# Motherboard_V1_1.net
KiCad netlist of a schematic drawn in EAGLE
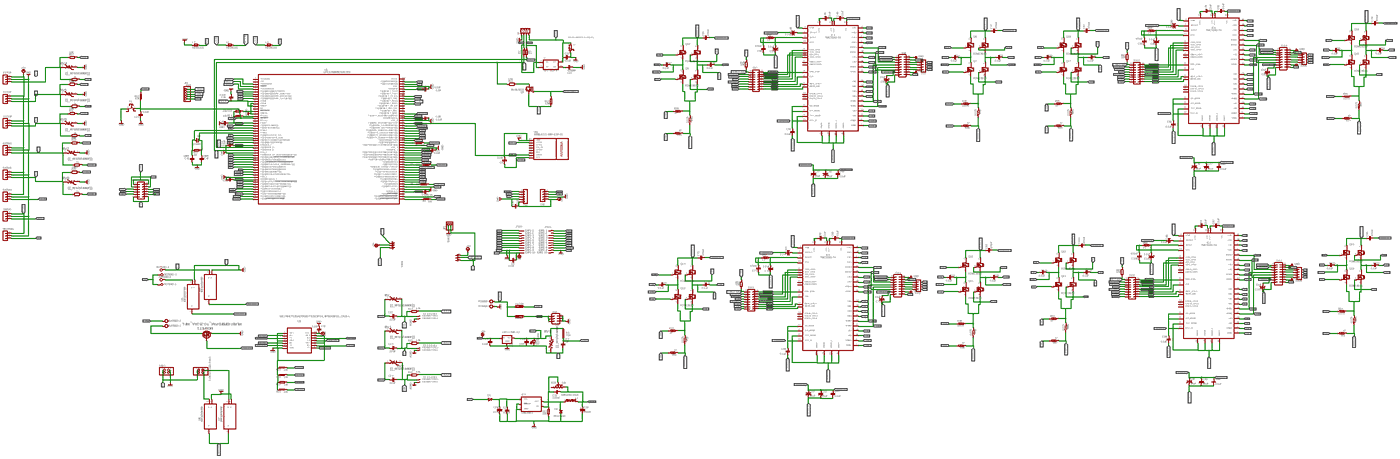
[diagram p0: schematic, sheet 1, overview]
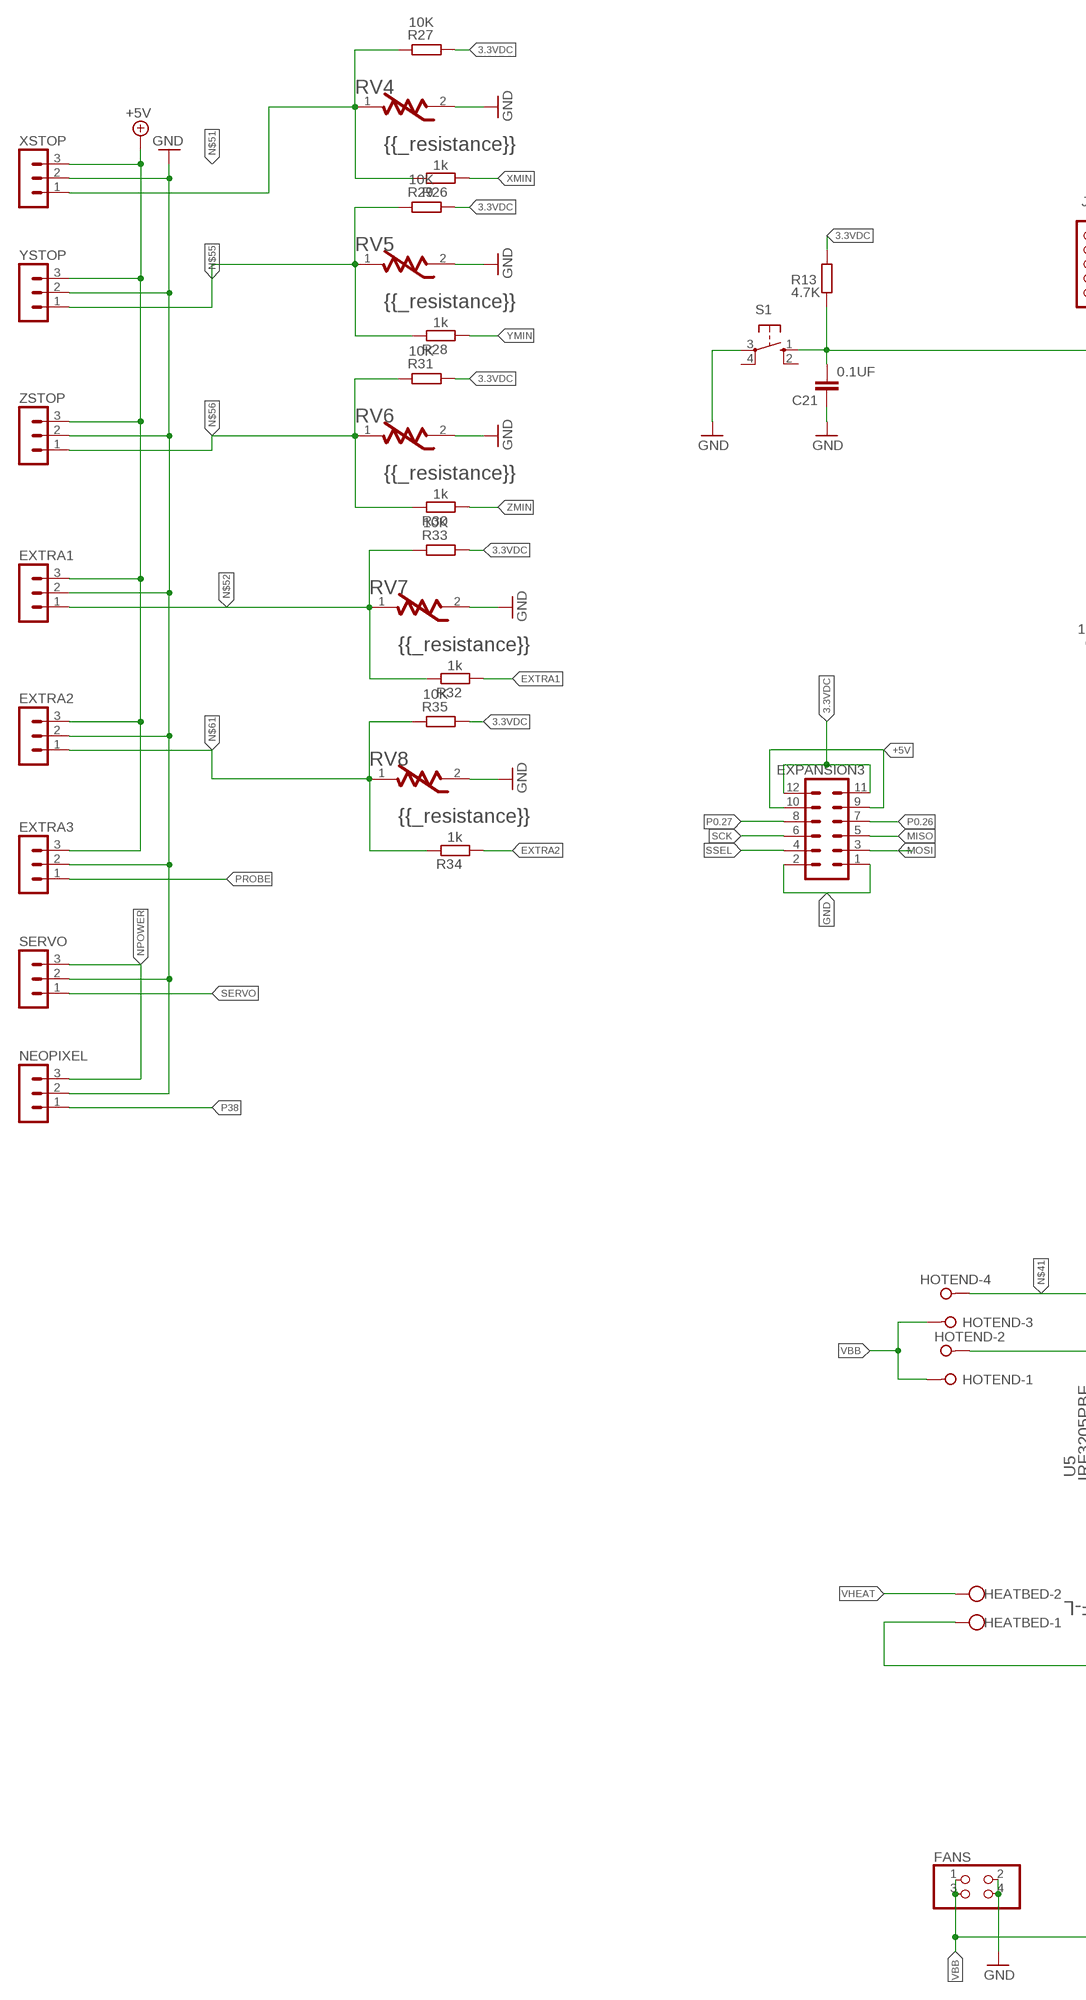
[diagram p1: schematic, sheet 1, part 1 of 4]
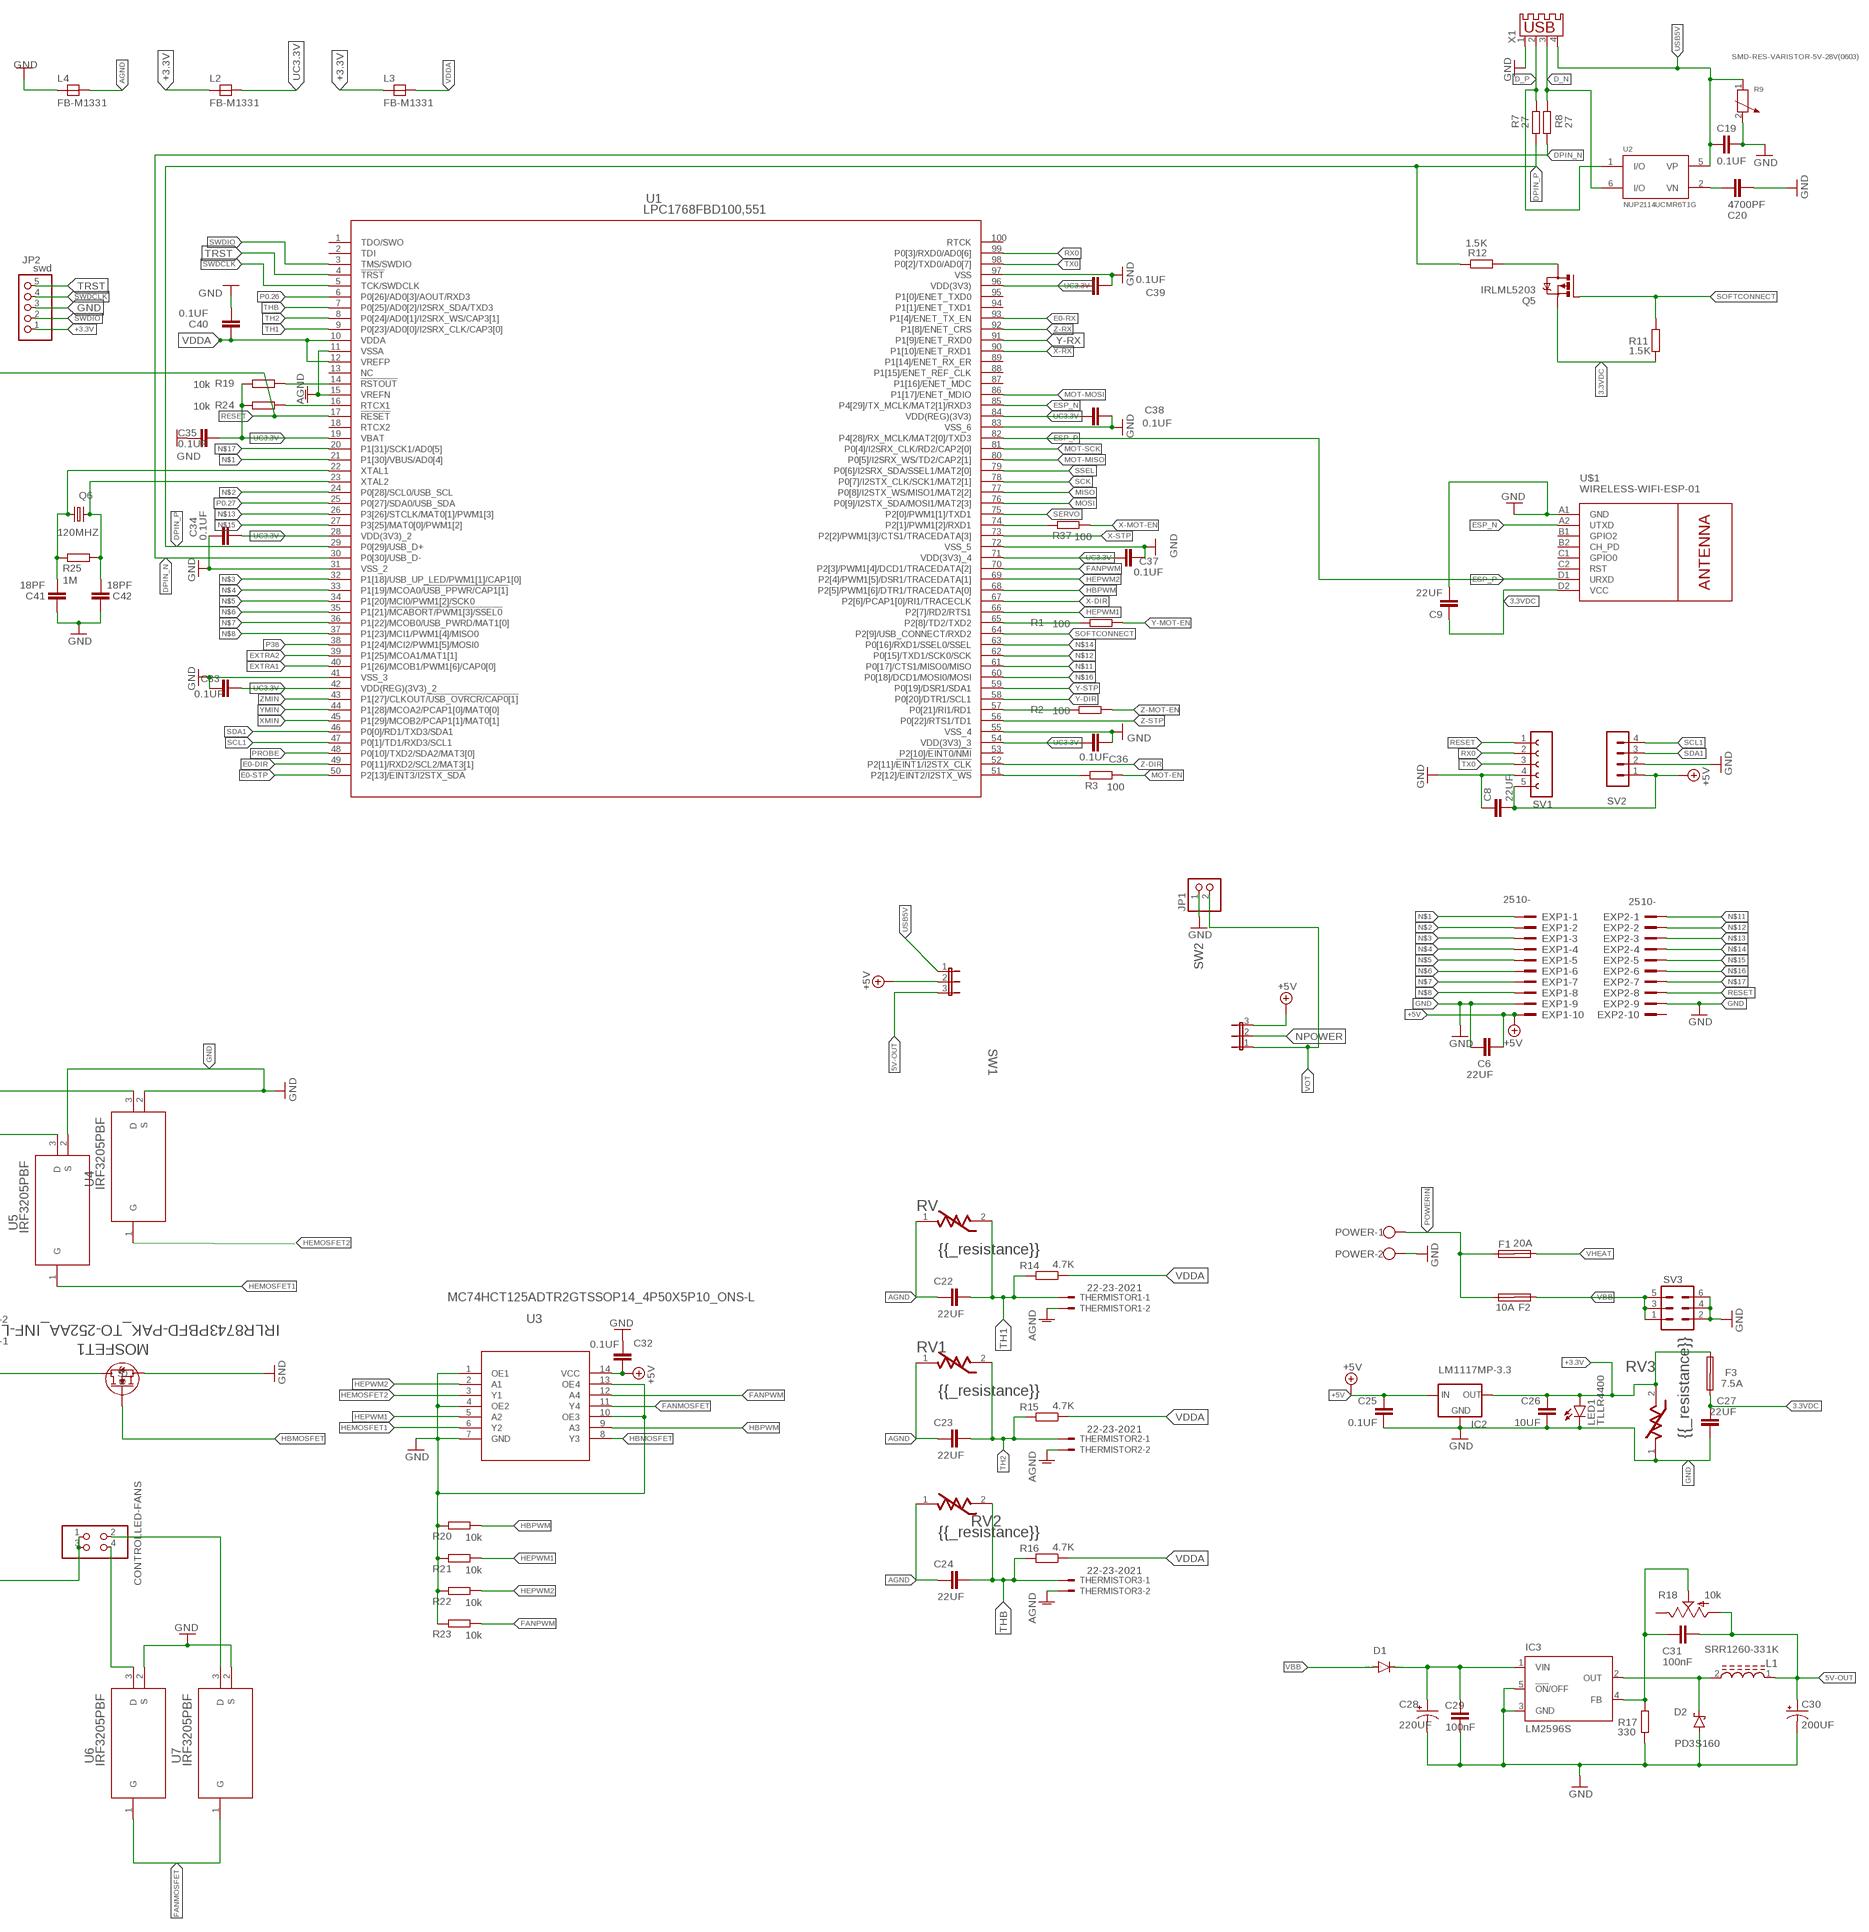
[diagram p2: schematic, sheet 1, part 2 of 4]
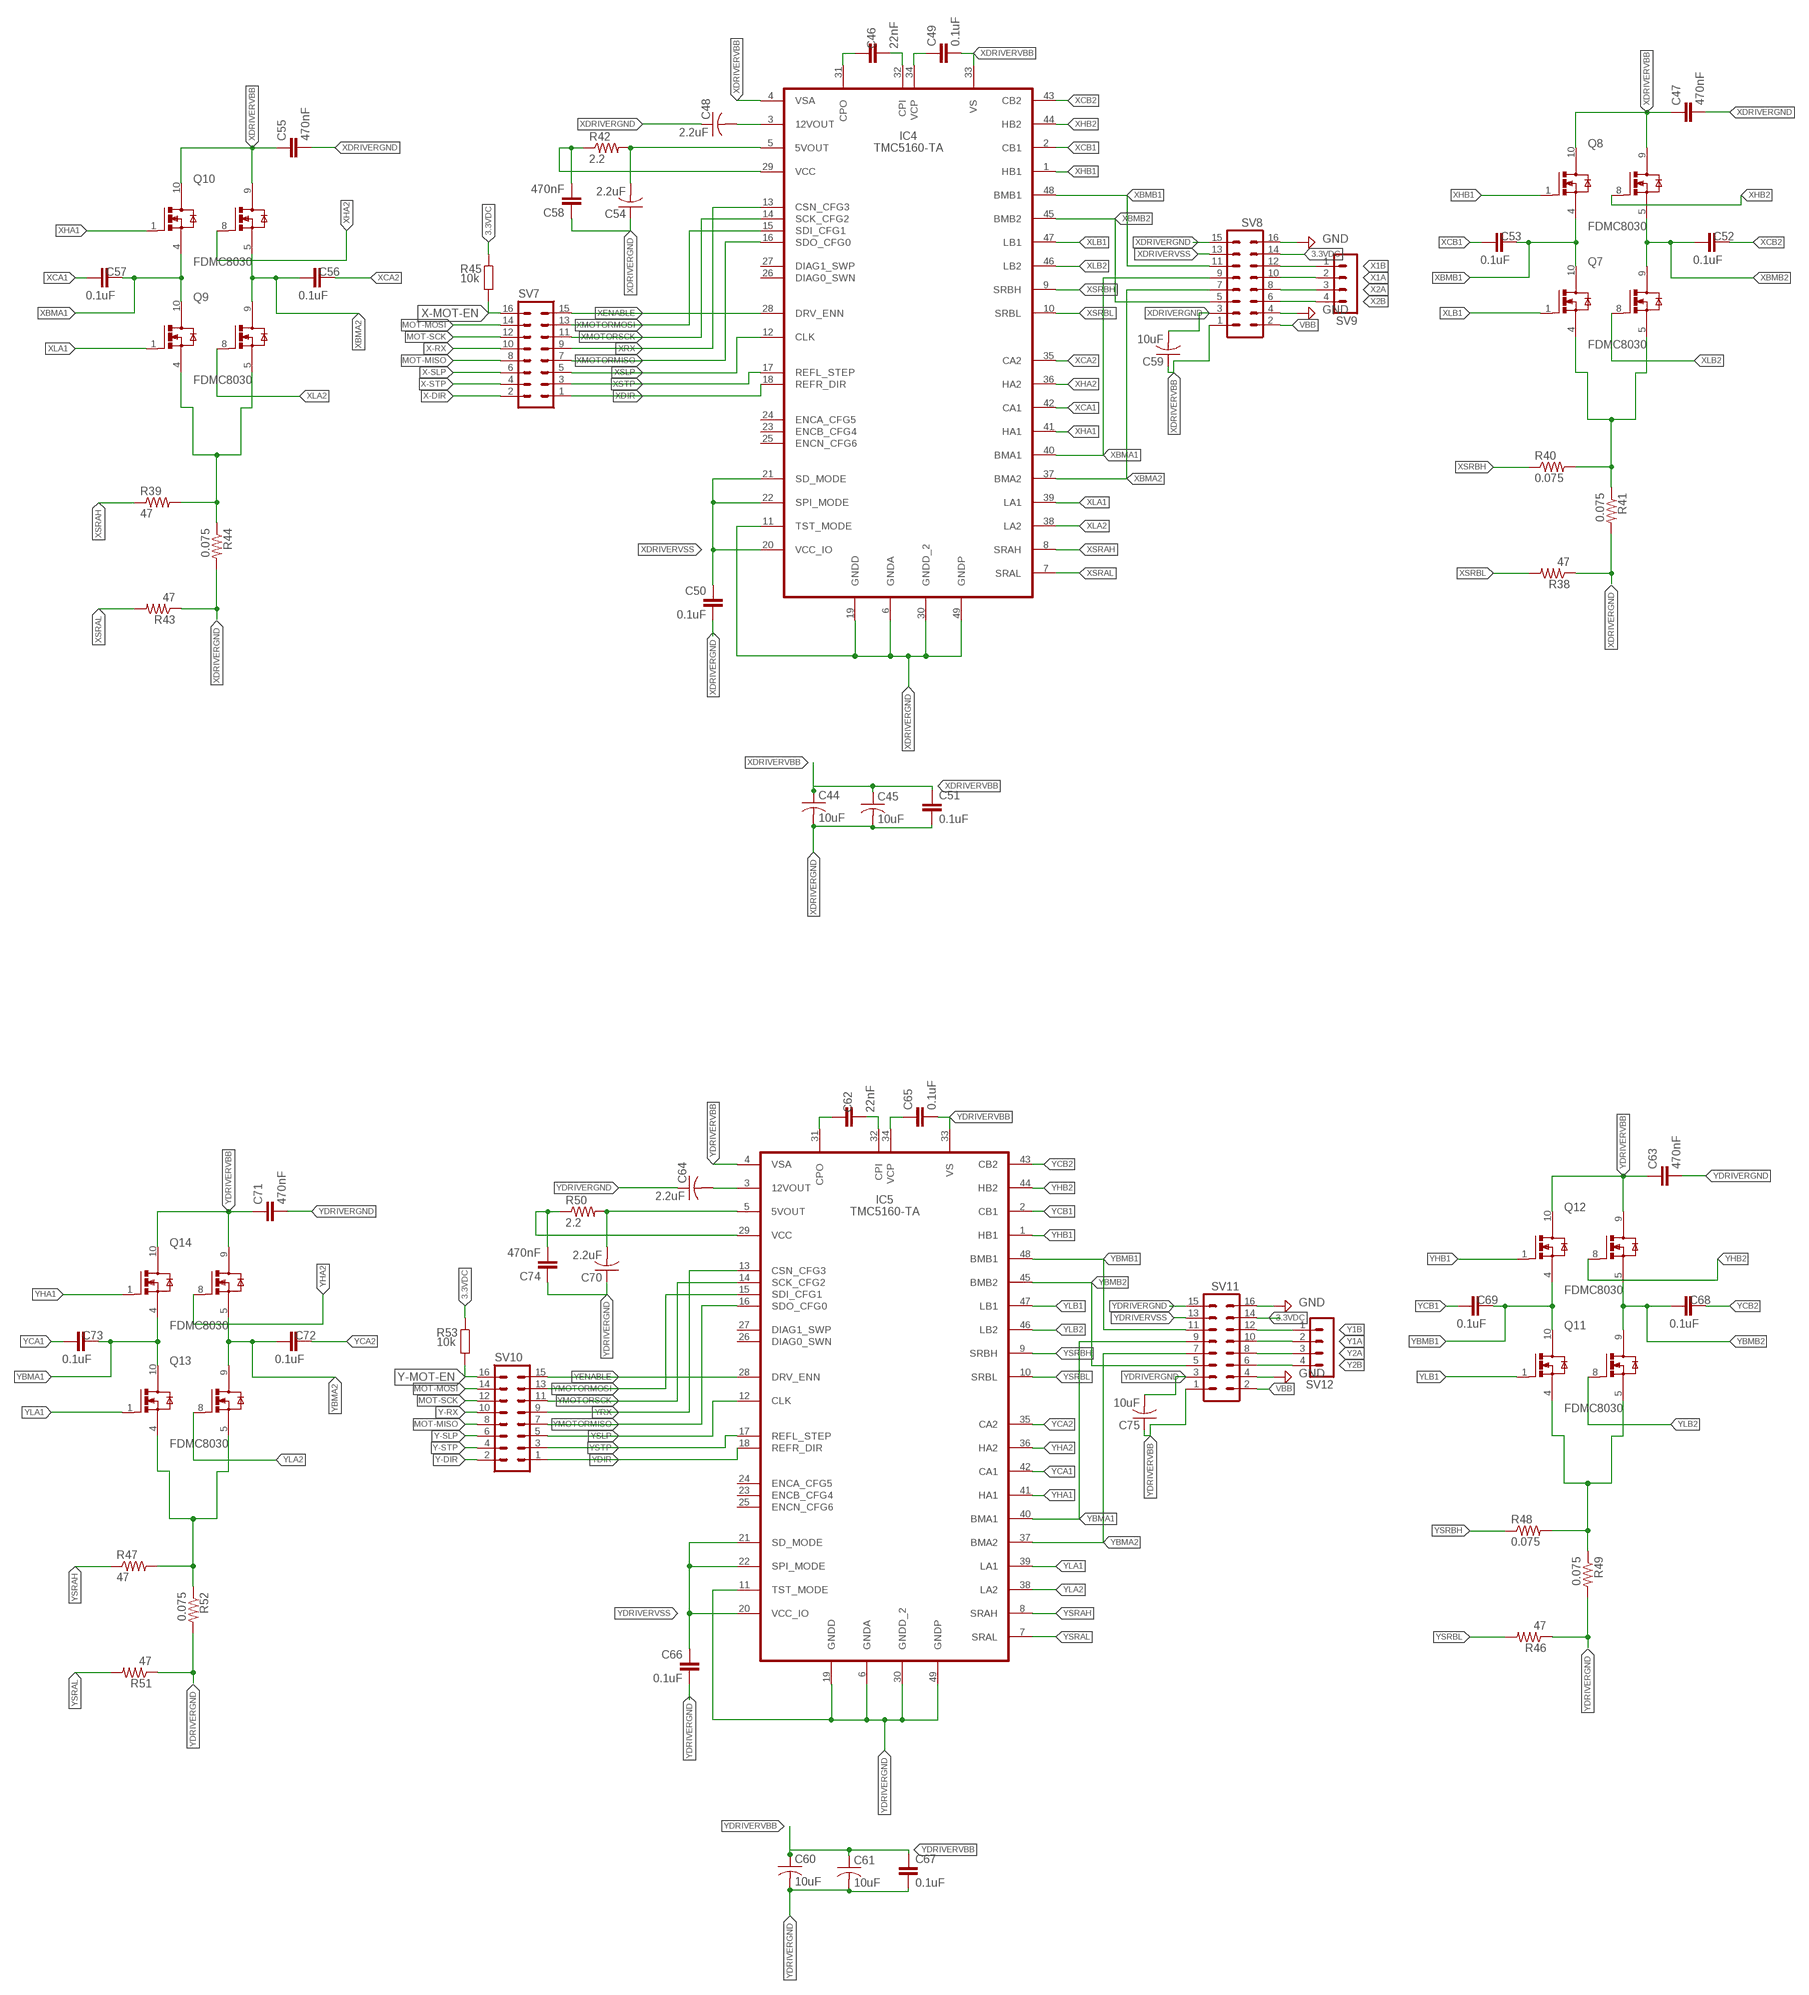
[diagram p3: schematic, sheet 1, part 3 of 4]
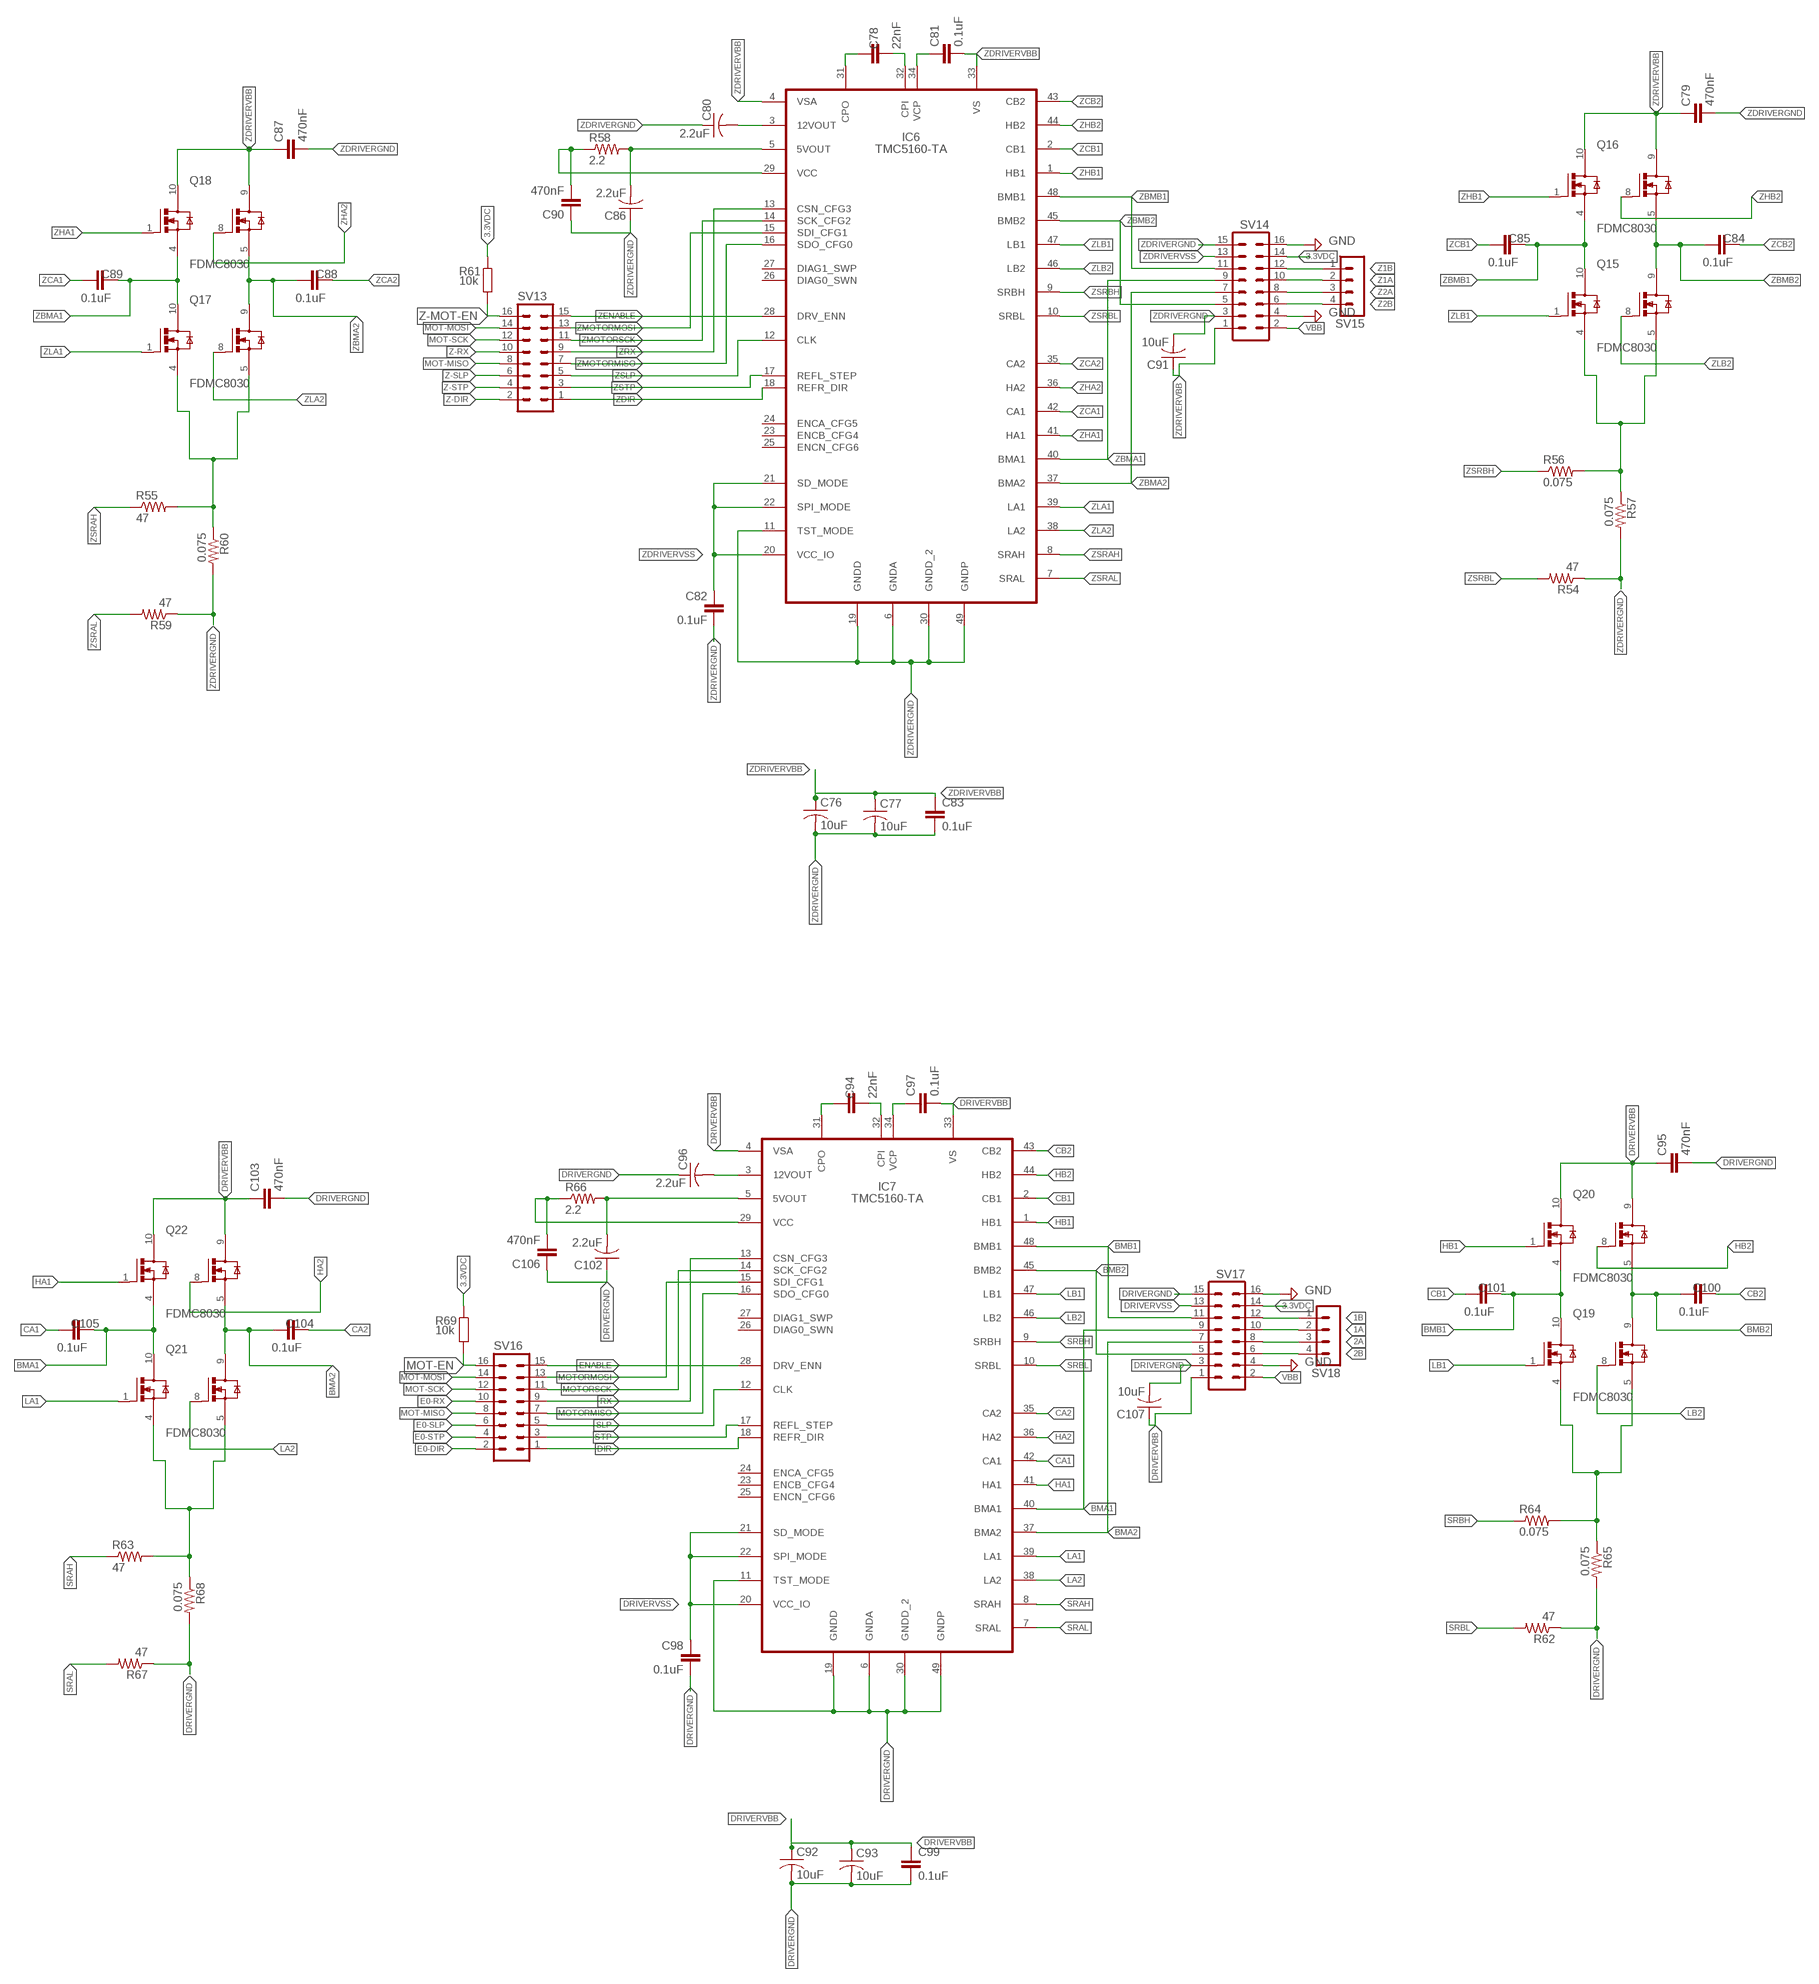
[diagram p4: schematic, sheet 1, part 4 of 4]

(export (version "E")
  (design (tool "Eeschema 10.0.6"))
  (components
    (comp (ref "C6")
      (value "22UF")
      (footprint "eagle-import:C0805")
      (libsource (lib "eagle-import") (part "C-EUC0805"))
    )
    (comp (ref "C8")
      (value "22UF")
      (footprint "eagle-import:C0805")
      (libsource (lib "eagle-import") (part "C-EUC0805"))
    )
    (comp (ref "C9")
      (value "22UF")
      (footprint "eagle-import:C0805")
      (libsource (lib "eagle-import") (part "C-EUC0805"))
    )
    (comp (ref "C19")
      (value "0.1UF")
      (footprint "eagle-import:C0805")
      (libsource (lib "eagle-import") (part "C-EUC0805"))
    )
    (comp (ref "C20")
      (value "4700PF")
      (footprint "eagle-import:C0805")
      (libsource (lib "eagle-import") (part "C-EUC0805"))
    )
    (comp (ref "C21")
      (value "0.1UF")
      (footprint "eagle-import:C0805")
      (libsource (lib "eagle-import") (part "C-EUC0805"))
    )
    (comp (ref "C22")
      (value "22UF")
      (footprint "eagle-import:C0805")
      (libsource (lib "eagle-import") (part "C-EUC0805"))
    )
    (comp (ref "C23")
      (value "22UF")
      (footprint "eagle-import:C0805")
      (libsource (lib "eagle-import") (part "C-EUC0805"))
    )
    (comp (ref "C24")
      (value "22UF")
      (footprint "eagle-import:C0805")
      (libsource (lib "eagle-import") (part "C-EUC0805"))
    )
    (comp (ref "C25")
      (value "0.1UF")
      (footprint "eagle-import:C0805")
      (libsource (lib "eagle-import") (part "C-EUC0805"))
    )
    (comp (ref "C26")
      (value "10UF")
      (footprint "eagle-import:C0805")
      (libsource (lib "eagle-import") (part "C-EUC0805"))
    )
    (comp (ref "C27")
      (value "22UF")
      (footprint "eagle-import:C0805")
      (libsource (lib "eagle-import") (part "C-EUC0805"))
    )
    (comp (ref "C28")
      (value "220UF")
      (footprint "eagle-import:E5-10,5")
      (libsource (lib "eagle-import") (part "CPOL-USE5-10.5"))
    )
    (comp (ref "C29")
      (value "100nF")
      (footprint "eagle-import:C0805")
      (libsource (lib "eagle-import") (part "C-EUC0805"))
    )
    (comp (ref "C30")
      (value "200UF")
      (footprint "eagle-import:E5-10,5")
      (libsource (lib "eagle-import") (part "CPOL-USE5-10.5"))
    )
    (comp (ref "C31")
      (value "100nF")
      (footprint "eagle-import:C0805")
      (libsource (lib "eagle-import") (part "C-EUC0805"))
    )
    (comp (ref "C32")
      (value "0.1UF")
      (footprint "eagle-import:C0805")
      (libsource (lib "eagle-import") (part "C-EUC0805"))
    )
    (comp (ref "C33")
      (value "0.1UF")
      (footprint "eagle-import:C0805")
      (libsource (lib "eagle-import") (part "C-EUC0805"))
    )
    (comp (ref "C34")
      (value "0.1UF")
      (footprint "eagle-import:C0805")
      (libsource (lib "eagle-import") (part "C-EUC0805"))
    )
    (comp (ref "C35")
      (value "0.1UF")
      (footprint "eagle-import:C0805")
      (libsource (lib "eagle-import") (part "C-EUC0805"))
    )
    (comp (ref "C36")
      (value "0.1UF")
      (footprint "eagle-import:C0805")
      (libsource (lib "eagle-import") (part "C-EUC0805"))
    )
    (comp (ref "C37")
      (value "0.1UF")
      (footprint "eagle-import:C0805")
      (libsource (lib "eagle-import") (part "C-EUC0805"))
    )
    (comp (ref "C38")
      (value "0.1UF")
      (footprint "eagle-import:C0805")
      (libsource (lib "eagle-import") (part "C-EUC0805"))
    )
    (comp (ref "C39")
      (value "0.1UF")
      (footprint "eagle-import:C0805")
      (libsource (lib "eagle-import") (part "C-EUC0805"))
    )
    (comp (ref "C40")
      (value "0.1UF")
      (footprint "eagle-import:C0805")
      (libsource (lib "eagle-import") (part "C-EUC0805"))
    )
    (comp (ref "C41")
      (value "18PF")
      (footprint "eagle-import:C0805")
      (libsource (lib "eagle-import") (part "C-EUC0805"))
    )
    (comp (ref "C42")
      (value "18PF")
      (footprint "eagle-import:C0805")
      (libsource (lib "eagle-import") (part "C-EUC0805"))
    )
    (comp (ref "C44")
      (value "10uF")
      (footprint "eagle-import:C0805")
      (libsource (lib "eagle-import") (part "C-USC0805"))
    )
    (comp (ref "C45")
      (value "10uF")
      (footprint "eagle-import:C0805")
      (libsource (lib "eagle-import") (part "C-USC0805"))
    )
    (comp (ref "C46")
      (value "22nF")
      (footprint "eagle-import:0603")
      (libsource (lib "eagle-import") (part "22NF/22,000PF-0603-50V-10%"))
    )
    (comp (ref "C47")
      (value "470nF")
      (footprint "eagle-import:0402")
      (libsource (lib "eagle-import") (part "470NF-0402-16V-10%"))
    )
    (comp (ref "C48")
      (value "2.2uF")
      (footprint "eagle-import:C0402")
      (libsource (lib "eagle-import") (part "C-USC0402"))
    )
    (comp (ref "C49")
      (value "0.1uF")
      (footprint "eagle-import:0402")
      (libsource (lib "eagle-import") (part "0.1UF-0402-16V-10%"))
    )
    (comp (ref "C50")
      (value "0.1uF")
      (footprint "eagle-import:0402")
      (libsource (lib "eagle-import") (part "0.1UF-0402-16V-10%"))
    )
    (comp (ref "C51")
      (value "0.1uF")
      (footprint "eagle-import:0402")
      (libsource (lib "eagle-import") (part "0.1UF-0402-16V-10%"))
    )
    (comp (ref "C52")
      (value "0.1uF")
      (footprint "eagle-import:0402")
      (libsource (lib "eagle-import") (part "0.1UF-0402-16V-10%"))
    )
    (comp (ref "C53")
      (value "0.1uF")
      (footprint "eagle-import:0402")
      (libsource (lib "eagle-import") (part "0.1UF-0402-16V-10%"))
    )
    (comp (ref "C54")
      (value "2.2uF")
      (footprint "eagle-import:C0402")
      (libsource (lib "eagle-import") (part "C-USC0402"))
    )
    (comp (ref "C55")
      (value "470nF")
      (footprint "eagle-import:0402")
      (libsource (lib "eagle-import") (part "470NF-0402-16V-10%"))
    )
    (comp (ref "C56")
      (value "0.1uF")
      (footprint "eagle-import:0402")
      (libsource (lib "eagle-import") (part "0.1UF-0402-16V-10%"))
    )
    (comp (ref "C57")
      (value "0.1uF")
      (footprint "eagle-import:0402")
      (libsource (lib "eagle-import") (part "0.1UF-0402-16V-10%"))
    )
    (comp (ref "C58")
      (value "470nF")
      (footprint "eagle-import:0402")
      (libsource (lib "eagle-import") (part "470NF-0402-16V-10%"))
    )
    (comp (ref "C59")
      (value "10uF")
      (footprint "eagle-import:C0805")
      (libsource (lib "eagle-import") (part "C-USC0805"))
    )
    (comp (ref "C60")
      (value "10uF")
      (footprint "eagle-import:C0805")
      (libsource (lib "eagle-import") (part "C-USC0805"))
    )
    (comp (ref "C61")
      (value "10uF")
      (footprint "eagle-import:C0805")
      (libsource (lib "eagle-import") (part "C-USC0805"))
    )
    (comp (ref "C62")
      (value "22nF")
      (footprint "eagle-import:0603")
      (libsource (lib "eagle-import") (part "22NF/22,000PF-0603-50V-10%"))
    )
    (comp (ref "C63")
      (value "470nF")
      (footprint "eagle-import:0402")
      (libsource (lib "eagle-import") (part "470NF-0402-16V-10%"))
    )
    (comp (ref "C64")
      (value "2.2uF")
      (footprint "eagle-import:C0402")
      (libsource (lib "eagle-import") (part "C-USC0402"))
    )
    (comp (ref "C65")
      (value "0.1uF")
      (footprint "eagle-import:0402")
      (libsource (lib "eagle-import") (part "0.1UF-0402-16V-10%"))
    )
    (comp (ref "C66")
      (value "0.1uF")
      (footprint "eagle-import:0402")
      (libsource (lib "eagle-import") (part "0.1UF-0402-16V-10%"))
    )
    (comp (ref "C67")
      (value "0.1uF")
      (footprint "eagle-import:0402")
      (libsource (lib "eagle-import") (part "0.1UF-0402-16V-10%"))
    )
    (comp (ref "C68")
      (value "0.1uF")
      (footprint "eagle-import:0402")
      (libsource (lib "eagle-import") (part "0.1UF-0402-16V-10%"))
    )
    (comp (ref "C69")
      (value "0.1uF")
      (footprint "eagle-import:0402")
      (libsource (lib "eagle-import") (part "0.1UF-0402-16V-10%"))
    )
    (comp (ref "C70")
      (value "2.2uF")
      (footprint "eagle-import:C0402")
      (libsource (lib "eagle-import") (part "C-USC0402"))
    )
    (comp (ref "C71")
      (value "470nF")
      (footprint "eagle-import:0402")
      (libsource (lib "eagle-import") (part "470NF-0402-16V-10%"))
    )
    (comp (ref "C72")
      (value "0.1uF")
      (footprint "eagle-import:0402")
      (libsource (lib "eagle-import") (part "0.1UF-0402-16V-10%"))
    )
    (comp (ref "C73")
      (value "0.1uF")
      (footprint "eagle-import:0402")
      (libsource (lib "eagle-import") (part "0.1UF-0402-16V-10%"))
    )
    (comp (ref "C74")
      (value "470nF")
      (footprint "eagle-import:0402")
      (libsource (lib "eagle-import") (part "470NF-0402-16V-10%"))
    )
    (comp (ref "C75")
      (value "10uF")
      (footprint "eagle-import:C0805")
      (libsource (lib "eagle-import") (part "C-USC0805"))
    )
    (comp (ref "C76")
      (value "10uF")
      (footprint "eagle-import:C0805")
      (libsource (lib "eagle-import") (part "C-USC0805"))
    )
    (comp (ref "C77")
      (value "10uF")
      (footprint "eagle-import:C0805")
      (libsource (lib "eagle-import") (part "C-USC0805"))
    )
    (comp (ref "C78")
      (value "22nF")
      (footprint "eagle-import:0603")
      (libsource (lib "eagle-import") (part "22NF/22,000PF-0603-50V-10%"))
    )
    (comp (ref "C79")
      (value "470nF")
      (footprint "eagle-import:0402")
      (libsource (lib "eagle-import") (part "470NF-0402-16V-10%"))
    )
    (comp (ref "C80")
      (value "2.2uF")
      (footprint "eagle-import:C0402")
      (libsource (lib "eagle-import") (part "C-USC0402"))
    )
    (comp (ref "C81")
      (value "0.1uF")
      (footprint "eagle-import:0402")
      (libsource (lib "eagle-import") (part "0.1UF-0402-16V-10%"))
    )
    (comp (ref "C82")
      (value "0.1uF")
      (footprint "eagle-import:0402")
      (libsource (lib "eagle-import") (part "0.1UF-0402-16V-10%"))
    )
    (comp (ref "C83")
      (value "0.1uF")
      (footprint "eagle-import:0402")
      (libsource (lib "eagle-import") (part "0.1UF-0402-16V-10%"))
    )
    (comp (ref "C84")
      (value "0.1uF")
      (footprint "eagle-import:0402")
      (libsource (lib "eagle-import") (part "0.1UF-0402-16V-10%"))
    )
    (comp (ref "C85")
      (value "0.1uF")
      (footprint "eagle-import:0402")
      (libsource (lib "eagle-import") (part "0.1UF-0402-16V-10%"))
    )
    (comp (ref "C86")
      (value "2.2uF")
      (footprint "eagle-import:C0402")
      (libsource (lib "eagle-import") (part "C-USC0402"))
    )
    (comp (ref "C87")
      (value "470nF")
      (footprint "eagle-import:0402")
      (libsource (lib "eagle-import") (part "470NF-0402-16V-10%"))
    )
    (comp (ref "C88")
      (value "0.1uF")
      (footprint "eagle-import:0402")
      (libsource (lib "eagle-import") (part "0.1UF-0402-16V-10%"))
    )
    (comp (ref "C89")
      (value "0.1uF")
      (footprint "eagle-import:0402")
      (libsource (lib "eagle-import") (part "0.1UF-0402-16V-10%"))
    )
    (comp (ref "C90")
      (value "470nF")
      (footprint "eagle-import:0402")
      (libsource (lib "eagle-import") (part "470NF-0402-16V-10%"))
    )
    (comp (ref "C91")
      (value "10uF")
      (footprint "eagle-import:C0805")
      (libsource (lib "eagle-import") (part "C-USC0805"))
    )
    (comp (ref "C92")
      (value "10uF")
      (footprint "eagle-import:C0805")
      (libsource (lib "eagle-import") (part "C-USC0805"))
    )
    (comp (ref "C93")
      (value "10uF")
      (footprint "eagle-import:C0805")
      (libsource (lib "eagle-import") (part "C-USC0805"))
    )
    (comp (ref "C94")
      (value "22nF")
      (footprint "eagle-import:0603")
      (libsource (lib "eagle-import") (part "22NF/22,000PF-0603-50V-10%"))
    )
    (comp (ref "C95")
      (value "470nF")
      (footprint "eagle-import:0402")
      (libsource (lib "eagle-import") (part "470NF-0402-16V-10%"))
    )
    (comp (ref "C96")
      (value "2.2uF")
      (footprint "eagle-import:C0402")
      (libsource (lib "eagle-import") (part "C-USC0402"))
    )
    (comp (ref "C97")
      (value "0.1uF")
      (footprint "eagle-import:0402")
      (libsource (lib "eagle-import") (part "0.1UF-0402-16V-10%"))
    )
    (comp (ref "C98")
      (value "0.1uF")
      (footprint "eagle-import:0402")
      (libsource (lib "eagle-import") (part "0.1UF-0402-16V-10%"))
    )
    (comp (ref "C99")
      (value "0.1uF")
      (footprint "eagle-import:0402")
      (libsource (lib "eagle-import") (part "0.1UF-0402-16V-10%"))
    )
    (comp (ref "C100")
      (value "0.1uF")
      (footprint "eagle-import:0402")
      (libsource (lib "eagle-import") (part "0.1UF-0402-16V-10%"))
    )
    (comp (ref "C101")
      (value "0.1uF")
      (footprint "eagle-import:0402")
      (libsource (lib "eagle-import") (part "0.1UF-0402-16V-10%"))
    )
    (comp (ref "C102")
      (value "2.2uF")
      (footprint "eagle-import:C0402")
      (libsource (lib "eagle-import") (part "C-USC0402"))
    )
    (comp (ref "C103")
      (value "470nF")
      (footprint "eagle-import:0402")
      (libsource (lib "eagle-import") (part "470NF-0402-16V-10%"))
    )
    (comp (ref "C104")
      (value "0.1uF")
      (footprint "eagle-import:0402")
      (libsource (lib "eagle-import") (part "0.1UF-0402-16V-10%"))
    )
    (comp (ref "C105")
      (value "0.1uF")
      (footprint "eagle-import:0402")
      (libsource (lib "eagle-import") (part "0.1UF-0402-16V-10%"))
    )
    (comp (ref "C106")
      (value "470nF")
      (footprint "eagle-import:0402")
      (libsource (lib "eagle-import") (part "470NF-0402-16V-10%"))
    )
    (comp (ref "C107")
      (value "10uF")
      (footprint "eagle-import:C0805")
      (libsource (lib "eagle-import") (part "C-USC0805"))
    )
    (comp (ref "CONTROLLED-FANS")
      (value "PINHD-2X2")
      (footprint "eagle-import:2X02")
      (libsource (lib "eagle-import") (part "PINHD-2X2"))
    )
    (comp (ref "D1")
      (value "DIODE-DO214AA")
      (footprint "eagle-import:DO214AA")
      (libsource (lib "eagle-import") (part "DIODE-DO214AA"))
    )
    (comp (ref "D2")
      (value "PD3S160")
      (footprint "eagle-import:POWERDI323")
      (libsource (lib "eagle-import") (part "PD3S160"))
    )
    (comp (ref "EXP1")
      (value "2510-")
      (footprint "eagle-import:PAK100_2500-10")
      (fields (field (name "MF") "3M") (field (name "MPN") "2510-6002UB"))
      (libsource (lib "eagle-import") (part "2510-"))
    )
    (comp (ref "EXP2")
      (value "2510-")
      (footprint "eagle-import:PAK100_2500-10")
      (fields (field (name "MF") "3M") (field (name "MPN") "2510-6002UB"))
      (libsource (lib "eagle-import") (part "2510-"))
    )
    (comp (ref "EXPANSION3")
      (value "MA06-2")
      (footprint "eagle-import:MA06-2")
      (libsource (lib "eagle-import") (part "MA06-2"))
    )
    (comp (ref "EXTRA1")
      (value "MA03-1")
      (footprint "eagle-import:MA03-1")
      (libsource (lib "eagle-import") (part "MA03-1"))
    )
    (comp (ref "EXTRA2")
      (value "MA03-1")
      (footprint "eagle-import:MA03-1")
      (libsource (lib "eagle-import") (part "MA03-1"))
    )
    (comp (ref "EXTRA3")
      (value "MA03-1")
      (footprint "eagle-import:MA03-1")
      (libsource (lib "eagle-import") (part "MA03-1"))
    )
    (comp (ref "F1")
      (value "20A")
      (footprint "eagle-import:SHK20Q")
      (libsource (lib "eagle-import") (part "SHK20Q"))
    )
    (comp (ref "F2")
      (value "10A")
      (footprint "eagle-import:SHK20Q")
      (libsource (lib "eagle-import") (part "SHK20Q"))
    )
    (comp (ref "F3")
      (value "7.5A")
      (footprint "eagle-import:SHK20Q")
      (libsource (lib "eagle-import") (part "SHK20Q"))
    )
    (comp (ref "FANS")
      (value "PINHD-2X2")
      (footprint "eagle-import:2X02")
      (libsource (lib "eagle-import") (part "PINHD-2X2"))
    )
    (comp (ref "HEATBED")
      (value "W237-102")
      (footprint "eagle-import:W237-102")
      (fields (field (name "MPN") "237-102"))
      (libsource (lib "eagle-import") (part "W237-102"))
    )
    (comp (ref "HOTEND")
      (value "W237-04P")
      (footprint "eagle-import:W237-4P")
      (libsource (lib "eagle-import") (part "W237-04P"))
    )
    (comp (ref "IC2")
      (value "LM1117MP-3.3")
      (footprint "eagle-import:SOT223")
      (fields (field (name "MF") "Texas Instruments"))
      (libsource (lib "eagle-import") (part "LM1117?-MP3.3"))
    )
    (comp (ref "IC3")
      (value "LM2596S")
      (footprint "eagle-import:TO263-5")
      (fields (field (name "MF") "NATIONAL SEMICONDUCTOR") (field (name "MPN") "LM2596S-ADJ/NOPB"))
      (libsource (lib "eagle-import") (part "LM2596S"))
    )
    (comp (ref "IC4")
      (value "TMC5160-TA")
      (footprint "eagle-import:TQFP48-EP")
      (fields (field (name "MF") "Trinamic Motion"))
      (libsource (lib "eagle-import") (part "TMC5160-TA"))
    )
    (comp (ref "IC5")
      (value "TMC5160-TA")
      (footprint "eagle-import:TQFP48-EP")
      (fields (field (name "MF") "Trinamic Motion"))
      (libsource (lib "eagle-import") (part "TMC5160-TA"))
    )
    (comp (ref "IC6")
      (value "TMC5160-TA")
      (footprint "eagle-import:TQFP48-EP")
      (fields (field (name "MF") "Trinamic Motion"))
      (libsource (lib "eagle-import") (part "TMC5160-TA"))
    )
    (comp (ref "IC7")
      (value "TMC5160-TA")
      (footprint "eagle-import:TQFP48-EP")
      (fields (field (name "MF") "Trinamic Motion"))
      (libsource (lib "eagle-import") (part "TMC5160-TA"))
    )
    (comp (ref "JP1")
      (value "PINHD-1X2")
      (footprint "eagle-import:1X02")
      (libsource (lib "eagle-import") (part "PINHD-1X2"))
    )
    (comp (ref "JP2")
      (value "swd")
      (footprint "eagle-import:1X05")
      (libsource (lib "eagle-import") (part "PINHD-1X5"))
    )
    (comp (ref "L1")
      (value "SRR1260-331K")
      (footprint "eagle-import:INDP125125X600N")
      (fields (field (name "MF") "Bourns"))
      (libsource (lib "eagle-import") (part "SRR1260-331K"))
    )
    (comp (ref "L2")
      (value "FB-M1331")
      (footprint "eagle-import:M1331")
      (libsource (lib "eagle-import") (part "FB-M1331"))
    )
    (comp (ref "L3")
      (value "FB-M1331")
      (footprint "eagle-import:M1331")
      (libsource (lib "eagle-import") (part "FB-M1331"))
    )
    (comp (ref "L4")
      (value "FB-M1331")
      (footprint "eagle-import:M1331")
      (libsource (lib "eagle-import") (part "FB-M1331"))
    )
    (comp (ref "LED1")
      (value "TLLR4400")
      (footprint "eagle-import:LED3MM")
      (fields (field (name "MF") "VISHAY SEMICONDUCTOR"))
      (libsource (lib "eagle-import") (part "TLLR4400"))
    )
    (comp (ref "MOSFET1")
      (value "IRLR8743PBFD-PAK_TO-252AA_INF-L")
      (footprint "eagle-import:D-PAK_TO-252AA_INF-L")
      (fields
        (field (name "MANUFACTURER_PART_NUMBER") "IRLR8743PBF")
        (field (name "COPYRIGHT") "Copyright (C) 2018 Accelerated Designs. All rights reserved")
      )
      (libsource (lib "eagle-import") (part "IRLR8743PBFD-PAK_TO-252AA_INF-L"))
    )
    (comp (ref "NEOPIXEL")
      (value "MA03-1")
      (footprint "eagle-import:MA03-1")
      (libsource (lib "eagle-import") (part "MA03-1"))
    )
    (comp (ref "POWER")
      (value "W237-102")
      (footprint "eagle-import:W237-102")
      (fields (field (name "MPN") "237-102"))
      (libsource (lib "eagle-import") (part "W237-102"))
    )
    (comp (ref "Q5")
      (value "IRLML5203")
      (footprint "eagle-import:MICRO3")
      (libsource (lib "eagle-import") (part "IRLML5203"))
    )
    (comp (ref "Q6")
      (value "120MHZ")
      (footprint "eagle-import:HC49_S")
      (libsource (lib "eagle-import") (part "CRYSTALHC49S"))
    )
    (comp (ref "Q7")
      (value "FDMC8030")
      (footprint "eagle-import:TRANS_FDMC8030")
      (fields (field (name "MF") "ON Semiconductor"))
      (libsource (lib "eagle-import") (part "FDMC8030"))
    )
    (comp (ref "Q8")
      (value "FDMC8030")
      (footprint "eagle-import:TRANS_FDMC8030")
      (fields (field (name "MF") "ON Semiconductor"))
      (libsource (lib "eagle-import") (part "FDMC8030"))
    )
    (comp (ref "Q9")
      (value "FDMC8030")
      (footprint "eagle-import:TRANS_FDMC8030")
      (fields (field (name "MF") "ON Semiconductor"))
      (libsource (lib "eagle-import") (part "FDMC8030"))
    )
    (comp (ref "Q10")
      (value "FDMC8030")
      (footprint "eagle-import:TRANS_FDMC8030")
      (fields (field (name "MF") "ON Semiconductor"))
      (libsource (lib "eagle-import") (part "FDMC8030"))
    )
    (comp (ref "Q11")
      (value "FDMC8030")
      (footprint "eagle-import:TRANS_FDMC8030")
      (fields (field (name "MF") "ON Semiconductor"))
      (libsource (lib "eagle-import") (part "FDMC8030"))
    )
    (comp (ref "Q12")
      (value "FDMC8030")
      (footprint "eagle-import:TRANS_FDMC8030")
      (fields (field (name "MF") "ON Semiconductor"))
      (libsource (lib "eagle-import") (part "FDMC8030"))
    )
    (comp (ref "Q13")
      (value "FDMC8030")
      (footprint "eagle-import:TRANS_FDMC8030")
      (fields (field (name "MF") "ON Semiconductor"))
      (libsource (lib "eagle-import") (part "FDMC8030"))
    )
    (comp (ref "Q14")
      (value "FDMC8030")
      (footprint "eagle-import:TRANS_FDMC8030")
      (fields (field (name "MF") "ON Semiconductor"))
      (libsource (lib "eagle-import") (part "FDMC8030"))
    )
    (comp (ref "Q15")
      (value "FDMC8030")
      (footprint "eagle-import:TRANS_FDMC8030")
      (fields (field (name "MF") "ON Semiconductor"))
      (libsource (lib "eagle-import") (part "FDMC8030"))
    )
    (comp (ref "Q16")
      (value "FDMC8030")
      (footprint "eagle-import:TRANS_FDMC8030")
      (fields (field (name "MF") "ON Semiconductor"))
      (libsource (lib "eagle-import") (part "FDMC8030"))
    )
    (comp (ref "Q17")
      (value "FDMC8030")
      (footprint "eagle-import:TRANS_FDMC8030")
      (fields (field (name "MF") "ON Semiconductor"))
      (libsource (lib "eagle-import") (part "FDMC8030"))
    )
    (comp (ref "Q18")
      (value "FDMC8030")
      (footprint "eagle-import:TRANS_FDMC8030")
      (fields (field (name "MF") "ON Semiconductor"))
      (libsource (lib "eagle-import") (part "FDMC8030"))
    )
    (comp (ref "Q19")
      (value "FDMC8030")
      (footprint "eagle-import:TRANS_FDMC8030")
      (fields (field (name "MF") "ON Semiconductor"))
      (libsource (lib "eagle-import") (part "FDMC8030"))
    )
    (comp (ref "Q20")
      (value "FDMC8030")
      (footprint "eagle-import:TRANS_FDMC8030")
      (fields (field (name "MF") "ON Semiconductor"))
      (libsource (lib "eagle-import") (part "FDMC8030"))
    )
    (comp (ref "Q21")
      (value "FDMC8030")
      (footprint "eagle-import:TRANS_FDMC8030")
      (fields (field (name "MF") "ON Semiconductor"))
      (libsource (lib "eagle-import") (part "FDMC8030"))
    )
    (comp (ref "Q22")
      (value "FDMC8030")
      (footprint "eagle-import:TRANS_FDMC8030")
      (fields (field (name "MF") "ON Semiconductor"))
      (libsource (lib "eagle-import") (part "FDMC8030"))
    )
    (comp (ref "R1")
      (value "100")
      (footprint "eagle-import:R0805")
      (libsource (lib "eagle-import") (part "R-EU_R0805"))
    )
    (comp (ref "R2")
      (value "100")
      (footprint "eagle-import:R0805")
      (libsource (lib "eagle-import") (part "R-EU_R0805"))
    )
    (comp (ref "R3")
      (value "100")
      (footprint "eagle-import:R0805")
      (libsource (lib "eagle-import") (part "R-EU_R0805"))
    )
    (comp (ref "R7")
      (value "27")
      (footprint "eagle-import:R0805")
      (libsource (lib "eagle-import") (part "R-EU_R0805"))
    )
    (comp (ref "R8")
      (value "27")
      (footprint "eagle-import:R0805")
      (libsource (lib "eagle-import") (part "R-EU_R0805"))
    )
    (comp (ref "R9")
      (value "SMD-RES-VARISTOR-5V-28V(0603)")
      (footprint "eagle-import:R0603")
      (fields
        (field (name "DIGI-KEY_PART_NUMBER") "CG0603MLC-05ECT-ND")
        (field (name "MF") "Bourns")
        (field (name "MP") "CG0603MLC-05E")
      )
      (libsource (lib "eagle-import") (part "SMD-RES-VARISTOR-5V-28V(0603)"))
    )
    (comp (ref "R11")
      (value "1.5K")
      (footprint "eagle-import:R0805")
      (libsource (lib "eagle-import") (part "R-EU_R0805"))
    )
    (comp (ref "R12")
      (value "1.5K")
      (footprint "eagle-import:R0805")
      (libsource (lib "eagle-import") (part "R-EU_R0805"))
    )
    (comp (ref "R13")
      (value "4.7K")
      (footprint "eagle-import:R0805")
      (libsource (lib "eagle-import") (part "R-EU_R0805"))
    )
    (comp (ref "R14")
      (value "4.7K")
      (footprint "eagle-import:R0805")
      (libsource (lib "eagle-import") (part "R-EU_R0805"))
    )
    (comp (ref "R15")
      (value "4.7K")
      (footprint "eagle-import:R0805")
      (libsource (lib "eagle-import") (part "R-EU_R0805"))
    )
    (comp (ref "R16")
      (value "4.7K")
      (footprint "eagle-import:R0805")
      (libsource (lib "eagle-import") (part "R-EU_R0805"))
    )
    (comp (ref "R17")
      (value "330")
      (footprint "eagle-import:R0805")
      (libsource (lib "eagle-import") (part "R-EU_R0805"))
    )
    (comp (ref "R18")
      (value "10k")
      (footprint "eagle-import:B64Y")
      (libsource (lib "eagle-import") (part "TRIM_US-B64Y"))
    )
    (comp (ref "R19")
      (value "10k")
      (footprint "eagle-import:R0805")
      (libsource (lib "eagle-import") (part "R-EU_R0805"))
    )
    (comp (ref "R20")
      (value "10k")
      (footprint "eagle-import:R0805")
      (libsource (lib "eagle-import") (part "R-EU_R0805"))
    )
    (comp (ref "R21")
      (value "10k")
      (footprint "eagle-import:R0805")
      (libsource (lib "eagle-import") (part "R-EU_R0805"))
    )
    (comp (ref "R22")
      (value "10k")
      (footprint "eagle-import:R0805")
      (libsource (lib "eagle-import") (part "R-EU_R0805"))
    )
    (comp (ref "R23")
      (value "10k")
      (footprint "eagle-import:R0805")
      (libsource (lib "eagle-import") (part "R-EU_R0805"))
    )
    (comp (ref "R24")
      (value "10k")
      (footprint "eagle-import:R0805")
      (libsource (lib "eagle-import") (part "R-EU_R0805"))
    )
    (comp (ref "R25")
      (value "1M")
      (footprint "eagle-import:R0805")
      (libsource (lib "eagle-import") (part "R-EU_R0805"))
    )
    (comp (ref "R26")
      (value "1k")
      (footprint "eagle-import:R0805")
      (libsource (lib "eagle-import") (part "R-EU_R0805"))
    )
    (comp (ref "R27")
      (value "10K")
      (footprint "eagle-import:R0805")
      (libsource (lib "eagle-import") (part "R-EU_R0805"))
    )
    (comp (ref "R28")
      (value "1k")
      (footprint "eagle-import:R0805")
      (libsource (lib "eagle-import") (part "R-EU_R0805"))
    )
    (comp (ref "R29")
      (value "10K")
      (footprint "eagle-import:R0805")
      (libsource (lib "eagle-import") (part "R-EU_R0805"))
    )
    (comp (ref "R30")
      (value "1k")
      (footprint "eagle-import:R0805")
      (libsource (lib "eagle-import") (part "R-EU_R0805"))
    )
    (comp (ref "R31")
      (value "10K")
      (footprint "eagle-import:R0805")
      (libsource (lib "eagle-import") (part "R-EU_R0805"))
    )
    (comp (ref "R32")
      (value "1k")
      (footprint "eagle-import:R0805")
      (libsource (lib "eagle-import") (part "R-EU_R0805"))
    )
    (comp (ref "R33")
      (value "10K")
      (footprint "eagle-import:R0805")
      (libsource (lib "eagle-import") (part "R-EU_R0805"))
    )
    (comp (ref "R34")
      (value "1k")
      (footprint "eagle-import:R0805")
      (libsource (lib "eagle-import") (part "R-EU_R0805"))
    )
    (comp (ref "R35")
      (value "10K")
      (footprint "eagle-import:R0805")
      (libsource (lib "eagle-import") (part "R-EU_R0805"))
    )
    (comp (ref "R37")
      (value "100")
      (footprint "eagle-import:R0805")
      (libsource (lib "eagle-import") (part "R-EU_R0805"))
    )
    (comp (ref "R38")
      (value "47")
      (footprint "eagle-import:R0402")
      (libsource (lib "eagle-import") (part "R-US_R0402"))
    )
    (comp (ref "R39")
      (value "47")
      (footprint "eagle-import:R0402")
      (libsource (lib "eagle-import") (part "R-US_R0402"))
    )
    (comp (ref "R40")
      (value "0.075")
      (footprint "eagle-import:R1206")
      (libsource (lib "eagle-import") (part "R-US_R1206"))
    )
    (comp (ref "R41")
      (value "0.075")
      (footprint "eagle-import:R1206")
      (libsource (lib "eagle-import") (part "R-US_R1206"))
    )
    (comp (ref "R42")
      (value "2.2")
      (footprint "eagle-import:R0402")
      (libsource (lib "eagle-import") (part "R-US_R0402"))
    )
    (comp (ref "R43")
      (value "47")
      (footprint "eagle-import:R0402")
      (libsource (lib "eagle-import") (part "R-US_R0402"))
    )
    (comp (ref "R44")
      (value "0.075")
      (footprint "eagle-import:R1206")
      (libsource (lib "eagle-import") (part "R-US_R1206"))
    )
    (comp (ref "R45")
      (value "10k")
      (footprint "eagle-import:R0805")
      (libsource (lib "eagle-import") (part "R-EU_R0805"))
    )
    (comp (ref "R46")
      (value "47")
      (footprint "eagle-import:R0402")
      (libsource (lib "eagle-import") (part "R-US_R0402"))
    )
    (comp (ref "R47")
      (value "47")
      (footprint "eagle-import:R0402")
      (libsource (lib "eagle-import") (part "R-US_R0402"))
    )
    (comp (ref "R48")
      (value "0.075")
      (footprint "eagle-import:R1206")
      (libsource (lib "eagle-import") (part "R-US_R1206"))
    )
    (comp (ref "R49")
      (value "0.075")
      (footprint "eagle-import:R1206")
      (libsource (lib "eagle-import") (part "R-US_R1206"))
    )
    (comp (ref "R50")
      (value "2.2")
      (footprint "eagle-import:R0402")
      (libsource (lib "eagle-import") (part "R-US_R0402"))
    )
    (comp (ref "R51")
      (value "47")
      (footprint "eagle-import:R0402")
      (libsource (lib "eagle-import") (part "R-US_R0402"))
    )
    (comp (ref "R52")
      (value "0.075")
      (footprint "eagle-import:R1206")
      (libsource (lib "eagle-import") (part "R-US_R1206"))
    )
    (comp (ref "R53")
      (value "10k")
      (footprint "eagle-import:R0805")
      (libsource (lib "eagle-import") (part "R-EU_R0805"))
    )
    (comp (ref "R54")
      (value "47")
      (footprint "eagle-import:R0402")
      (libsource (lib "eagle-import") (part "R-US_R0402"))
    )
    (comp (ref "R55")
      (value "47")
      (footprint "eagle-import:R0402")
      (libsource (lib "eagle-import") (part "R-US_R0402"))
    )
    (comp (ref "R56")
      (value "0.075")
      (footprint "eagle-import:R1206")
      (libsource (lib "eagle-import") (part "R-US_R1206"))
    )
    (comp (ref "R57")
      (value "0.075")
      (footprint "eagle-import:R1206")
      (libsource (lib "eagle-import") (part "R-US_R1206"))
    )
    (comp (ref "R58")
      (value "2.2")
      (footprint "eagle-import:R0402")
      (libsource (lib "eagle-import") (part "R-US_R0402"))
    )
    (comp (ref "R59")
      (value "47")
      (footprint "eagle-import:R0402")
      (libsource (lib "eagle-import") (part "R-US_R0402"))
    )
    (comp (ref "R60")
      (value "0.075")
      (footprint "eagle-import:R1206")
      (libsource (lib "eagle-import") (part "R-US_R1206"))
    )
    (comp (ref "R61")
      (value "10k")
      (footprint "eagle-import:R0805")
      (libsource (lib "eagle-import") (part "R-EU_R0805"))
    )
    (comp (ref "R62")
      (value "47")
      (footprint "eagle-import:R0402")
      (libsource (lib "eagle-import") (part "R-US_R0402"))
    )
    (comp (ref "R63")
      (value "47")
      (footprint "eagle-import:R0402")
      (libsource (lib "eagle-import") (part "R-US_R0402"))
    )
    (comp (ref "R64")
      (value "0.075")
      (footprint "eagle-import:R1206")
      (libsource (lib "eagle-import") (part "R-US_R1206"))
    )
    (comp (ref "R65")
      (value "0.075")
      (footprint "eagle-import:R1206")
      (libsource (lib "eagle-import") (part "R-US_R1206"))
    )
    (comp (ref "R66")
      (value "2.2")
      (footprint "eagle-import:R0402")
      (libsource (lib "eagle-import") (part "R-US_R0402"))
    )
    (comp (ref "R67")
      (value "47")
      (footprint "eagle-import:R0402")
      (libsource (lib "eagle-import") (part "R-US_R0402"))
    )
    (comp (ref "R68")
      (value "0.075")
      (footprint "eagle-import:R1206")
      (libsource (lib "eagle-import") (part "R-US_R1206"))
    )
    (comp (ref "R69")
      (value "10k")
      (footprint "eagle-import:R0805")
      (libsource (lib "eagle-import") (part "R-EU_R0805"))
    )
    (comp (ref "RV")
      (value "BOURNS_INC._CG0603MLC-3.3LEBOURNS_INC._CG0603MLC-3.3LE_0_1")
      (footprint "eagle-import:BOURNS_INC._CG0603MLC-3.3LE_1")
      (fields
        (field (name "DIGIKEY_PART_NUMBER") "CG0603MLC-3.3LECT-ND")
        (field (name "MF") "Bourns Inc.")
        (field (name "MOUSER_PART_NUMBER") "652-CG0603MLC-3.3LE")
      )
      (libsource (lib "eagle-import") (part "BOURNS_INC._CG0603MLC-3.3LEBOURNS_INC._CG0603MLC-3.3LE_0_1"))
    )
    (comp (ref "RV1")
      (value "BOURNS_INC._CG0603MLC-3.3LEBOURNS_INC._CG0603MLC-3.3LE_0_1")
      (footprint "eagle-import:BOURNS_INC._CG0603MLC-3.3LE_1")
      (fields
        (field (name "DIGIKEY_PART_NUMBER") "CG0603MLC-3.3LECT-ND")
        (field (name "MF") "Bourns Inc.")
        (field (name "MOUSER_PART_NUMBER") "652-CG0603MLC-3.3LE")
      )
      (libsource (lib "eagle-import") (part "BOURNS_INC._CG0603MLC-3.3LEBOURNS_INC._CG0603MLC-3.3LE_0_1"))
    )
    (comp (ref "RV2")
      (value "BOURNS_INC._CG0603MLC-3.3LEBOURNS_INC._CG0603MLC-3.3LE_0_1")
      (footprint "eagle-import:BOURNS_INC._CG0603MLC-3.3LE_1")
      (fields
        (field (name "DIGIKEY_PART_NUMBER") "CG0603MLC-3.3LECT-ND")
        (field (name "MF") "Bourns Inc.")
        (field (name "MOUSER_PART_NUMBER") "652-CG0603MLC-3.3LE")
      )
      (libsource (lib "eagle-import") (part "BOURNS_INC._CG0603MLC-3.3LEBOURNS_INC._CG0603MLC-3.3LE_0_1"))
    )
    (comp (ref "RV3")
      (value "BOURNS_INC._CG0603MLC-3.3LEBOURNS_INC._CG0603MLC-3.3LE_0_1")
      (footprint "eagle-import:BOURNS_INC._CG0603MLC-3.3LE_1")
      (fields
        (field (name "DIGIKEY_PART_NUMBER") "CG0603MLC-3.3LECT-ND")
        (field (name "MF") "Bourns Inc.")
        (field (name "MOUSER_PART_NUMBER") "652-CG0603MLC-3.3LE")
      )
      (libsource (lib "eagle-import") (part "BOURNS_INC._CG0603MLC-3.3LEBOURNS_INC._CG0603MLC-3.3LE_0_1"))
    )
    (comp (ref "RV4")
      (value "BOURNS_INC._CG0603MLC-3.3LEBOURNS_INC._CG0603MLC-3.3LE_0_1")
      (footprint "eagle-import:BOURNS_INC._CG0603MLC-3.3LE_1")
      (fields
        (field (name "DIGIKEY_PART_NUMBER") "CG0603MLC-3.3LECT-ND")
        (field (name "MF") "Bourns Inc.")
        (field (name "MOUSER_PART_NUMBER") "652-CG0603MLC-3.3LE")
      )
      (libsource (lib "eagle-import") (part "BOURNS_INC._CG0603MLC-3.3LEBOURNS_INC._CG0603MLC-3.3LE_0_1"))
    )
    (comp (ref "RV5")
      (value "BOURNS_INC._CG0603MLC-3.3LEBOURNS_INC._CG0603MLC-3.3LE_0_1")
      (footprint "eagle-import:BOURNS_INC._CG0603MLC-3.3LE_1")
      (fields
        (field (name "DIGIKEY_PART_NUMBER") "CG0603MLC-3.3LECT-ND")
        (field (name "MF") "Bourns Inc.")
        (field (name "MOUSER_PART_NUMBER") "652-CG0603MLC-3.3LE")
      )
      (libsource (lib "eagle-import") (part "BOURNS_INC._CG0603MLC-3.3LEBOURNS_INC._CG0603MLC-3.3LE_0_1"))
    )
    (comp (ref "RV6")
      (value "BOURNS_INC._CG0603MLC-3.3LEBOURNS_INC._CG0603MLC-3.3LE_0_1")
      (footprint "eagle-import:BOURNS_INC._CG0603MLC-3.3LE_1")
      (fields
        (field (name "DIGIKEY_PART_NUMBER") "CG0603MLC-3.3LECT-ND")
        (field (name "MF") "Bourns Inc.")
        (field (name "MOUSER_PART_NUMBER") "652-CG0603MLC-3.3LE")
      )
      (libsource (lib "eagle-import") (part "BOURNS_INC._CG0603MLC-3.3LEBOURNS_INC._CG0603MLC-3.3LE_0_1"))
    )
    (comp (ref "RV7")
      (value "BOURNS_INC._CG0603MLC-3.3LEBOURNS_INC._CG0603MLC-3.3LE_0_1")
      (footprint "eagle-import:BOURNS_INC._CG0603MLC-3.3LE_1")
      (fields
        (field (name "DIGIKEY_PART_NUMBER") "CG0603MLC-3.3LECT-ND")
        (field (name "MF") "Bourns Inc.")
        (field (name "MOUSER_PART_NUMBER") "652-CG0603MLC-3.3LE")
      )
      (libsource (lib "eagle-import") (part "BOURNS_INC._CG0603MLC-3.3LEBOURNS_INC._CG0603MLC-3.3LE_0_1"))
    )
    (comp (ref "RV8")
      (value "BOURNS_INC._CG0603MLC-3.3LEBOURNS_INC._CG0603MLC-3.3LE_0_1")
      (footprint "eagle-import:BOURNS_INC._CG0603MLC-3.3LE_1")
      (fields
        (field (name "DIGIKEY_PART_NUMBER") "CG0603MLC-3.3LECT-ND")
        (field (name "MF") "Bourns Inc.")
        (field (name "MOUSER_PART_NUMBER") "652-CG0603MLC-3.3LE")
      )
      (libsource (lib "eagle-import") (part "BOURNS_INC._CG0603MLC-3.3LEBOURNS_INC._CG0603MLC-3.3LE_0_1"))
    )
    (comp (ref "S1")
      (value "10-XX")
      (footprint "eagle-import:B3F-10XX")
      (fields (field (name "MPN") "B3F-1000"))
      (libsource (lib "eagle-import") (part "10-XX"))
    )
    (comp (ref "SERVO")
      (value "MA03-1")
      (footprint "eagle-import:MA03-1")
      (libsource (lib "eagle-import") (part "MA03-1"))
    )
    (comp (ref "SV1")
      (value "FE05-1")
      (footprint "eagle-import:FE05-1")
      (libsource (lib "eagle-import") (part "FE05-1"))
    )
    (comp (ref "SV2")
      (value "MA04-1")
      (footprint "eagle-import:MA04-1")
      (libsource (lib "eagle-import") (part "MA04-1"))
    )
    (comp (ref "SV3")
      (value "MA03-2")
      (footprint "eagle-import:MA03-2")
      (libsource (lib "eagle-import") (part "MA03-2"))
    )
    (comp (ref "SV7")
      (value "MA08-2")
      (footprint "eagle-import:MA08-2")
      (libsource (lib "eagle-import") (part "MA08-2"))
    )
    (comp (ref "SV8")
      (value "MA08-2")
      (footprint "eagle-import:MA08-2")
      (libsource (lib "eagle-import") (part "MA08-2"))
    )
    (comp (ref "SV9")
      (value "MA04-1")
      (footprint "eagle-import:MA04-1")
      (libsource (lib "eagle-import") (part "MA04-1"))
    )
    (comp (ref "SV10")
      (value "MA08-2")
      (footprint "eagle-import:MA08-2")
      (libsource (lib "eagle-import") (part "MA08-2"))
    )
    (comp (ref "SV11")
      (value "MA08-2")
      (footprint "eagle-import:MA08-2")
      (libsource (lib "eagle-import") (part "MA08-2"))
    )
    (comp (ref "SV12")
      (value "MA04-1")
      (footprint "eagle-import:MA04-1")
      (libsource (lib "eagle-import") (part "MA04-1"))
    )
    (comp (ref "SV13")
      (value "MA08-2")
      (footprint "eagle-import:MA08-2")
      (libsource (lib "eagle-import") (part "MA08-2"))
    )
    (comp (ref "SV14")
      (value "MA08-2")
      (footprint "eagle-import:MA08-2")
      (libsource (lib "eagle-import") (part "MA08-2"))
    )
    (comp (ref "SV15")
      (value "MA04-1")
      (footprint "eagle-import:MA04-1")
      (libsource (lib "eagle-import") (part "MA04-1"))
    )
    (comp (ref "SV16")
      (value "MA08-2")
      (footprint "eagle-import:MA08-2")
      (libsource (lib "eagle-import") (part "MA08-2"))
    )
    (comp (ref "SV17")
      (value "MA08-2")
      (footprint "eagle-import:MA08-2")
      (libsource (lib "eagle-import") (part "MA08-2"))
    )
    (comp (ref "SV18")
      (value "MA04-1")
      (footprint "eagle-import:MA04-1")
      (libsource (lib "eagle-import") (part "MA04-1"))
    )
    (comp (ref "SW1")
      (value "JP2E")
      (footprint "eagle-import:JP2")
      (libsource (lib "eagle-import") (part "JP2E"))
    )
    (comp (ref "SW2")
      (value "JP2E")
      (footprint "eagle-import:JP2")
      (libsource (lib "eagle-import") (part "JP2E"))
    )
    (comp (ref "THERMISTOR1")
      (value "22-23-2021")
      (footprint "eagle-import:22-23-2021")
      (fields (field (name "MF") "MOLEX"))
      (libsource (lib "eagle-import") (part "22-23-2021"))
    )
    (comp (ref "THERMISTOR2")
      (value "22-23-2021")
      (footprint "eagle-import:22-23-2021")
      (fields (field (name "MF") "MOLEX"))
      (libsource (lib "eagle-import") (part "22-23-2021"))
    )
    (comp (ref "THERMISTOR3")
      (value "22-23-2021")
      (footprint "eagle-import:22-23-2021")
      (fields (field (name "MF") "MOLEX"))
      (libsource (lib "eagle-import") (part "22-23-2021"))
    )
    (comp (ref "U$1")
      (value "WIRELESS-WIFI-ESP-01")
      (footprint "eagle-import:WIRELESS-WIFI-ESP-01")
      (libsource (lib "eagle-import") (part "WIRELESS-WIFI-ESP-01"))
    )
    (comp (ref "U1")
      (value "LPC1768FBD100,551")
      (footprint "eagle-import:LQFP100_14X14_NXP")
      (fields (field (name "COPYRIGHT") "Copyright (C) 2016 Accelerated Designs. All rights reserved"))
      (libsource (lib "eagle-import") (part "LPC1768FBD100,551"))
    )
    (comp (ref "U2")
      (value "NUP2114UCMR6T1G")
      (footprint "eagle-import:SOP95P275X110-6N")
      (fields
        (field (name "DIGI-KEY_PART_NUMBER") "NUP2114UCMR6T1GOSCT-ND")
        (field (name "MF") "ON Semiconductor")
      )
      (libsource (lib "eagle-import") (part "NUP2114UCMR6T1G"))
    )
    (comp (ref "U3")
      (value "MC74HCT125ADTR2GTSSOP14_4P50X5P10_ONS-L")
      (footprint "eagle-import:TSSOP14_4P50X5P10_ONS-L")
      (fields
        (field (name "MANUFACTURER_PART_NUMBER") "MC74HCT125ADTR2G")
        (field (name "COPYRIGHT") "Copyright (C) 2016 Accelerated Designs. All rights reserved")
      )
      (libsource (lib "eagle-import") (part "MC74HCT125ADTR2GTSSOP14_4P50X5P10_ONS-L"))
    )
    (comp (ref "U4")
      (value "IRF3205PBF")
      (footprint "eagle-import:PG-TO220-3_INF")
      (fields (field (name "COPYRIGHT") "Copyright (C) 2018 Accelerated Designs. All rights reserved"))
      (libsource (lib "eagle-import") (part "IRF3205PBF"))
    )
    (comp (ref "U5")
      (value "IRF3205PBF")
      (footprint "eagle-import:PG-TO220-3_INF")
      (fields (field (name "COPYRIGHT") "Copyright (C) 2018 Accelerated Designs. All rights reserved"))
      (libsource (lib "eagle-import") (part "IRF3205PBF"))
    )
    (comp (ref "U6")
      (value "IRF3205PBF")
      (footprint "eagle-import:PG-TO220-3_INF")
      (fields (field (name "COPYRIGHT") "Copyright (C) 2018 Accelerated Designs. All rights reserved"))
      (libsource (lib "eagle-import") (part "IRF3205PBF"))
    )
    (comp (ref "U7")
      (value "IRF3205PBF")
      (footprint "eagle-import:PG-TO220-3_INF")
      (fields (field (name "COPYRIGHT") "Copyright (C) 2018 Accelerated Designs. All rights reserved"))
      (libsource (lib "eagle-import") (part "IRF3205PBF"))
    )
    (comp (ref "X1")
      (value "USB-A003")
      (footprint "eagle-import:USB-A003")
      (libsource (lib "eagle-import") (part "USB-A003"))
    )
    (comp (ref "XSTOP")
      (value "MA03-1")
      (footprint "eagle-import:MA03-1")
      (libsource (lib "eagle-import") (part "MA03-1"))
    )
    (comp (ref "YSTOP")
      (value "MA03-1")
      (footprint "eagle-import:MA03-1")
      (libsource (lib "eagle-import") (part "MA03-1"))
    )
    (comp (ref "ZSTOP")
      (value "MA03-1")
      (footprint "eagle-import:MA03-1")
      (libsource (lib "eagle-import") (part "MA03-1"))
    )
  )
  (nets
    (net (code "1") (name "+3.3V") (class "Default")
      (node (ref "C26") (pin "1") (pinfunction "1_1") (pintype "passive"))
      (node (ref "F3") (pin "2A") (pinfunction "2A_2A") (pintype "passive"))
      (node (ref "IC2") (pin "2") (pinfunction "OUT_2") (pintype "passive"))
      (node (ref "IC2") (pin "4") (pinfunction "OUT_4") (pintype "passive"))
      (node (ref "JP2") (pin "1") (pinfunction "1_1") (pintype "passive"))
      (node (ref "L2") (pin "1") (pinfunction "1_1") (pintype "passive"))
      (node (ref "L3") (pin "1") (pinfunction "1_1") (pintype "passive"))
      (node (ref "LED1") (pin "A") (pinfunction "A_A") (pintype "passive"))
      (node (ref "RV3") (pin "2") (pinfunction "2_2") (pintype "passive"))
    )
    (net (code "2") (name "+5V") (class "Default")
      (node (ref "C25") (pin "1") (pinfunction "1_1") (pintype "passive"))
      (node (ref "C32") (pin "2") (pinfunction "2_2") (pintype "passive"))
      (node (ref "C6") (pin "1") (pinfunction "1_1") (pintype "passive"))
      (node (ref "C8") (pin "2") (pinfunction "2_2") (pintype "passive"))
      (node (ref "EXP1") (pin "10") (pinfunction "KL_10") (pintype "passive"))
      (node (ref "EXPANSION3") (pin "10") (pinfunction "10_10") (pintype "passive"))
      (node (ref "EXPANSION3") (pin "9") (pinfunction "9_9") (pintype "passive"))
      (node (ref "EXTRA1") (pin "3") (pinfunction "3_3") (pintype "passive"))
      (node (ref "EXTRA2") (pin "3") (pinfunction "3_3") (pintype "passive"))
      (node (ref "EXTRA3") (pin "3") (pinfunction "3_3") (pintype "passive"))
      (node (ref "IC2") (pin "3") (pinfunction "IN_3") (pintype "input"))
      (node (ref "SV1") (pin "5") (pinfunction "5_5") (pintype "passive"))
      (node (ref "SV2") (pin "1") (pinfunction "1_1") (pintype "passive"))
      (node (ref "SW1") (pin "2") (pinfunction "2_2") (pintype "passive"))
      (node (ref "SW2") (pin "3") (pinfunction "3_3") (pintype "passive"))
      (node (ref "U3") (pin "14") (pinfunction "VCC_14") (pintype "power_in"))
      (node (ref "XSTOP") (pin "3") (pinfunction "3_3") (pintype "passive"))
      (node (ref "YSTOP") (pin "3") (pinfunction "3_3") (pintype "passive"))
      (node (ref "ZSTOP") (pin "3") (pinfunction "3_3") (pintype "passive"))
    )
    (net (code "3") (name "1A") (class "Default")
      (node (ref "SV17") (pin "10") (pinfunction "10_10") (pintype "passive"))
      (node (ref "SV18") (pin "2") (pinfunction "2_2") (pintype "passive"))
    )
    (net (code "4") (name "1B") (class "Default")
      (node (ref "SV17") (pin "12") (pinfunction "12_12") (pintype "passive"))
      (node (ref "SV18") (pin "1") (pinfunction "1_1") (pintype "passive"))
    )
    (net (code "5") (name "2A") (class "Default")
      (node (ref "SV17") (pin "8") (pinfunction "8_8") (pintype "passive"))
      (node (ref "SV18") (pin "3") (pinfunction "3_3") (pintype "passive"))
    )
    (net (code "6") (name "2B") (class "Default")
      (node (ref "SV17") (pin "6") (pinfunction "6_6") (pintype "passive"))
      (node (ref "SV18") (pin "4") (pinfunction "4_4") (pintype "passive"))
    )
    (net (code "7") (name "3.3VDC") (class "Default")
      (node (ref "C27") (pin "1") (pinfunction "1_1") (pintype "passive"))
      (node (ref "C9") (pin "1") (pinfunction "1_1") (pintype "passive"))
      (node (ref "EXPANSION3") (pin "11") (pinfunction "11_11") (pintype "passive"))
      (node (ref "EXPANSION3") (pin "12") (pinfunction "12_12") (pintype "passive"))
      (node (ref "F3") (pin "1A") (pinfunction "1A_1A") (pintype "passive"))
      (node (ref "Q5") (pin "2") (pinfunction "S_2") (pintype "passive"))
      (node (ref "R11") (pin "2") (pinfunction "2_2") (pintype "passive"))
      (node (ref "R13") (pin "1") (pinfunction "1_1") (pintype "passive"))
      (node (ref "R27") (pin "2") (pinfunction "2_2") (pintype "passive"))
      (node (ref "R29") (pin "2") (pinfunction "2_2") (pintype "passive"))
      (node (ref "R31") (pin "2") (pinfunction "2_2") (pintype "passive"))
      (node (ref "R33") (pin "2") (pinfunction "2_2") (pintype "passive"))
      (node (ref "R35") (pin "2") (pinfunction "2_2") (pintype "passive"))
      (node (ref "R45") (pin "1") (pinfunction "1_1") (pintype "passive"))
      (node (ref "R53") (pin "1") (pinfunction "1_1") (pintype "passive"))
      (node (ref "R61") (pin "1") (pinfunction "1_1") (pintype "passive"))
      (node (ref "R69") (pin "1") (pinfunction "1_1") (pintype "passive"))
      (node (ref "SV11") (pin "14") (pinfunction "14_14") (pintype "passive"))
      (node (ref "SV14") (pin "14") (pinfunction "14_14") (pintype "passive"))
      (node (ref "SV17") (pin "14") (pinfunction "14_14") (pintype "passive"))
      (node (ref "SV8") (pin "14") (pinfunction "14_14") (pintype "passive"))
      (node (ref "U$1") (pin "D2") (pinfunction "VCC_D2") (pintype "power_in"))
    )
    (net (code "8") (name "5V-OUT") (class "Default")
      (node (ref "C30") (pin "+") (pinfunction "+_+") (pintype "passive"))
      (node (ref "C31") (pin "2") (pinfunction "2_2") (pintype "passive"))
      (node (ref "L1") (pin "1") (pinfunction "1_1") (pintype "passive"))
      (node (ref "R18") (pin "A") (pinfunction "A_A") (pintype "passive"))
      (node (ref "SW1") (pin "3") (pinfunction "3_3") (pintype "passive"))
    )
    (net (code "9") (name "AGND") (class "Default")
      (node (ref "C22") (pin "1") (pinfunction "1_1") (pintype "passive"))
      (node (ref "C23") (pin "1") (pinfunction "1_1") (pintype "passive"))
      (node (ref "C24") (pin "1") (pinfunction "1_1") (pintype "passive"))
      (node (ref "L4") (pin "2") (pinfunction "2_2") (pintype "passive"))
      (node (ref "RV") (pin "1") (pinfunction "1_1") (pintype "passive"))
      (node (ref "RV1") (pin "1") (pinfunction "1_1") (pintype "passive"))
      (node (ref "RV2") (pin "1") (pinfunction "1_1") (pintype "passive"))
      (node (ref "THERMISTOR1") (pin "2") (pinfunction "S_2") (pintype "passive"))
      (node (ref "THERMISTOR2") (pin "2") (pinfunction "S_2") (pintype "passive"))
      (node (ref "THERMISTOR3") (pin "2") (pinfunction "S_2") (pintype "passive"))
      (node (ref "U1") (pin "11") (pinfunction "VSSA_11") (pintype "power_in"))
      (node (ref "U1") (pin "15") (pinfunction "VREFN_15") (pintype "input"))
    )
    (net (code "10") (name "BMA1") (class "Default")
      (node (ref "C105") (pin "2") (pinfunction "2_2") (pintype "passive"))
      (node (ref "IC7") (pin "40") (pinfunction "BMA1_40") (pintype "input"))
      (node (ref "Q21") (pin "10") (pinfunction "D1_10") (pintype "passive"))
      (node (ref "Q22") (pin "4") (pinfunction "S1_4") (pintype "passive"))
      (node (ref "SV17") (pin "9") (pinfunction "9_9") (pintype "passive"))
    )
    (net (code "11") (name "BMA2") (class "Default")
      (node (ref "C104") (pin "1") (pinfunction "1_1") (pintype "passive"))
      (node (ref "IC7") (pin "37") (pinfunction "BMA2_37") (pintype "input"))
      (node (ref "Q21") (pin "9") (pinfunction "D2_9") (pintype "passive"))
      (node (ref "Q22") (pin "5") (pinfunction "S2_5") (pintype "passive"))
      (node (ref "SV17") (pin "7") (pinfunction "7_7") (pintype "passive"))
    )
    (net (code "12") (name "BMB1") (class "Default")
      (node (ref "C101") (pin "2") (pinfunction "2_2") (pintype "passive"))
      (node (ref "IC7") (pin "48") (pinfunction "BMB1_48") (pintype "input"))
      (node (ref "Q19") (pin "10") (pinfunction "D1_10") (pintype "passive"))
      (node (ref "Q20") (pin "4") (pinfunction "S1_4") (pintype "passive"))
      (node (ref "SV17") (pin "11") (pinfunction "11_11") (pintype "passive"))
    )
    (net (code "13") (name "BMB2") (class "Default")
      (node (ref "C100") (pin "1") (pinfunction "1_1") (pintype "passive"))
      (node (ref "IC7") (pin "45") (pinfunction "BMB2_45") (pintype "input"))
      (node (ref "Q19") (pin "9") (pinfunction "D2_9") (pintype "passive"))
      (node (ref "Q20") (pin "5") (pinfunction "S2_5") (pintype "passive"))
      (node (ref "SV17") (pin "5") (pinfunction "5_5") (pintype "passive"))
    )
    (net (code "14") (name "CA1") (class "Default")
      (node (ref "C105") (pin "1") (pinfunction "1_1") (pintype "passive"))
      (node (ref "IC7") (pin "42") (pinfunction "CA1_42") (pintype "input"))
    )
    (net (code "15") (name "CA2") (class "Default")
      (node (ref "C104") (pin "2") (pinfunction "2_2") (pintype "passive"))
      (node (ref "IC7") (pin "35") (pinfunction "CA2_35") (pintype "input"))
    )
    (net (code "16") (name "CB1") (class "Default")
      (node (ref "C101") (pin "1") (pinfunction "1_1") (pintype "passive"))
      (node (ref "IC7") (pin "2") (pinfunction "CB1_2") (pintype "input"))
    )
    (net (code "17") (name "CB2") (class "Default")
      (node (ref "C100") (pin "2") (pinfunction "2_2") (pintype "passive"))
      (node (ref "IC7") (pin "43") (pinfunction "CB2_43") (pintype "input"))
    )
    (net (code "18") (name "DIR") (class "Default")
      (node (ref "IC7") (pin "18") (pinfunction "REFR_DIR_18") (pintype "input"))
      (node (ref "SV16") (pin "1") (pinfunction "1_1") (pintype "passive"))
    )
    (net (code "19") (name "DPIN_N") (class "Default")
      (node (ref "R8") (pin "1") (pinfunction "1_1") (pintype "passive"))
      (node (ref "U1") (pin "30") (pinfunction "P0[30]/USB_D-_30") (pintype "bidirectional"))
    )
    (net (code "20") (name "DPIN_P") (class "Default")
      (node (ref "R12") (pin "1") (pinfunction "1_1") (pintype "passive"))
      (node (ref "R7") (pin "1") (pinfunction "1_1") (pintype "passive"))
      (node (ref "U1") (pin "29") (pinfunction "P0[29]/USB_D+_29") (pintype "bidirectional"))
    )
    (net (code "21") (name "DRIVERGND") (class "Default")
      (node (ref "C102") (pin "1") (pinfunction "1_1") (pintype "passive"))
      (node (ref "C103") (pin "2") (pinfunction "2_2") (pintype "passive"))
      (node (ref "C106") (pin "1") (pinfunction "1_1") (pintype "passive"))
      (node (ref "C107") (pin "2") (pinfunction "2_2") (pintype "passive"))
      (node (ref "C92") (pin "2") (pinfunction "2_2") (pintype "passive"))
      (node (ref "C93") (pin "2") (pinfunction "2_2") (pintype "passive"))
      (node (ref "C95") (pin "2") (pinfunction "2_2") (pintype "passive"))
      (node (ref "C96") (pin "1") (pinfunction "1_1") (pintype "passive"))
      (node (ref "C98") (pin "2") (pinfunction "2_2") (pintype "passive"))
      (node (ref "C99") (pin "2") (pinfunction "2_2") (pintype "passive"))
      (node (ref "IC7") (pin "11") (pinfunction "TST_MODE_11") (pintype "input"))
      (node (ref "IC7") (pin "19") (pinfunction "GNDD_19") (pintype "power_in"))
      (node (ref "IC7") (pin "30") (pinfunction "GNDD_2_30") (pintype "power_in"))
      (node (ref "IC7") (pin "49") (pinfunction "GNDP_49") (pintype "power_in"))
      (node (ref "IC7") (pin "6") (pinfunction "GNDA_6") (pintype "power_in"))
      (node (ref "R62") (pin "1") (pinfunction "1_1") (pintype "passive"))
      (node (ref "R65") (pin "2") (pinfunction "2_2") (pintype "passive"))
      (node (ref "R67") (pin "1") (pinfunction "1_1") (pintype "passive"))
      (node (ref "R68") (pin "2") (pinfunction "2_2") (pintype "passive"))
      (node (ref "SV17") (pin "15") (pinfunction "15_15") (pintype "passive"))
      (node (ref "SV17") (pin "3") (pinfunction "3_3") (pintype "passive"))
    )
    (net (code "22") (name "DRIVERVBB") (class "Default")
      (node (ref "C103") (pin "1") (pinfunction "1_1") (pintype "passive"))
      (node (ref "C107") (pin "1") (pinfunction "1_1") (pintype "passive"))
      (node (ref "C92") (pin "1") (pinfunction "1_1") (pintype "passive"))
      (node (ref "C93") (pin "1") (pinfunction "1_1") (pintype "passive"))
      (node (ref "C95") (pin "1") (pinfunction "1_1") (pintype "passive"))
      (node (ref "C97") (pin "2") (pinfunction "2_2") (pintype "passive"))
      (node (ref "C99") (pin "1") (pinfunction "1_1") (pintype "passive"))
      (node (ref "IC7") (pin "33") (pinfunction "VS_33") (pintype "power_in"))
      (node (ref "IC7") (pin "4") (pinfunction "VSA_4") (pintype "power_in"))
      (node (ref "Q20") (pin "10") (pinfunction "D1_10") (pintype "passive"))
      (node (ref "Q20") (pin "9") (pinfunction "D2_9") (pintype "passive"))
      (node (ref "Q22") (pin "10") (pinfunction "D1_10") (pintype "passive"))
      (node (ref "Q22") (pin "9") (pinfunction "D2_9") (pintype "passive"))
      (node (ref "SV17") (pin "1") (pinfunction "1_1") (pintype "passive"))
    )
    (net (code "23") (name "DRIVERVSS") (class "Default")
      (node (ref "C98") (pin "1") (pinfunction "1_1") (pintype "passive"))
      (node (ref "IC7") (pin "20") (pinfunction "VCC_IO_20") (pintype "power_in"))
      (node (ref "IC7") (pin "21") (pinfunction "SD_MODE_21") (pintype "input"))
      (node (ref "IC7") (pin "22") (pinfunction "SPI_MODE_22") (pintype "input"))
      (node (ref "SV17") (pin "13") (pinfunction "13_13") (pintype "passive"))
    )
    (net (code "24") (name "D_N") (class "Default")
      (node (ref "R8") (pin "2") (pinfunction "2_2") (pintype "passive"))
      (node (ref "U2") (pin "6") (pinfunction "I/O_6") (pintype "bidirectional"))
      (node (ref "X1") (pin "3") (pinfunction "3_3") (pintype "passive"))
    )
    (net (code "25") (name "D_P") (class "Default")
      (node (ref "R7") (pin "2") (pinfunction "2_2") (pintype "passive"))
      (node (ref "U2") (pin "1") (pinfunction "I/O_1") (pintype "bidirectional"))
      (node (ref "X1") (pin "2") (pinfunction "2_2") (pintype "passive"))
    )
    (net (code "26") (name "E0-DIR") (class "Default")
      (node (ref "SV16") (pin "2") (pinfunction "2_2") (pintype "passive"))
      (node (ref "U1") (pin "49") (pinfunction "P0[11]/RXD2/SCL2/MAT3[1]_49") (pintype "bidirectional"))
    )
    (net (code "27") (name "E0-RX") (class "Default")
      (node (ref "SV16") (pin "10") (pinfunction "10_10") (pintype "passive"))
      (node (ref "U1") (pin "93") (pinfunction "P1[4]/ENET_TX_EN_93") (pintype "bidirectional"))
    )
    (net (code "28") (name "E0-SLP") (class "Default")
      (node (ref "SV16") (pin "6") (pinfunction "6_6") (pintype "passive"))
    )
    (net (code "29") (name "E0-STP") (class "Default")
      (node (ref "SV16") (pin "4") (pinfunction "4_4") (pintype "passive"))
      (node (ref "U1") (pin "50") (pinfunction "P2[13]/~{EINT3/I2STX_SDA}_50") (pintype "bidirectional"))
    )
    (net (code "30") (name "ENABLE") (class "Default")
      (node (ref "IC7") (pin "28") (pinfunction "DRV_ENN_28") (pintype "input"))
      (node (ref "SV16") (pin "15") (pinfunction "15_15") (pintype "passive"))
    )
    (net (code "31") (name "ESP_N") (class "Default")
      (node (ref "U$1") (pin "A2") (pinfunction "UTXD_A2") (pintype "bidirectional"))
      (node (ref "U1") (pin "85") (pinfunction "P4[29]/TX_MCLK/MAT2[1]/RXD3_85") (pintype "bidirectional"))
    )
    (net (code "32") (name "ESP_P") (class "Default")
      (node (ref "U$1") (pin "D1") (pinfunction "URXD_D1") (pintype "bidirectional"))
      (node (ref "U1") (pin "82") (pinfunction "P4[28]/RX_MCLK/MAT2[0]/TXD3_82") (pintype "bidirectional"))
    )
    (net (code "33") (name "EXTRA1") (class "Default")
      (node (ref "R32") (pin "2") (pinfunction "2_2") (pintype "passive"))
      (node (ref "U1") (pin "40") (pinfunction "P1[26]/MCOB1/PWM1[6]/CAP0[0]_40") (pintype "bidirectional"))
    )
    (net (code "34") (name "EXTRA2") (class "Default")
      (node (ref "R34") (pin "2") (pinfunction "2_2") (pintype "passive"))
      (node (ref "U1") (pin "39") (pinfunction "P1[25]/MCOA1/MAT1[1]_39") (pintype "bidirectional"))
    )
    (net (code "35") (name "FANMOSFET") (class "Default")
      (node (ref "U3") (pin "11") (pinfunction "Y4_11") (pintype "output"))
      (node (ref "U6") (pin "1") (pinfunction "G_1") (pintype "passive"))
      (node (ref "U7") (pin "1") (pinfunction "G_1") (pintype "passive"))
    )
    (net (code "36") (name "FANPWM") (class "Default")
      (node (ref "R23") (pin "1") (pinfunction "1_1") (pintype "passive"))
      (node (ref "U1") (pin "70") (pinfunction "P2[3]/PWM1[4]/DCD1/TRACEDATA[2]_70") (pintype "bidirectional"))
      (node (ref "U3") (pin "12") (pinfunction "A4_12") (pintype "input"))
    )
    (net (code "37") (name "GND") (class "Default")
      (node (ref "C19") (pin "1") (pinfunction "1_1") (pintype "passive"))
      (node (ref "C20") (pin "1") (pinfunction "1_1") (pintype "passive"))
      (node (ref "C21") (pin "2") (pinfunction "2_2") (pintype "passive"))
      (node (ref "C25") (pin "2") (pinfunction "2_2") (pintype "passive"))
      (node (ref "C26") (pin "2") (pinfunction "2_2") (pintype "passive"))
      (node (ref "C27") (pin "2") (pinfunction "2_2") (pintype "passive"))
      (node (ref "C28") (pin "-") (pinfunction "-_-") (pintype "passive"))
      (node (ref "C29") (pin "2") (pinfunction "2_2") (pintype "passive"))
      (node (ref "C30") (pin "-") (pinfunction "-_-") (pintype "passive"))
      (node (ref "C32") (pin "1") (pinfunction "1_1") (pintype "passive"))
      (node (ref "C33") (pin "1") (pinfunction "1_1") (pintype "passive"))
      (node (ref "C34") (pin "1") (pinfunction "1_1") (pintype "passive"))
      (node (ref "C35") (pin "1") (pinfunction "1_1") (pintype "passive"))
      (node (ref "C36") (pin "1") (pinfunction "1_1") (pintype "passive"))
      (node (ref "C37") (pin "1") (pinfunction "1_1") (pintype "passive"))
      (node (ref "C38") (pin "1") (pinfunction "1_1") (pintype "passive"))
      (node (ref "C39") (pin "1") (pinfunction "1_1") (pintype "passive"))
      (node (ref "C40") (pin "2") (pinfunction "2_2") (pintype "passive"))
      (node (ref "C41") (pin "1") (pinfunction "1_1") (pintype "passive"))
      (node (ref "C42") (pin "1") (pinfunction "1_1") (pintype "passive"))
      (node (ref "C6") (pin "2") (pinfunction "2_2") (pintype "passive"))
      (node (ref "C8") (pin "1") (pinfunction "1_1") (pintype "passive"))
      (node (ref "C9") (pin "2") (pinfunction "2_2") (pintype "passive"))
      (node (ref "D2") (pin "A") (pinfunction "A_A") (pintype "passive"))
      (node (ref "EXP1") (pin "9") (pinfunction "KL_9") (pintype "passive"))
      (node (ref "EXP2") (pin "9") (pinfunction "KL_9") (pintype "passive"))
      (node (ref "EXPANSION3") (pin "1") (pinfunction "1_1") (pintype "passive"))
      (node (ref "EXPANSION3") (pin "2") (pinfunction "2_2") (pintype "passive"))
      (node (ref "EXTRA1") (pin "2") (pinfunction "2_2") (pintype "passive"))
      (node (ref "EXTRA2") (pin "2") (pinfunction "2_2") (pintype "passive"))
      (node (ref "EXTRA3") (pin "2") (pinfunction "2_2") (pintype "passive"))
      (node (ref "FANS") (pin "2") (pinfunction "2_2") (pintype "passive"))
      (node (ref "FANS") (pin "4") (pinfunction "4_4") (pintype "passive"))
      (node (ref "IC2") (pin "1") (pinfunction "GND_1") (pintype "input"))
      (node (ref "IC3") (pin "3") (pinfunction "GND_3") (pintype "power_in"))
      (node (ref "IC3") (pin "5") (pinfunction "~{ON}/OFF_5") (pintype "input"))
      (node (ref "JP1") (pin "1") (pinfunction "1_1") (pintype "passive"))
      (node (ref "JP2") (pin "3") (pinfunction "3_3") (pintype "passive"))
      (node (ref "L4") (pin "1") (pinfunction "1_1") (pintype "passive"))
      (node (ref "LED1") (pin "K") (pinfunction "C_K") (pintype "passive"))
      (node (ref "MOSFET1") (pin "3") (pinfunction "S_3") (pintype "passive"))
      (node (ref "NEOPIXEL") (pin "2") (pinfunction "2_2") (pintype "passive"))
      (node (ref "POWER") (pin "2") (pinfunction "KL_2") (pintype "passive"))
      (node (ref "R17") (pin "2") (pinfunction "2_2") (pintype "passive"))
      (node (ref "R20") (pin "2") (pinfunction "2_2") (pintype "passive"))
      (node (ref "R21") (pin "2") (pinfunction "2_2") (pintype "passive"))
      (node (ref "R22") (pin "2") (pinfunction "2_2") (pintype "passive"))
      (node (ref "R23") (pin "2") (pinfunction "2_2") (pintype "passive"))
      (node (ref "R9") (pin "2") (pinfunction "2_2") (pintype "passive"))
      (node (ref "RV3") (pin "1") (pinfunction "1_1") (pintype "passive"))
      (node (ref "RV4") (pin "2") (pinfunction "2_2") (pintype "passive"))
      (node (ref "RV5") (pin "2") (pinfunction "2_2") (pintype "passive"))
      (node (ref "RV6") (pin "2") (pinfunction "2_2") (pintype "passive"))
      (node (ref "RV7") (pin "2") (pinfunction "2_2") (pintype "passive"))
      (node (ref "RV8") (pin "2") (pinfunction "2_2") (pintype "passive"))
      (node (ref "S1") (pin "3") (pinfunction "P_3") (pintype "passive"))
      (node (ref "SERVO") (pin "2") (pinfunction "2_2") (pintype "passive"))
      (node (ref "SV1") (pin "4") (pinfunction "4_4") (pintype "passive"))
      (node (ref "SV11") (pin "16") (pinfunction "16_16") (pintype "passive"))
      (node (ref "SV11") (pin "4") (pinfunction "4_4") (pintype "passive"))
      (node (ref "SV14") (pin "16") (pinfunction "16_16") (pintype "passive"))
      (node (ref "SV14") (pin "4") (pinfunction "4_4") (pintype "passive"))
      (node (ref "SV17") (pin "16") (pinfunction "16_16") (pintype "passive"))
      (node (ref "SV17") (pin "4") (pinfunction "4_4") (pintype "passive"))
      (node (ref "SV2") (pin "2") (pinfunction "2_2") (pintype "passive"))
      (node (ref "SV3") (pin "2") (pinfunction "2_2") (pintype "passive"))
      (node (ref "SV3") (pin "4") (pinfunction "4_4") (pintype "passive"))
      (node (ref "SV3") (pin "6") (pinfunction "6_6") (pintype "passive"))
      (node (ref "SV8") (pin "16") (pinfunction "16_16") (pintype "passive"))
      (node (ref "SV8") (pin "4") (pinfunction "4_4") (pintype "passive"))
      (node (ref "U$1") (pin "A1") (pinfunction "GND_A1") (pintype "power_in"))
      (node (ref "U1") (pin "31") (pinfunction "VSS_2_31") (pintype "power_in"))
      (node (ref "U1") (pin "41") (pinfunction "VSS_3_41") (pintype "power_in"))
      (node (ref "U1") (pin "55") (pinfunction "VSS_4_55") (pintype "power_in"))
      (node (ref "U1") (pin "72") (pinfunction "VSS_5_72") (pintype "power_in"))
      (node (ref "U1") (pin "83") (pinfunction "VSS_6_83") (pintype "power_in"))
      (node (ref "U1") (pin "97") (pinfunction "VSS_97") (pintype "power_in"))
      (node (ref "U3") (pin "1") (pinfunction "OE1_1") (pintype "input"))
      (node (ref "U3") (pin "10") (pinfunction "OE3_10") (pintype "input"))
      (node (ref "U3") (pin "13") (pinfunction "OE4_13") (pintype "input"))
      (node (ref "U3") (pin "4") (pinfunction "OE2_4") (pintype "input"))
      (node (ref "U3") (pin "7") (pinfunction "GND_7") (pintype "power_in"))
      (node (ref "U4") (pin "2") (pinfunction "S_2") (pintype "passive"))
      (node (ref "U5") (pin "2") (pinfunction "S_2") (pintype "passive"))
      (node (ref "U6") (pin "2") (pinfunction "S_2") (pintype "passive"))
      (node (ref "U7") (pin "2") (pinfunction "S_2") (pintype "passive"))
      (node (ref "X1") (pin "1") (pinfunction "1_1") (pintype "passive"))
      (node (ref "XSTOP") (pin "2") (pinfunction "2_2") (pintype "passive"))
      (node (ref "YSTOP") (pin "2") (pinfunction "2_2") (pintype "passive"))
      (node (ref "ZSTOP") (pin "2") (pinfunction "2_2") (pintype "passive"))
    )
    (net (code "38") (name "HA1") (class "Default")
      (node (ref "IC7") (pin "41") (pinfunction "HA1_41") (pintype "output"))
      (node (ref "Q22") (pin "1") (pinfunction "G1_1") (pintype "passive"))
    )
    (net (code "39") (name "HA2") (class "Default")
      (node (ref "IC7") (pin "36") (pinfunction "HA2_36") (pintype "output"))
      (node (ref "Q22") (pin "8") (pinfunction "G2_8") (pintype "passive"))
    )
    (net (code "40") (name "HB1") (class "Default")
      (node (ref "IC7") (pin "1") (pinfunction "HB1_1") (pintype "output"))
      (node (ref "Q20") (pin "1") (pinfunction "G1_1") (pintype "passive"))
    )
    (net (code "41") (name "HB2") (class "Default")
      (node (ref "IC7") (pin "44") (pinfunction "HB2_44") (pintype "output"))
      (node (ref "Q20") (pin "8") (pinfunction "G2_8") (pintype "passive"))
    )
    (net (code "42") (name "HBMOSFET") (class "Default")
      (node (ref "MOSFET1") (pin "1") (pinfunction "G_1") (pintype "passive"))
      (node (ref "U3") (pin "8") (pinfunction "Y3_8") (pintype "output"))
    )
    (net (code "43") (name "HBPWM") (class "Default")
      (node (ref "R20") (pin "1") (pinfunction "1_1") (pintype "passive"))
      (node (ref "U1") (pin "68") (pinfunction "P2[5]/PWM1[6]/DTR1/TRACEDATA[0]_68") (pintype "bidirectional"))
      (node (ref "U3") (pin "9") (pinfunction "A3_9") (pintype "input"))
    )
    (net (code "44") (name "HEMOSFET1") (class "Default")
      (node (ref "U3") (pin "6") (pinfunction "Y2_6") (pintype "output"))
      (node (ref "U5") (pin "1") (pinfunction "G_1") (pintype "passive"))
    )
    (net (code "45") (name "HEMOSFET2") (class "Default")
      (node (ref "U3") (pin "3") (pinfunction "Y1_3") (pintype "output"))
      (node (ref "U4") (pin "1") (pinfunction "G_1") (pintype "passive"))
    )
    (net (code "46") (name "HEPWM1") (class "Default")
      (node (ref "R21") (pin "1") (pinfunction "1_1") (pintype "passive"))
      (node (ref "U1") (pin "66") (pinfunction "P2[7]/RD2/RTS1_66") (pintype "bidirectional"))
      (node (ref "U3") (pin "5") (pinfunction "A2_5") (pintype "input"))
    )
    (net (code "47") (name "HEPWM2") (class "Default")
      (node (ref "R22") (pin "1") (pinfunction "1_1") (pintype "passive"))
      (node (ref "U1") (pin "69") (pinfunction "P2[4]/PWM1[5]/DSR1/TRACEDATA[1]_69") (pintype "bidirectional"))
      (node (ref "U3") (pin "2") (pinfunction "A1_2") (pintype "input"))
    )
    (net (code "48") (name "LA1") (class "Default")
      (node (ref "IC7") (pin "39") (pinfunction "LA1_39") (pintype "output"))
      (node (ref "Q21") (pin "1") (pinfunction "G1_1") (pintype "passive"))
    )
    (net (code "49") (name "LA2") (class "Default")
      (node (ref "IC7") (pin "38") (pinfunction "LA2_38") (pintype "output"))
      (node (ref "Q21") (pin "8") (pinfunction "G2_8") (pintype "passive"))
    )
    (net (code "50") (name "LB1") (class "Default")
      (node (ref "IC7") (pin "47") (pinfunction "LB1_47") (pintype "output"))
      (node (ref "Q19") (pin "1") (pinfunction "G1_1") (pintype "passive"))
    )
    (net (code "51") (name "LB2") (class "Default")
      (node (ref "IC7") (pin "46") (pinfunction "LB2_46") (pintype "output"))
      (node (ref "Q19") (pin "8") (pinfunction "G2_8") (pintype "passive"))
    )
    (net (code "52") (name "MISO") (class "Default")
      (node (ref "EXPANSION3") (pin "5") (pinfunction "5_5") (pintype "passive"))
      (node (ref "U1") (pin "77") (pinfunction "P0[8]/I2STX_WS/MISO1/MAT2[2]_77") (pintype "bidirectional"))
    )
    (net (code "53") (name "MOSI") (class "Default")
      (node (ref "EXPANSION3") (pin "3") (pinfunction "3_3") (pintype "passive"))
      (node (ref "U1") (pin "76") (pinfunction "P0[9]/I2STX_SDA/MOSI1/MAT2[3]_76") (pintype "bidirectional"))
    )
    (net (code "54") (name "MOT-EN") (class "Default")
      (node (ref "R3") (pin "1") (pinfunction "1_1") (pintype "passive"))
      (node (ref "R69") (pin "2") (pinfunction "2_2") (pintype "passive"))
      (node (ref "SV16") (pin "16") (pinfunction "16_16") (pintype "passive"))
    )
    (net (code "55") (name "MOT-MISO") (class "Default")
      (node (ref "SV10") (pin "8") (pinfunction "8_8") (pintype "passive"))
      (node (ref "SV13") (pin "8") (pinfunction "8_8") (pintype "passive"))
      (node (ref "SV16") (pin "8") (pinfunction "8_8") (pintype "passive"))
      (node (ref "SV7") (pin "8") (pinfunction "8_8") (pintype "passive"))
      (node (ref "U1") (pin "80") (pinfunction "P0[5]/I2SRX_WS/TD2/CAP2[1]_80") (pintype "bidirectional"))
    )
    (net (code "56") (name "MOT-MOSI") (class "Default")
      (node (ref "SV10") (pin "14") (pinfunction "14_14") (pintype "passive"))
      (node (ref "SV13") (pin "14") (pinfunction "14_14") (pintype "passive"))
      (node (ref "SV16") (pin "14") (pinfunction "14_14") (pintype "passive"))
      (node (ref "SV7") (pin "14") (pinfunction "14_14") (pintype "passive"))
      (node (ref "U1") (pin "86") (pinfunction "P1[17]/ENET_MDIO_86") (pintype "bidirectional"))
    )
    (net (code "57") (name "MOT-SCK") (class "Default")
      (node (ref "SV10") (pin "12") (pinfunction "12_12") (pintype "passive"))
      (node (ref "SV13") (pin "12") (pinfunction "12_12") (pintype "passive"))
      (node (ref "SV16") (pin "12") (pinfunction "12_12") (pintype "passive"))
      (node (ref "SV7") (pin "12") (pinfunction "12_12") (pintype "passive"))
      (node (ref "U1") (pin "81") (pinfunction "P0[4]/I2SRX_CLK/RD2/CAP2[0]_81") (pintype "bidirectional"))
    )
    (net (code "58") (name "MOTORMISO") (class "Default")
      (node (ref "IC7") (pin "16") (pinfunction "SDO_CFG0_16") (pintype "output"))
      (node (ref "SV16") (pin "7") (pinfunction "7_7") (pintype "passive"))
    )
    (net (code "59") (name "MOTORMOSI") (class "Default")
      (node (ref "IC7") (pin "15") (pinfunction "SDI_CFG1_15") (pintype "input"))
      (node (ref "SV16") (pin "13") (pinfunction "13_13") (pintype "passive"))
    )
    (net (code "60") (name "MOTORSCK") (class "Default")
      (node (ref "IC7") (pin "14") (pinfunction "SCK_CFG2_14") (pintype "input"))
      (node (ref "SV16") (pin "11") (pinfunction "11_11") (pintype "passive"))
    )
    (net (code "61") (name "N$1") (class "Default")
      (node (ref "EXP1") (pin "1") (pinfunction "KL_1") (pintype "passive"))
      (node (ref "U1") (pin "21") (pinfunction "P1[30]/VBUS/AD0[4]_21") (pintype "bidirectional"))
    )
    (net (code "62") (name "N$2") (class "Default")
      (node (ref "EXP1") (pin "2") (pinfunction "KL_2") (pintype "passive"))
      (node (ref "U1") (pin "24") (pinfunction "P0[28]/SCL0/USB_SCL_24") (pintype "bidirectional"))
    )
    (net (code "63") (name "N$3") (class "Default")
      (node (ref "EXP1") (pin "3") (pinfunction "KL_3") (pintype "passive"))
      (node (ref "U1") (pin "32") (pinfunction "P1[18]/USB_UP_LED/PWM1[1]/CAP1[0]_32") (pintype "bidirectional"))
    )
    (net (code "64") (name "N$4") (class "Default")
      (node (ref "EXP1") (pin "4") (pinfunction "KL_4") (pintype "passive"))
      (node (ref "U1") (pin "33") (pinfunction "P1[19]/MCOA0/~{USB_PPWR/CAP1[1]}_33") (pintype "bidirectional"))
    )
    (net (code "65") (name "N$5") (class "Default")
      (node (ref "EXP1") (pin "5") (pinfunction "KL_5") (pintype "passive"))
      (node (ref "U1") (pin "34") (pinfunction "P1[20]/MCI0/PWM1[2]/SCK0_34") (pintype "bidirectional"))
    )
    (net (code "66") (name "N$6") (class "Default")
      (node (ref "EXP1") (pin "6") (pinfunction "KL_6") (pintype "passive"))
      (node (ref "U1") (pin "35") (pinfunction "P1[21]/~{MCABORT/PWM1[3]/SSEL0}_35") (pintype "bidirectional"))
    )
    (net (code "67") (name "N$7") (class "Default")
      (node (ref "EXP1") (pin "7") (pinfunction "KL_7") (pintype "passive"))
      (node (ref "U1") (pin "36") (pinfunction "P1[22]/MCOB0/USB_PWRD/MAT1[0]_36") (pintype "bidirectional"))
    )
    (net (code "68") (name "N$8") (class "Default")
      (node (ref "EXP1") (pin "8") (pinfunction "KL_8") (pintype "passive"))
      (node (ref "U1") (pin "37") (pinfunction "P1[23]/MCI1/PWM1[4]/MISO0_37") (pintype "bidirectional"))
    )
    (net (code "69") (name "N$11") (class "Default")
      (node (ref "EXP2") (pin "1") (pinfunction "KL_1") (pintype "passive"))
      (node (ref "U1") (pin "61") (pinfunction "P0[17]/CTS1/MISO0/MISO_61") (pintype "bidirectional"))
    )
    (net (code "70") (name "N$12") (class "Default")
      (node (ref "EXP2") (pin "2") (pinfunction "KL_2") (pintype "passive"))
      (node (ref "U1") (pin "62") (pinfunction "P0[15]/TXD1/SCK0/SCK_62") (pintype "bidirectional"))
    )
    (net (code "71") (name "N$13") (class "Default")
      (node (ref "EXP2") (pin "3") (pinfunction "KL_3") (pintype "passive"))
      (node (ref "U1") (pin "26") (pinfunction "P3[26]/STCLK/MAT0[1]/PWM1[3]_26") (pintype "bidirectional"))
    )
    (net (code "72") (name "N$14") (class "Default")
      (node (ref "EXP2") (pin "4") (pinfunction "KL_4") (pintype "passive"))
      (node (ref "U1") (pin "63") (pinfunction "P0[16]/RXD1/SSEL0/SSEL_63") (pintype "bidirectional"))
    )
    (net (code "73") (name "N$15") (class "Default")
      (node (ref "EXP2") (pin "5") (pinfunction "KL_5") (pintype "passive"))
      (node (ref "U1") (pin "27") (pinfunction "P3[25]/MAT0[0]/PWM1[2]_27") (pintype "bidirectional"))
    )
    (net (code "74") (name "N$16") (class "Default")
      (node (ref "EXP2") (pin "6") (pinfunction "KL_6") (pintype "passive"))
      (node (ref "U1") (pin "60") (pinfunction "P0[18]/DCD1/MOSI0/MOSI_60") (pintype "bidirectional"))
    )
    (net (code "75") (name "N$17") (class "Default")
      (node (ref "EXP2") (pin "7") (pinfunction "KL_7") (pintype "passive"))
      (node (ref "U1") (pin "20") (pinfunction "P1[31]/SCK1/AD0[5]_20") (pintype "bidirectional"))
    )
    (net (code "76") (name "N$41") (class "Default")
      (node (ref "HOTEND") (pin "4") (pinfunction "KL_4") (pintype "passive"))
      (node (ref "U4") (pin "3") (pinfunction "D_3") (pintype "passive"))
    )
    (net (code "77") (name "N$51") (class "Default")
      (node (ref "R26") (pin "1") (pinfunction "1_1") (pintype "passive"))
      (node (ref "R27") (pin "1") (pinfunction "1_1") (pintype "passive"))
      (node (ref "RV4") (pin "1") (pinfunction "1_1") (pintype "passive"))
      (node (ref "XSTOP") (pin "1") (pinfunction "1_1") (pintype "passive"))
    )
    (net (code "78") (name "N$52") (class "Default")
      (node (ref "EXTRA1") (pin "1") (pinfunction "1_1") (pintype "passive"))
      (node (ref "R32") (pin "1") (pinfunction "1_1") (pintype "passive"))
      (node (ref "R33") (pin "1") (pinfunction "1_1") (pintype "passive"))
      (node (ref "RV7") (pin "1") (pinfunction "1_1") (pintype "passive"))
    )
    (net (code "79") (name "N$55") (class "Default")
      (node (ref "R28") (pin "1") (pinfunction "1_1") (pintype "passive"))
      (node (ref "R29") (pin "1") (pinfunction "1_1") (pintype "passive"))
      (node (ref "RV5") (pin "1") (pinfunction "1_1") (pintype "passive"))
      (node (ref "YSTOP") (pin "1") (pinfunction "1_1") (pintype "passive"))
    )
    (net (code "80") (name "N$56") (class "Default")
      (node (ref "R30") (pin "1") (pinfunction "1_1") (pintype "passive"))
      (node (ref "R31") (pin "1") (pinfunction "1_1") (pintype "passive"))
      (node (ref "RV6") (pin "1") (pinfunction "1_1") (pintype "passive"))
      (node (ref "ZSTOP") (pin "1") (pinfunction "1_1") (pintype "passive"))
    )
    (net (code "81") (name "N$61") (class "Default")
      (node (ref "EXTRA2") (pin "1") (pinfunction "1_1") (pintype "passive"))
      (node (ref "R34") (pin "1") (pinfunction "1_1") (pintype "passive"))
      (node (ref "R35") (pin "1") (pinfunction "1_1") (pintype "passive"))
      (node (ref "RV8") (pin "1") (pinfunction "1_1") (pintype "passive"))
    )
    (net (code "82") (name "NPOWER") (class "Default")
      (node (ref "NEOPIXEL") (pin "3") (pinfunction "3_3") (pintype "passive"))
      (node (ref "SERVO") (pin "3") (pinfunction "3_3") (pintype "passive"))
      (node (ref "SW2") (pin "2") (pinfunction "2_2") (pintype "passive"))
    )
    (net (code "83") (name "Net-(HEATBEDA-KL)") (class "Default")
      (node (ref "HEATBED") (pin "1") (pinfunction "KL_1") (pintype "passive"))
      (node (ref "MOSFET1") (pin "2") (pinfunction "D_2") (pintype "passive"))
    )
    (net (code "84") (name "Net-(HOTENDB-KL)") (class "Default")
      (node (ref "HOTEND") (pin "2") (pinfunction "KL_2") (pintype "passive"))
      (node (ref "U5") (pin "3") (pinfunction "D_3") (pintype "passive"))
    )
    (net (code "85") (name "Net-(IC3-FB)") (class "Default")
      (node (ref "C31") (pin "1") (pinfunction "1_1") (pintype "passive"))
      (node (ref "IC3") (pin "4") (pinfunction "FB_4") (pintype "input"))
      (node (ref "R17") (pin "1") (pinfunction "1_1") (pintype "passive"))
      (node (ref "R18") (pin "S") (pinfunction "S_S") (pintype "passive"))
    )
    (net (code "86") (name "Net-(IC3-OUT)") (class "Default")
      (node (ref "D2") (pin "C") (pinfunction "C_C") (pintype "passive"))
      (node (ref "IC3") (pin "2") (pinfunction "OUT_2") (pintype "output"))
      (node (ref "L1") (pin "2") (pinfunction "2_2") (pintype "passive"))
    )
    (net (code "87") (name "Net-(IC3-VIN)") (class "Default")
      (node (ref "C28") (pin "+") (pinfunction "+_+") (pintype "passive"))
      (node (ref "C29") (pin "1") (pinfunction "1_1") (pintype "passive"))
      (node (ref "D1") (pin "C") (pinfunction "C_C") (pintype "passive"))
      (node (ref "IC3") (pin "1") (pinfunction "VIN_1") (pintype "input"))
    )
    (net (code "88") (name "Net-(IC4-5VOUT)") (class "Default")
      (node (ref "C54") (pin "2") (pinfunction "2_2") (pintype "passive"))
      (node (ref "IC4") (pin "5") (pinfunction "5VOUT_5") (pintype "bidirectional"))
      (node (ref "R42") (pin "2") (pinfunction "2_2") (pintype "passive"))
    )
    (net (code "89") (name "Net-(IC4-12VOUT)") (class "Default")
      (node (ref "C48") (pin "2") (pinfunction "2_2") (pintype "passive"))
      (node (ref "IC4") (pin "3") (pinfunction "12VOUT_3") (pintype "bidirectional"))
    )
    (net (code "90") (name "Net-(IC4-CPI)") (class "Default")
      (node (ref "C46") (pin "2") (pinfunction "2_2") (pintype "passive"))
      (node (ref "IC4") (pin "32") (pinfunction "CPI_32") (pintype "input"))
    )
    (net (code "91") (name "Net-(IC4-CPO)") (class "Default")
      (node (ref "C46") (pin "1") (pinfunction "1_1") (pintype "passive"))
      (node (ref "IC4") (pin "31") (pinfunction "CPO_31") (pintype "input"))
    )
    (net (code "92") (name "Net-(IC4-VCC)") (class "Default")
      (node (ref "C58") (pin "2") (pinfunction "2_2") (pintype "passive"))
      (node (ref "IC4") (pin "29") (pinfunction "VCC_29") (pintype "power_in"))
      (node (ref "R42") (pin "1") (pinfunction "1_1") (pintype "passive"))
    )
    (net (code "93") (name "Net-(IC4-VCP)") (class "Default")
      (node (ref "C49") (pin "1") (pinfunction "1_1") (pintype "passive"))
      (node (ref "IC4") (pin "34") (pinfunction "VCP_34") (pintype "input"))
    )
    (net (code "94") (name "Net-(IC5-5VOUT)") (class "Default")
      (node (ref "C70") (pin "2") (pinfunction "2_2") (pintype "passive"))
      (node (ref "IC5") (pin "5") (pinfunction "5VOUT_5") (pintype "bidirectional"))
      (node (ref "R50") (pin "2") (pinfunction "2_2") (pintype "passive"))
    )
    (net (code "95") (name "Net-(IC5-12VOUT)") (class "Default")
      (node (ref "C64") (pin "2") (pinfunction "2_2") (pintype "passive"))
      (node (ref "IC5") (pin "3") (pinfunction "12VOUT_3") (pintype "bidirectional"))
    )
    (net (code "96") (name "Net-(IC5-CPI)") (class "Default")
      (node (ref "C62") (pin "2") (pinfunction "2_2") (pintype "passive"))
      (node (ref "IC5") (pin "32") (pinfunction "CPI_32") (pintype "input"))
    )
    (net (code "97") (name "Net-(IC5-CPO)") (class "Default")
      (node (ref "C62") (pin "1") (pinfunction "1_1") (pintype "passive"))
      (node (ref "IC5") (pin "31") (pinfunction "CPO_31") (pintype "input"))
    )
    (net (code "98") (name "Net-(IC5-VCC)") (class "Default")
      (node (ref "C74") (pin "2") (pinfunction "2_2") (pintype "passive"))
      (node (ref "IC5") (pin "29") (pinfunction "VCC_29") (pintype "power_in"))
      (node (ref "R50") (pin "1") (pinfunction "1_1") (pintype "passive"))
    )
    (net (code "99") (name "Net-(IC5-VCP)") (class "Default")
      (node (ref "C65") (pin "1") (pinfunction "1_1") (pintype "passive"))
      (node (ref "IC5") (pin "34") (pinfunction "VCP_34") (pintype "input"))
    )
    (net (code "100") (name "Net-(IC6-5VOUT)") (class "Default")
      (node (ref "C86") (pin "2") (pinfunction "2_2") (pintype "passive"))
      (node (ref "IC6") (pin "5") (pinfunction "5VOUT_5") (pintype "bidirectional"))
      (node (ref "R58") (pin "2") (pinfunction "2_2") (pintype "passive"))
    )
    (net (code "101") (name "Net-(IC6-12VOUT)") (class "Default")
      (node (ref "C80") (pin "2") (pinfunction "2_2") (pintype "passive"))
      (node (ref "IC6") (pin "3") (pinfunction "12VOUT_3") (pintype "bidirectional"))
    )
    (net (code "102") (name "Net-(IC6-CPI)") (class "Default")
      (node (ref "C78") (pin "2") (pinfunction "2_2") (pintype "passive"))
      (node (ref "IC6") (pin "32") (pinfunction "CPI_32") (pintype "input"))
    )
    (net (code "103") (name "Net-(IC6-CPO)") (class "Default")
      (node (ref "C78") (pin "1") (pinfunction "1_1") (pintype "passive"))
      (node (ref "IC6") (pin "31") (pinfunction "CPO_31") (pintype "input"))
    )
    (net (code "104") (name "Net-(IC6-VCC)") (class "Default")
      (node (ref "C90") (pin "2") (pinfunction "2_2") (pintype "passive"))
      (node (ref "IC6") (pin "29") (pinfunction "VCC_29") (pintype "power_in"))
      (node (ref "R58") (pin "1") (pinfunction "1_1") (pintype "passive"))
    )
    (net (code "105") (name "Net-(IC6-VCP)") (class "Default")
      (node (ref "C81") (pin "1") (pinfunction "1_1") (pintype "passive"))
      (node (ref "IC6") (pin "34") (pinfunction "VCP_34") (pintype "input"))
    )
    (net (code "106") (name "Net-(IC7-5VOUT)") (class "Default")
      (node (ref "C102") (pin "2") (pinfunction "2_2") (pintype "passive"))
      (node (ref "IC7") (pin "5") (pinfunction "5VOUT_5") (pintype "bidirectional"))
      (node (ref "R66") (pin "2") (pinfunction "2_2") (pintype "passive"))
    )
    (net (code "107") (name "Net-(IC7-12VOUT)") (class "Default")
      (node (ref "C96") (pin "2") (pinfunction "2_2") (pintype "passive"))
      (node (ref "IC7") (pin "3") (pinfunction "12VOUT_3") (pintype "bidirectional"))
    )
    (net (code "108") (name "Net-(IC7-CPI)") (class "Default")
      (node (ref "C94") (pin "2") (pinfunction "2_2") (pintype "passive"))
      (node (ref "IC7") (pin "32") (pinfunction "CPI_32") (pintype "input"))
    )
    (net (code "109") (name "Net-(IC7-CPO)") (class "Default")
      (node (ref "C94") (pin "1") (pinfunction "1_1") (pintype "passive"))
      (node (ref "IC7") (pin "31") (pinfunction "CPO_31") (pintype "input"))
    )
    (net (code "110") (name "Net-(IC7-VCC)") (class "Default")
      (node (ref "C106") (pin "2") (pinfunction "2_2") (pintype "passive"))
      (node (ref "IC7") (pin "29") (pinfunction "VCC_29") (pintype "power_in"))
      (node (ref "R66") (pin "1") (pinfunction "1_1") (pintype "passive"))
    )
    (net (code "111") (name "Net-(IC7-VCP)") (class "Default")
      (node (ref "C97") (pin "1") (pinfunction "1_1") (pintype "passive"))
      (node (ref "IC7") (pin "34") (pinfunction "VCP_34") (pintype "input"))
    )
    (net (code "112") (name "Net-(Q5-D)") (class "Default")
      (node (ref "Q5") (pin "3") (pinfunction "D_3") (pintype "passive"))
      (node (ref "R12") (pin "2") (pinfunction "2_2") (pintype "passive"))
    )
    (net (code "113") (name "Net-(Q7-S1)") (class "Default")
      (node (ref "Q7") (pin "4") (pinfunction "S1_4") (pintype "passive"))
      (node (ref "Q7") (pin "5") (pinfunction "S2_5") (pintype "passive"))
      (node (ref "R40") (pin "2") (pinfunction "2_2") (pintype "passive"))
      (node (ref "R41") (pin "1") (pinfunction "1_1") (pintype "passive"))
    )
    (net (code "114") (name "Net-(Q9-S1)") (class "Default")
      (node (ref "Q9") (pin "4") (pinfunction "S1_4") (pintype "passive"))
      (node (ref "Q9") (pin "5") (pinfunction "S2_5") (pintype "passive"))
      (node (ref "R39") (pin "2") (pinfunction "2_2") (pintype "passive"))
      (node (ref "R44") (pin "1") (pinfunction "1_1") (pintype "passive"))
    )
    (net (code "115") (name "Net-(Q11-S1)") (class "Default")
      (node (ref "Q11") (pin "4") (pinfunction "S1_4") (pintype "passive"))
      (node (ref "Q11") (pin "5") (pinfunction "S2_5") (pintype "passive"))
      (node (ref "R48") (pin "2") (pinfunction "2_2") (pintype "passive"))
      (node (ref "R49") (pin "1") (pinfunction "1_1") (pintype "passive"))
    )
    (net (code "116") (name "Net-(Q13-S1)") (class "Default")
      (node (ref "Q13") (pin "4") (pinfunction "S1_4") (pintype "passive"))
      (node (ref "Q13") (pin "5") (pinfunction "S2_5") (pintype "passive"))
      (node (ref "R47") (pin "2") (pinfunction "2_2") (pintype "passive"))
      (node (ref "R52") (pin "1") (pinfunction "1_1") (pintype "passive"))
    )
    (net (code "117") (name "Net-(Q15-S1)") (class "Default")
      (node (ref "Q15") (pin "4") (pinfunction "S1_4") (pintype "passive"))
      (node (ref "Q15") (pin "5") (pinfunction "S2_5") (pintype "passive"))
      (node (ref "R56") (pin "2") (pinfunction "2_2") (pintype "passive"))
      (node (ref "R57") (pin "1") (pinfunction "1_1") (pintype "passive"))
    )
    (net (code "118") (name "Net-(Q17-S1)") (class "Default")
      (node (ref "Q17") (pin "4") (pinfunction "S1_4") (pintype "passive"))
      (node (ref "Q17") (pin "5") (pinfunction "S2_5") (pintype "passive"))
      (node (ref "R55") (pin "2") (pinfunction "2_2") (pintype "passive"))
      (node (ref "R60") (pin "1") (pinfunction "1_1") (pintype "passive"))
    )
    (net (code "119") (name "Net-(Q19-S1)") (class "Default")
      (node (ref "Q19") (pin "4") (pinfunction "S1_4") (pintype "passive"))
      (node (ref "Q19") (pin "5") (pinfunction "S2_5") (pintype "passive"))
      (node (ref "R64") (pin "2") (pinfunction "2_2") (pintype "passive"))
      (node (ref "R65") (pin "1") (pinfunction "1_1") (pintype "passive"))
    )
    (net (code "120") (name "Net-(Q21-S1)") (class "Default")
      (node (ref "Q21") (pin "4") (pinfunction "S1_4") (pintype "passive"))
      (node (ref "Q21") (pin "5") (pinfunction "S2_5") (pintype "passive"))
      (node (ref "R63") (pin "2") (pinfunction "2_2") (pintype "passive"))
      (node (ref "R68") (pin "1") (pinfunction "1_1") (pintype "passive"))
    )
    (net (code "121") (name "Net-(U1-P0[21]{slash}RI1{slash}RD1)") (class "Default")
      (node (ref "R2") (pin "2") (pinfunction "2_2") (pintype "passive"))
      (node (ref "U1") (pin "57") (pinfunction "P0[21]/RI1/RD1_57") (pintype "bidirectional"))
    )
    (net (code "122") (name "Net-(U1-P2[1]{slash}PWM1[2]{slash}RXD1)") (class "Default")
      (node (ref "R37") (pin "2") (pinfunction "2_2") (pintype "passive"))
      (node (ref "U1") (pin "74") (pinfunction "P2[1]/PWM1[2]/RXD1_74") (pintype "bidirectional"))
    )
    (net (code "123") (name "Net-(U1-P2[8]{slash}TD2{slash}TXD2)") (class "Default")
      (node (ref "R1") (pin "2") (pinfunction "2_2") (pintype "passive"))
      (node (ref "U1") (pin "65") (pinfunction "P2[8]/TD2/TXD2_65") (pintype "bidirectional"))
    )
    (net (code "124") (name "Net-(U1-P2[12]{slash}~{EINT2{slash}I2STX_WS})") (class "Default")
      (node (ref "R3") (pin "2") (pinfunction "2_2") (pintype "passive"))
      (node (ref "U1") (pin "51") (pinfunction "P2[12]/~{EINT2/I2STX_WS}_51") (pintype "bidirectional"))
    )
    (net (code "125") (name "Net-(U1-RTCX1)") (class "Default")
      (node (ref "R24") (pin "1") (pinfunction "1_1") (pintype "passive"))
      (node (ref "U1") (pin "16") (pinfunction "RTCX1_16") (pintype "input"))
    )
    (net (code "126") (name "Net-(U1-XTAL1)") (class "Default")
      (node (ref "C41") (pin "2") (pinfunction "2_2") (pintype "passive"))
      (node (ref "Q6") (pin "1") (pinfunction "1_1") (pintype "passive"))
      (node (ref "R25") (pin "2") (pinfunction "2_2") (pintype "passive"))
      (node (ref "U1") (pin "22") (pinfunction "XTAL1_22") (pintype "input"))
    )
    (net (code "127") (name "Net-(U1-XTAL2)") (class "Default")
      (node (ref "C42") (pin "2") (pinfunction "2_2") (pintype "passive"))
      (node (ref "Q6") (pin "2") (pinfunction "2_2") (pintype "passive"))
      (node (ref "R25") (pin "1") (pinfunction "1_1") (pintype "passive"))
      (node (ref "U1") (pin "23") (pinfunction "XTAL2_23") (pintype "output"))
    )
    (net (code "128") (name "Net-(U1-~{RSTOUT})") (class "Default")
      (node (ref "R19") (pin "1") (pinfunction "1_1") (pintype "passive"))
      (node (ref "U1") (pin "14") (pinfunction "~{RSTOUT}_14") (pintype "output"))
    )
    (net (code "129") (name "Net-(U2-VN)") (class "Default")
      (node (ref "C20") (pin "2") (pinfunction "2_2") (pintype "passive"))
      (node (ref "U2") (pin "2") (pinfunction "VN_2") (pintype "power_in"))
    )
    (net (code "130") (name "Net-(U6-D)") (class "Default")
      (node (ref "CONTROLLED-FANS") (pin "4") (pinfunction "4_4") (pintype "passive"))
      (node (ref "U6") (pin "3") (pinfunction "D_3") (pintype "passive"))
    )
    (net (code "131") (name "Net-(U7-D)") (class "Default")
      (node (ref "CONTROLLED-FANS") (pin "2") (pinfunction "2_2") (pintype "passive"))
      (node (ref "U7") (pin "3") (pinfunction "D_3") (pintype "passive"))
    )
    (net (code "132") (name "P0.26") (class "Default")
      (node (ref "EXPANSION3") (pin "7") (pinfunction "7_7") (pintype "passive"))
      (node (ref "U1") (pin "6") (pinfunction "P0[26]/AD0[3]/AOUT/RXD3_6") (pintype "bidirectional"))
    )
    (net (code "133") (name "P0.27") (class "Default")
      (node (ref "EXPANSION3") (pin "8") (pinfunction "8_8") (pintype "passive"))
      (node (ref "U1") (pin "25") (pinfunction "P0[27]/SDA0/USB_SDA_25") (pintype "bidirectional"))
    )
    (net (code "134") (name "P38") (class "Default")
      (node (ref "NEOPIXEL") (pin "1") (pinfunction "1_1") (pintype "passive"))
      (node (ref "U1") (pin "38") (pinfunction "P1[24]/MCI2/PWM1[5]/MOSI0_38") (pintype "bidirectional"))
    )
    (net (code "135") (name "POWERIN") (class "Default")
      (node (ref "F1") (pin "1A") (pinfunction "1A_1A") (pintype "passive"))
      (node (ref "F2") (pin "2A") (pinfunction "2A_2A") (pintype "passive"))
      (node (ref "POWER") (pin "1") (pinfunction "KL_1") (pintype "passive"))
    )
    (net (code "136") (name "PROBE") (class "Default")
      (node (ref "EXTRA3") (pin "1") (pinfunction "1_1") (pintype "passive"))
      (node (ref "U1") (pin "48") (pinfunction "P0[10]/TXD2/SDA2/MAT3[0]_48") (pintype "bidirectional"))
    )
    (net (code "137") (name "RESET") (class "Default")
      (node (ref "C21") (pin "1") (pinfunction "1_1") (pintype "passive"))
      (node (ref "EXP2") (pin "8") (pinfunction "KL_8") (pintype "passive"))
      (node (ref "R13") (pin "2") (pinfunction "2_2") (pintype "passive"))
      (node (ref "S1") (pin "1") (pinfunction "S_1") (pintype "passive"))
      (node (ref "SV1") (pin "1") (pinfunction "1_1") (pintype "passive"))
      (node (ref "U1") (pin "17") (pinfunction "~{RESET}_17") (pintype "input"))
    )
    (net (code "138") (name "RX") (class "Default")
      (node (ref "IC7") (pin "13") (pinfunction "CSN_CFG3_13") (pintype "input"))
      (node (ref "SV16") (pin "9") (pinfunction "9_9") (pintype "passive"))
    )
    (net (code "139") (name "RX0") (class "Default")
      (node (ref "SV1") (pin "2") (pinfunction "2_2") (pintype "passive"))
      (node (ref "U1") (pin "99") (pinfunction "P0[3]/RXD0/AD0[6]_99") (pintype "bidirectional"))
    )
    (net (code "140") (name "SCK") (class "Default")
      (node (ref "EXPANSION3") (pin "6") (pinfunction "6_6") (pintype "passive"))
      (node (ref "U1") (pin "78") (pinfunction "P0[7]/I2STX_CLK/SCK1/MAT2[1]_78") (pintype "bidirectional"))
    )
    (net (code "141") (name "SCL1") (class "Default")
      (node (ref "SV2") (pin "4") (pinfunction "4_4") (pintype "passive"))
      (node (ref "U1") (pin "47") (pinfunction "P0[1]/TD1/RXD3/SCL1_47") (pintype "bidirectional"))
    )
    (net (code "142") (name "SDA1") (class "Default")
      (node (ref "SV2") (pin "3") (pinfunction "3_3") (pintype "passive"))
      (node (ref "U1") (pin "46") (pinfunction "P0[0]/RD1/TXD3/SDA1_46") (pintype "bidirectional"))
    )
    (net (code "143") (name "SERVO") (class "Default")
      (node (ref "SERVO") (pin "1") (pinfunction "1_1") (pintype "passive"))
      (node (ref "U1") (pin "75") (pinfunction "P2[0]/PWM1[1]/TXD1_75") (pintype "bidirectional"))
    )
    (net (code "144") (name "SLP") (class "Default")
      (node (ref "IC7") (pin "12") (pinfunction "CLK_12") (pintype "input"))
      (node (ref "SV16") (pin "5") (pinfunction "5_5") (pintype "passive"))
    )
    (net (code "145") (name "SOFTCONNECT") (class "Default")
      (node (ref "Q5") (pin "1") (pinfunction "G_1") (pintype "passive"))
      (node (ref "R11") (pin "1") (pinfunction "1_1") (pintype "passive"))
      (node (ref "U1") (pin "64") (pinfunction "P2[9]/USB_CONNECT/RXD2_64") (pintype "bidirectional"))
    )
    (net (code "146") (name "SRAH") (class "Default")
      (node (ref "IC7") (pin "8") (pinfunction "SRAH_8") (pintype "input"))
      (node (ref "R63") (pin "1") (pinfunction "1_1") (pintype "passive"))
    )
    (net (code "147") (name "SRAL") (class "Default")
      (node (ref "IC7") (pin "7") (pinfunction "SRAL_7") (pintype "input"))
      (node (ref "R67") (pin "2") (pinfunction "2_2") (pintype "passive"))
    )
    (net (code "148") (name "SRBH") (class "Default")
      (node (ref "IC7") (pin "9") (pinfunction "SRBH_9") (pintype "input"))
      (node (ref "R64") (pin "1") (pinfunction "1_1") (pintype "passive"))
    )
    (net (code "149") (name "SRBL") (class "Default")
      (node (ref "IC7") (pin "10") (pinfunction "SRBL_10") (pintype "input"))
      (node (ref "R62") (pin "2") (pinfunction "2_2") (pintype "passive"))
    )
    (net (code "150") (name "SSEL") (class "Default")
      (node (ref "EXPANSION3") (pin "4") (pinfunction "4_4") (pintype "passive"))
      (node (ref "U1") (pin "79") (pinfunction "P0[6]/I2SRX_SDA/SSEL1/MAT2[0]_79") (pintype "bidirectional"))
    )
    (net (code "151") (name "STP") (class "Default")
      (node (ref "IC7") (pin "17") (pinfunction "REFL_STEP_17") (pintype "input"))
      (node (ref "SV16") (pin "3") (pinfunction "3_3") (pintype "passive"))
    )
    (net (code "152") (name "SWDCLK") (class "Default")
      (node (ref "JP2") (pin "4") (pinfunction "4_4") (pintype "passive"))
      (node (ref "U1") (pin "5") (pinfunction "TCK/SWDCLK_5") (pintype "input"))
    )
    (net (code "153") (name "SWDIO") (class "Default")
      (node (ref "JP2") (pin "2") (pinfunction "2_2") (pintype "passive"))
      (node (ref "U1") (pin "3") (pinfunction "TMS/SWDIO_3") (pintype "bidirectional"))
    )
    (net (code "154") (name "TH1") (class "Default")
      (node (ref "C22") (pin "2") (pinfunction "2_2") (pintype "passive"))
      (node (ref "R14") (pin "2") (pinfunction "2_2") (pintype "passive"))
      (node (ref "RV") (pin "2") (pinfunction "2_2") (pintype "passive"))
      (node (ref "THERMISTOR1") (pin "1") (pinfunction "S_1") (pintype "passive"))
      (node (ref "U1") (pin "9") (pinfunction "P0[23]/AD0[0]/I2SRX_CLK/CAP3[0]_9") (pintype "bidirectional"))
    )
    (net (code "155") (name "TH2") (class "Default")
      (node (ref "C23") (pin "2") (pinfunction "2_2") (pintype "passive"))
      (node (ref "R15") (pin "2") (pinfunction "2_2") (pintype "passive"))
      (node (ref "RV1") (pin "2") (pinfunction "2_2") (pintype "passive"))
      (node (ref "THERMISTOR2") (pin "1") (pinfunction "S_1") (pintype "passive"))
      (node (ref "U1") (pin "8") (pinfunction "P0[24]/AD0[1]/I2SRX_WS/CAP3[1]_8") (pintype "bidirectional"))
    )
    (net (code "156") (name "THB") (class "Default")
      (node (ref "C24") (pin "2") (pinfunction "2_2") (pintype "passive"))
      (node (ref "R16") (pin "2") (pinfunction "2_2") (pintype "passive"))
      (node (ref "RV2") (pin "2") (pinfunction "2_2") (pintype "passive"))
      (node (ref "THERMISTOR3") (pin "1") (pinfunction "S_1") (pintype "passive"))
      (node (ref "U1") (pin "7") (pinfunction "P0[25]/AD0[2]/I2SRX_SDA/TXD3_7") (pintype "bidirectional"))
    )
    (net (code "157") (name "TRST") (class "Default")
      (node (ref "JP2") (pin "5") (pinfunction "5_5") (pintype "passive"))
      (node (ref "U1") (pin "4") (pinfunction "~{TRST}_4") (pintype "input"))
    )
    (net (code "158") (name "TX0") (class "Default")
      (node (ref "SV1") (pin "3") (pinfunction "3_3") (pintype "passive"))
      (node (ref "U1") (pin "98") (pinfunction "P0[2]/TXD0/AD0[7]_98") (pintype "bidirectional"))
    )
    (net (code "159") (name "UC3.3V") (class "Default")
      (node (ref "C33") (pin "2") (pinfunction "2_2") (pintype "passive"))
      (node (ref "C34") (pin "2") (pinfunction "2_2") (pintype "passive"))
      (node (ref "C35") (pin "2") (pinfunction "2_2") (pintype "passive"))
      (node (ref "C36") (pin "2") (pinfunction "2_2") (pintype "passive"))
      (node (ref "C37") (pin "2") (pinfunction "2_2") (pintype "passive"))
      (node (ref "C38") (pin "2") (pinfunction "2_2") (pintype "passive"))
      (node (ref "C39") (pin "2") (pinfunction "2_2") (pintype "passive"))
      (node (ref "L2") (pin "2") (pinfunction "2_2") (pintype "passive"))
      (node (ref "R19") (pin "2") (pinfunction "2_2") (pintype "passive"))
      (node (ref "R24") (pin "2") (pinfunction "2_2") (pintype "passive"))
      (node (ref "U1") (pin "19") (pinfunction "VBAT_19") (pintype "input"))
      (node (ref "U1") (pin "28") (pinfunction "VDD(3V3)_2_28") (pintype "power_in"))
      (node (ref "U1") (pin "42") (pinfunction "VDD(REG)(3V3)_2_42") (pintype "power_in"))
      (node (ref "U1") (pin "54") (pinfunction "VDD(3V3)_3_54") (pintype "power_in"))
      (node (ref "U1") (pin "71") (pinfunction "VDD(3V3)_4_71") (pintype "power_in"))
      (node (ref "U1") (pin "84") (pinfunction "VDD(REG)(3V3)_84") (pintype "power_in"))
      (node (ref "U1") (pin "96") (pinfunction "VDD(3V3)_96") (pintype "power_in"))
    )
    (net (code "160") (name "USB5V") (class "Default")
      (node (ref "C19") (pin "2") (pinfunction "2_2") (pintype "passive"))
      (node (ref "R9") (pin "1") (pinfunction "1_1") (pintype "passive"))
      (node (ref "SW1") (pin "1") (pinfunction "1_1") (pintype "passive"))
      (node (ref "U2") (pin "5") (pinfunction "VP_5") (pintype "power_in"))
      (node (ref "X1") (pin "4") (pinfunction "4_4") (pintype "passive"))
    )
    (net (code "161") (name "VBB") (class "Default")
      (node (ref "CONTROLLED-FANS") (pin "1") (pinfunction "1_1") (pintype "passive"))
      (node (ref "CONTROLLED-FANS") (pin "3") (pinfunction "3_3") (pintype "passive"))
      (node (ref "D1") (pin "A") (pinfunction "A_A") (pintype "passive"))
      (node (ref "F2") (pin "1A") (pinfunction "1A_1A") (pintype "passive"))
      (node (ref "FANS") (pin "1") (pinfunction "1_1") (pintype "passive"))
      (node (ref "FANS") (pin "3") (pinfunction "3_3") (pintype "passive"))
      (node (ref "HOTEND") (pin "1") (pinfunction "KL_1") (pintype "passive"))
      (node (ref "HOTEND") (pin "3") (pinfunction "KL_3") (pintype "passive"))
      (node (ref "SV11") (pin "2") (pinfunction "2_2") (pintype "passive"))
      (node (ref "SV14") (pin "2") (pinfunction "2_2") (pintype "passive"))
      (node (ref "SV17") (pin "2") (pinfunction "2_2") (pintype "passive"))
      (node (ref "SV3") (pin "1") (pinfunction "1_1") (pintype "passive"))
      (node (ref "SV3") (pin "3") (pinfunction "3_3") (pintype "passive"))
      (node (ref "SV3") (pin "5") (pinfunction "5_5") (pintype "passive"))
      (node (ref "SV8") (pin "2") (pinfunction "2_2") (pintype "passive"))
    )
    (net (code "162") (name "VDDA") (class "Default")
      (node (ref "C40") (pin "1") (pinfunction "1_1") (pintype "passive"))
      (node (ref "L3") (pin "2") (pinfunction "2_2") (pintype "passive"))
      (node (ref "R14") (pin "1") (pinfunction "1_1") (pintype "passive"))
      (node (ref "R15") (pin "1") (pinfunction "1_1") (pintype "passive"))
      (node (ref "R16") (pin "1") (pinfunction "1_1") (pintype "passive"))
      (node (ref "U1") (pin "10") (pinfunction "VDDA_10") (pintype "power_in"))
      (node (ref "U1") (pin "12") (pinfunction "VREFP_12") (pintype "power_in"))
    )
    (net (code "163") (name "VHEAT") (class "Default")
      (node (ref "F1") (pin "2A") (pinfunction "2A_2A") (pintype "passive"))
      (node (ref "HEATBED") (pin "2") (pinfunction "KL_2") (pintype "passive"))
    )
    (net (code "164") (name "VOT") (class "Default")
      (node (ref "JP1") (pin "2") (pinfunction "2_2") (pintype "passive"))
      (node (ref "SW2") (pin "1") (pinfunction "1_1") (pintype "passive"))
    )
    (net (code "165") (name "X-DIR") (class "Default")
      (node (ref "SV7") (pin "2") (pinfunction "2_2") (pintype "passive"))
      (node (ref "U1") (pin "67") (pinfunction "P2[6]/PCAP1[0]/RI1/TRACECLK_67") (pintype "bidirectional"))
    )
    (net (code "166") (name "X-MOT-EN") (class "Default")
      (node (ref "R37") (pin "1") (pinfunction "1_1") (pintype "passive"))
      (node (ref "R45") (pin "2") (pinfunction "2_2") (pintype "passive"))
      (node (ref "SV7") (pin "16") (pinfunction "16_16") (pintype "passive"))
    )
    (net (code "167") (name "X-RX") (class "Default")
      (node (ref "SV7") (pin "10") (pinfunction "10_10") (pintype "passive"))
      (node (ref "U1") (pin "90") (pinfunction "P1[10]/ENET_RXD1_90") (pintype "bidirectional"))
    )
    (net (code "168") (name "X-SLP") (class "Default")
      (node (ref "SV7") (pin "6") (pinfunction "6_6") (pintype "passive"))
    )
    (net (code "169") (name "X-STP") (class "Default")
      (node (ref "SV7") (pin "4") (pinfunction "4_4") (pintype "passive"))
      (node (ref "U1") (pin "73") (pinfunction "P2[2]/PWM1[3]/CTS1/TRACEDATA[3]_73") (pintype "bidirectional"))
    )
    (net (code "170") (name "X1A") (class "Default")
      (node (ref "SV8") (pin "10") (pinfunction "10_10") (pintype "passive"))
      (node (ref "SV9") (pin "2") (pinfunction "2_2") (pintype "passive"))
    )
    (net (code "171") (name "X1B") (class "Default")
      (node (ref "SV8") (pin "12") (pinfunction "12_12") (pintype "passive"))
      (node (ref "SV9") (pin "1") (pinfunction "1_1") (pintype "passive"))
    )
    (net (code "172") (name "X2A") (class "Default")
      (node (ref "SV8") (pin "8") (pinfunction "8_8") (pintype "passive"))
      (node (ref "SV9") (pin "3") (pinfunction "3_3") (pintype "passive"))
    )
    (net (code "173") (name "X2B") (class "Default")
      (node (ref "SV8") (pin "6") (pinfunction "6_6") (pintype "passive"))
      (node (ref "SV9") (pin "4") (pinfunction "4_4") (pintype "passive"))
    )
    (net (code "174") (name "XBMA1") (class "Default")
      (node (ref "C57") (pin "2") (pinfunction "2_2") (pintype "passive"))
      (node (ref "IC4") (pin "40") (pinfunction "BMA1_40") (pintype "input"))
      (node (ref "Q10") (pin "4") (pinfunction "S1_4") (pintype "passive"))
      (node (ref "Q9") (pin "10") (pinfunction "D1_10") (pintype "passive"))
      (node (ref "SV8") (pin "9") (pinfunction "9_9") (pintype "passive"))
    )
    (net (code "175") (name "XBMA2") (class "Default")
      (node (ref "C56") (pin "1") (pinfunction "1_1") (pintype "passive"))
      (node (ref "IC4") (pin "37") (pinfunction "BMA2_37") (pintype "input"))
      (node (ref "Q10") (pin "5") (pinfunction "S2_5") (pintype "passive"))
      (node (ref "Q9") (pin "9") (pinfunction "D2_9") (pintype "passive"))
      (node (ref "SV8") (pin "7") (pinfunction "7_7") (pintype "passive"))
    )
    (net (code "176") (name "XBMB1") (class "Default")
      (node (ref "C53") (pin "2") (pinfunction "2_2") (pintype "passive"))
      (node (ref "IC4") (pin "48") (pinfunction "BMB1_48") (pintype "input"))
      (node (ref "Q7") (pin "10") (pinfunction "D1_10") (pintype "passive"))
      (node (ref "Q8") (pin "4") (pinfunction "S1_4") (pintype "passive"))
      (node (ref "SV8") (pin "11") (pinfunction "11_11") (pintype "passive"))
    )
    (net (code "177") (name "XBMB2") (class "Default")
      (node (ref "C52") (pin "1") (pinfunction "1_1") (pintype "passive"))
      (node (ref "IC4") (pin "45") (pinfunction "BMB2_45") (pintype "input"))
      (node (ref "Q7") (pin "9") (pinfunction "D2_9") (pintype "passive"))
      (node (ref "Q8") (pin "5") (pinfunction "S2_5") (pintype "passive"))
      (node (ref "SV8") (pin "5") (pinfunction "5_5") (pintype "passive"))
    )
    (net (code "178") (name "XCA1") (class "Default")
      (node (ref "C57") (pin "1") (pinfunction "1_1") (pintype "passive"))
      (node (ref "IC4") (pin "42") (pinfunction "CA1_42") (pintype "input"))
    )
    (net (code "179") (name "XCA2") (class "Default")
      (node (ref "C56") (pin "2") (pinfunction "2_2") (pintype "passive"))
      (node (ref "IC4") (pin "35") (pinfunction "CA2_35") (pintype "input"))
    )
    (net (code "180") (name "XCB1") (class "Default")
      (node (ref "C53") (pin "1") (pinfunction "1_1") (pintype "passive"))
      (node (ref "IC4") (pin "2") (pinfunction "CB1_2") (pintype "input"))
    )
    (net (code "181") (name "XCB2") (class "Default")
      (node (ref "C52") (pin "2") (pinfunction "2_2") (pintype "passive"))
      (node (ref "IC4") (pin "43") (pinfunction "CB2_43") (pintype "input"))
    )
    (net (code "182") (name "XDIR") (class "Default")
      (node (ref "IC4") (pin "18") (pinfunction "REFR_DIR_18") (pintype "input"))
      (node (ref "SV7") (pin "1") (pinfunction "1_1") (pintype "passive"))
    )
    (net (code "183") (name "XDRIVERGND") (class "Default")
      (node (ref "C44") (pin "2") (pinfunction "2_2") (pintype "passive"))
      (node (ref "C45") (pin "2") (pinfunction "2_2") (pintype "passive"))
      (node (ref "C47") (pin "2") (pinfunction "2_2") (pintype "passive"))
      (node (ref "C48") (pin "1") (pinfunction "1_1") (pintype "passive"))
      (node (ref "C50") (pin "2") (pinfunction "2_2") (pintype "passive"))
      (node (ref "C51") (pin "2") (pinfunction "2_2") (pintype "passive"))
      (node (ref "C54") (pin "1") (pinfunction "1_1") (pintype "passive"))
      (node (ref "C55") (pin "2") (pinfunction "2_2") (pintype "passive"))
      (node (ref "C58") (pin "1") (pinfunction "1_1") (pintype "passive"))
      (node (ref "C59") (pin "2") (pinfunction "2_2") (pintype "passive"))
      (node (ref "IC4") (pin "11") (pinfunction "TST_MODE_11") (pintype "input"))
      (node (ref "IC4") (pin "19") (pinfunction "GNDD_19") (pintype "power_in"))
      (node (ref "IC4") (pin "30") (pinfunction "GNDD_2_30") (pintype "power_in"))
      (node (ref "IC4") (pin "49") (pinfunction "GNDP_49") (pintype "power_in"))
      (node (ref "IC4") (pin "6") (pinfunction "GNDA_6") (pintype "power_in"))
      (node (ref "R38") (pin "1") (pinfunction "1_1") (pintype "passive"))
      (node (ref "R41") (pin "2") (pinfunction "2_2") (pintype "passive"))
      (node (ref "R43") (pin "1") (pinfunction "1_1") (pintype "passive"))
      (node (ref "R44") (pin "2") (pinfunction "2_2") (pintype "passive"))
      (node (ref "SV8") (pin "15") (pinfunction "15_15") (pintype "passive"))
      (node (ref "SV8") (pin "3") (pinfunction "3_3") (pintype "passive"))
    )
    (net (code "184") (name "XDRIVERVBB") (class "Default")
      (node (ref "C44") (pin "1") (pinfunction "1_1") (pintype "passive"))
      (node (ref "C45") (pin "1") (pinfunction "1_1") (pintype "passive"))
      (node (ref "C47") (pin "1") (pinfunction "1_1") (pintype "passive"))
      (node (ref "C49") (pin "2") (pinfunction "2_2") (pintype "passive"))
      (node (ref "C51") (pin "1") (pinfunction "1_1") (pintype "passive"))
      (node (ref "C55") (pin "1") (pinfunction "1_1") (pintype "passive"))
      (node (ref "C59") (pin "1") (pinfunction "1_1") (pintype "passive"))
      (node (ref "IC4") (pin "33") (pinfunction "VS_33") (pintype "power_in"))
      (node (ref "IC4") (pin "4") (pinfunction "VSA_4") (pintype "power_in"))
      (node (ref "Q10") (pin "10") (pinfunction "D1_10") (pintype "passive"))
      (node (ref "Q10") (pin "9") (pinfunction "D2_9") (pintype "passive"))
      (node (ref "Q8") (pin "10") (pinfunction "D1_10") (pintype "passive"))
      (node (ref "Q8") (pin "9") (pinfunction "D2_9") (pintype "passive"))
      (node (ref "SV8") (pin "1") (pinfunction "1_1") (pintype "passive"))
    )
    (net (code "185") (name "XDRIVERVSS") (class "Default")
      (node (ref "C50") (pin "1") (pinfunction "1_1") (pintype "passive"))
      (node (ref "IC4") (pin "20") (pinfunction "VCC_IO_20") (pintype "power_in"))
      (node (ref "IC4") (pin "21") (pinfunction "SD_MODE_21") (pintype "input"))
      (node (ref "IC4") (pin "22") (pinfunction "SPI_MODE_22") (pintype "input"))
      (node (ref "SV8") (pin "13") (pinfunction "13_13") (pintype "passive"))
    )
    (net (code "186") (name "XENABLE") (class "Default")
      (node (ref "IC4") (pin "28") (pinfunction "DRV_ENN_28") (pintype "input"))
      (node (ref "SV7") (pin "15") (pinfunction "15_15") (pintype "passive"))
    )
    (net (code "187") (name "XHA1") (class "Default")
      (node (ref "IC4") (pin "41") (pinfunction "HA1_41") (pintype "output"))
      (node (ref "Q10") (pin "1") (pinfunction "G1_1") (pintype "passive"))
    )
    (net (code "188") (name "XHA2") (class "Default")
      (node (ref "IC4") (pin "36") (pinfunction "HA2_36") (pintype "output"))
      (node (ref "Q10") (pin "8") (pinfunction "G2_8") (pintype "passive"))
    )
    (net (code "189") (name "XHB1") (class "Default")
      (node (ref "IC4") (pin "1") (pinfunction "HB1_1") (pintype "output"))
      (node (ref "Q8") (pin "1") (pinfunction "G1_1") (pintype "passive"))
    )
    (net (code "190") (name "XHB2") (class "Default")
      (node (ref "IC4") (pin "44") (pinfunction "HB2_44") (pintype "output"))
      (node (ref "Q8") (pin "8") (pinfunction "G2_8") (pintype "passive"))
    )
    (net (code "191") (name "XLA1") (class "Default")
      (node (ref "IC4") (pin "39") (pinfunction "LA1_39") (pintype "output"))
      (node (ref "Q9") (pin "1") (pinfunction "G1_1") (pintype "passive"))
    )
    (net (code "192") (name "XLA2") (class "Default")
      (node (ref "IC4") (pin "38") (pinfunction "LA2_38") (pintype "output"))
      (node (ref "Q9") (pin "8") (pinfunction "G2_8") (pintype "passive"))
    )
    (net (code "193") (name "XLB1") (class "Default")
      (node (ref "IC4") (pin "47") (pinfunction "LB1_47") (pintype "output"))
      (node (ref "Q7") (pin "1") (pinfunction "G1_1") (pintype "passive"))
    )
    (net (code "194") (name "XLB2") (class "Default")
      (node (ref "IC4") (pin "46") (pinfunction "LB2_46") (pintype "output"))
      (node (ref "Q7") (pin "8") (pinfunction "G2_8") (pintype "passive"))
    )
    (net (code "195") (name "XMIN") (class "Default")
      (node (ref "R26") (pin "2") (pinfunction "2_2") (pintype "passive"))
      (node (ref "U1") (pin "45") (pinfunction "P1[29]/MCOB2/PCAP1[1]/MAT0[1]_45") (pintype "bidirectional"))
    )
    (net (code "196") (name "XMOTORMISO") (class "Default")
      (node (ref "IC4") (pin "16") (pinfunction "SDO_CFG0_16") (pintype "output"))
      (node (ref "SV7") (pin "7") (pinfunction "7_7") (pintype "passive"))
    )
    (net (code "197") (name "XMOTORMOSI") (class "Default")
      (node (ref "IC4") (pin "15") (pinfunction "SDI_CFG1_15") (pintype "input"))
      (node (ref "SV7") (pin "13") (pinfunction "13_13") (pintype "passive"))
    )
    (net (code "198") (name "XMOTORSCK") (class "Default")
      (node (ref "IC4") (pin "14") (pinfunction "SCK_CFG2_14") (pintype "input"))
      (node (ref "SV7") (pin "11") (pinfunction "11_11") (pintype "passive"))
    )
    (net (code "199") (name "XRX") (class "Default")
      (node (ref "IC4") (pin "13") (pinfunction "CSN_CFG3_13") (pintype "input"))
      (node (ref "SV7") (pin "9") (pinfunction "9_9") (pintype "passive"))
    )
    (net (code "200") (name "XSLP") (class "Default")
      (node (ref "IC4") (pin "12") (pinfunction "CLK_12") (pintype "input"))
      (node (ref "SV7") (pin "5") (pinfunction "5_5") (pintype "passive"))
    )
    (net (code "201") (name "XSRAH") (class "Default")
      (node (ref "IC4") (pin "8") (pinfunction "SRAH_8") (pintype "input"))
      (node (ref "R39") (pin "1") (pinfunction "1_1") (pintype "passive"))
    )
    (net (code "202") (name "XSRAL") (class "Default")
      (node (ref "IC4") (pin "7") (pinfunction "SRAL_7") (pintype "input"))
      (node (ref "R43") (pin "2") (pinfunction "2_2") (pintype "passive"))
    )
    (net (code "203") (name "XSRBH") (class "Default")
      (node (ref "IC4") (pin "9") (pinfunction "SRBH_9") (pintype "input"))
      (node (ref "R40") (pin "1") (pinfunction "1_1") (pintype "passive"))
    )
    (net (code "204") (name "XSRBL") (class "Default")
      (node (ref "IC4") (pin "10") (pinfunction "SRBL_10") (pintype "input"))
      (node (ref "R38") (pin "2") (pinfunction "2_2") (pintype "passive"))
    )
    (net (code "205") (name "XSTP") (class "Default")
      (node (ref "IC4") (pin "17") (pinfunction "REFL_STEP_17") (pintype "input"))
      (node (ref "SV7") (pin "3") (pinfunction "3_3") (pintype "passive"))
    )
    (net (code "206") (name "Y-DIR") (class "Default")
      (node (ref "SV10") (pin "2") (pinfunction "2_2") (pintype "passive"))
      (node (ref "U1") (pin "58") (pinfunction "P0[20]/DTR1/SCL1_58") (pintype "bidirectional"))
    )
    (net (code "207") (name "Y-MOT-EN") (class "Default")
      (node (ref "R1") (pin "1") (pinfunction "1_1") (pintype "passive"))
      (node (ref "R53") (pin "2") (pinfunction "2_2") (pintype "passive"))
      (node (ref "SV10") (pin "16") (pinfunction "16_16") (pintype "passive"))
    )
    (net (code "208") (name "Y-RX") (class "Default")
      (node (ref "SV10") (pin "10") (pinfunction "10_10") (pintype "passive"))
      (node (ref "U1") (pin "91") (pinfunction "P1[9]/ENET_RXD0_91") (pintype "bidirectional"))
    )
    (net (code "209") (name "Y-SLP") (class "Default")
      (node (ref "SV10") (pin "6") (pinfunction "6_6") (pintype "passive"))
    )
    (net (code "210") (name "Y-STP") (class "Default")
      (node (ref "SV10") (pin "4") (pinfunction "4_4") (pintype "passive"))
      (node (ref "U1") (pin "59") (pinfunction "P0[19]/DSR1/SDA1_59") (pintype "bidirectional"))
    )
    (net (code "211") (name "Y1A") (class "Default")
      (node (ref "SV11") (pin "10") (pinfunction "10_10") (pintype "passive"))
      (node (ref "SV12") (pin "2") (pinfunction "2_2") (pintype "passive"))
    )
    (net (code "212") (name "Y1B") (class "Default")
      (node (ref "SV11") (pin "12") (pinfunction "12_12") (pintype "passive"))
      (node (ref "SV12") (pin "1") (pinfunction "1_1") (pintype "passive"))
    )
    (net (code "213") (name "Y2A") (class "Default")
      (node (ref "SV11") (pin "8") (pinfunction "8_8") (pintype "passive"))
      (node (ref "SV12") (pin "3") (pinfunction "3_3") (pintype "passive"))
    )
    (net (code "214") (name "Y2B") (class "Default")
      (node (ref "SV11") (pin "6") (pinfunction "6_6") (pintype "passive"))
      (node (ref "SV12") (pin "4") (pinfunction "4_4") (pintype "passive"))
    )
    (net (code "215") (name "YBMA1") (class "Default")
      (node (ref "C73") (pin "2") (pinfunction "2_2") (pintype "passive"))
      (node (ref "IC5") (pin "40") (pinfunction "BMA1_40") (pintype "input"))
      (node (ref "Q13") (pin "10") (pinfunction "D1_10") (pintype "passive"))
      (node (ref "Q14") (pin "4") (pinfunction "S1_4") (pintype "passive"))
      (node (ref "SV11") (pin "9") (pinfunction "9_9") (pintype "passive"))
    )
    (net (code "216") (name "YBMA2") (class "Default")
      (node (ref "C72") (pin "1") (pinfunction "1_1") (pintype "passive"))
      (node (ref "IC5") (pin "37") (pinfunction "BMA2_37") (pintype "input"))
      (node (ref "Q13") (pin "9") (pinfunction "D2_9") (pintype "passive"))
      (node (ref "Q14") (pin "5") (pinfunction "S2_5") (pintype "passive"))
      (node (ref "SV11") (pin "7") (pinfunction "7_7") (pintype "passive"))
    )
    (net (code "217") (name "YBMB1") (class "Default")
      (node (ref "C69") (pin "2") (pinfunction "2_2") (pintype "passive"))
      (node (ref "IC5") (pin "48") (pinfunction "BMB1_48") (pintype "input"))
      (node (ref "Q11") (pin "10") (pinfunction "D1_10") (pintype "passive"))
      (node (ref "Q12") (pin "4") (pinfunction "S1_4") (pintype "passive"))
      (node (ref "SV11") (pin "11") (pinfunction "11_11") (pintype "passive"))
    )
    (net (code "218") (name "YBMB2") (class "Default")
      (node (ref "C68") (pin "1") (pinfunction "1_1") (pintype "passive"))
      (node (ref "IC5") (pin "45") (pinfunction "BMB2_45") (pintype "input"))
      (node (ref "Q11") (pin "9") (pinfunction "D2_9") (pintype "passive"))
      (node (ref "Q12") (pin "5") (pinfunction "S2_5") (pintype "passive"))
      (node (ref "SV11") (pin "5") (pinfunction "5_5") (pintype "passive"))
    )
    (net (code "219") (name "YCA1") (class "Default")
      (node (ref "C73") (pin "1") (pinfunction "1_1") (pintype "passive"))
      (node (ref "IC5") (pin "42") (pinfunction "CA1_42") (pintype "input"))
    )
    (net (code "220") (name "YCA2") (class "Default")
      (node (ref "C72") (pin "2") (pinfunction "2_2") (pintype "passive"))
      (node (ref "IC5") (pin "35") (pinfunction "CA2_35") (pintype "input"))
    )
    (net (code "221") (name "YCB1") (class "Default")
      (node (ref "C69") (pin "1") (pinfunction "1_1") (pintype "passive"))
      (node (ref "IC5") (pin "2") (pinfunction "CB1_2") (pintype "input"))
    )
    (net (code "222") (name "YCB2") (class "Default")
      (node (ref "C68") (pin "2") (pinfunction "2_2") (pintype "passive"))
      (node (ref "IC5") (pin "43") (pinfunction "CB2_43") (pintype "input"))
    )
    (net (code "223") (name "YDIR") (class "Default")
      (node (ref "IC5") (pin "18") (pinfunction "REFR_DIR_18") (pintype "input"))
      (node (ref "SV10") (pin "1") (pinfunction "1_1") (pintype "passive"))
    )
    (net (code "224") (name "YDRIVERGND") (class "Default")
      (node (ref "C60") (pin "2") (pinfunction "2_2") (pintype "passive"))
      (node (ref "C61") (pin "2") (pinfunction "2_2") (pintype "passive"))
      (node (ref "C63") (pin "2") (pinfunction "2_2") (pintype "passive"))
      (node (ref "C64") (pin "1") (pinfunction "1_1") (pintype "passive"))
      (node (ref "C66") (pin "2") (pinfunction "2_2") (pintype "passive"))
      (node (ref "C67") (pin "2") (pinfunction "2_2") (pintype "passive"))
      (node (ref "C70") (pin "1") (pinfunction "1_1") (pintype "passive"))
      (node (ref "C71") (pin "2") (pinfunction "2_2") (pintype "passive"))
      (node (ref "C74") (pin "1") (pinfunction "1_1") (pintype "passive"))
      (node (ref "C75") (pin "2") (pinfunction "2_2") (pintype "passive"))
      (node (ref "IC5") (pin "11") (pinfunction "TST_MODE_11") (pintype "input"))
      (node (ref "IC5") (pin "19") (pinfunction "GNDD_19") (pintype "power_in"))
      (node (ref "IC5") (pin "30") (pinfunction "GNDD_2_30") (pintype "power_in"))
      (node (ref "IC5") (pin "49") (pinfunction "GNDP_49") (pintype "power_in"))
      (node (ref "IC5") (pin "6") (pinfunction "GNDA_6") (pintype "power_in"))
      (node (ref "R46") (pin "1") (pinfunction "1_1") (pintype "passive"))
      (node (ref "R49") (pin "2") (pinfunction "2_2") (pintype "passive"))
      (node (ref "R51") (pin "1") (pinfunction "1_1") (pintype "passive"))
      (node (ref "R52") (pin "2") (pinfunction "2_2") (pintype "passive"))
      (node (ref "SV11") (pin "15") (pinfunction "15_15") (pintype "passive"))
      (node (ref "SV11") (pin "3") (pinfunction "3_3") (pintype "passive"))
    )
    (net (code "225") (name "YDRIVERVBB") (class "Default")
      (node (ref "C60") (pin "1") (pinfunction "1_1") (pintype "passive"))
      (node (ref "C61") (pin "1") (pinfunction "1_1") (pintype "passive"))
      (node (ref "C63") (pin "1") (pinfunction "1_1") (pintype "passive"))
      (node (ref "C65") (pin "2") (pinfunction "2_2") (pintype "passive"))
      (node (ref "C67") (pin "1") (pinfunction "1_1") (pintype "passive"))
      (node (ref "C71") (pin "1") (pinfunction "1_1") (pintype "passive"))
      (node (ref "C75") (pin "1") (pinfunction "1_1") (pintype "passive"))
      (node (ref "IC5") (pin "33") (pinfunction "VS_33") (pintype "power_in"))
      (node (ref "IC5") (pin "4") (pinfunction "VSA_4") (pintype "power_in"))
      (node (ref "Q12") (pin "10") (pinfunction "D1_10") (pintype "passive"))
      (node (ref "Q12") (pin "9") (pinfunction "D2_9") (pintype "passive"))
      (node (ref "Q14") (pin "10") (pinfunction "D1_10") (pintype "passive"))
      (node (ref "Q14") (pin "9") (pinfunction "D2_9") (pintype "passive"))
      (node (ref "SV11") (pin "1") (pinfunction "1_1") (pintype "passive"))
    )
    (net (code "226") (name "YDRIVERVSS") (class "Default")
      (node (ref "C66") (pin "1") (pinfunction "1_1") (pintype "passive"))
      (node (ref "IC5") (pin "20") (pinfunction "VCC_IO_20") (pintype "power_in"))
      (node (ref "IC5") (pin "21") (pinfunction "SD_MODE_21") (pintype "input"))
      (node (ref "IC5") (pin "22") (pinfunction "SPI_MODE_22") (pintype "input"))
      (node (ref "SV11") (pin "13") (pinfunction "13_13") (pintype "passive"))
    )
    (net (code "227") (name "YENABLE") (class "Default")
      (node (ref "IC5") (pin "28") (pinfunction "DRV_ENN_28") (pintype "input"))
      (node (ref "SV10") (pin "15") (pinfunction "15_15") (pintype "passive"))
    )
    (net (code "228") (name "YHA1") (class "Default")
      (node (ref "IC5") (pin "41") (pinfunction "HA1_41") (pintype "output"))
      (node (ref "Q14") (pin "1") (pinfunction "G1_1") (pintype "passive"))
    )
    (net (code "229") (name "YHA2") (class "Default")
      (node (ref "IC5") (pin "36") (pinfunction "HA2_36") (pintype "output"))
      (node (ref "Q14") (pin "8") (pinfunction "G2_8") (pintype "passive"))
    )
    (net (code "230") (name "YHB1") (class "Default")
      (node (ref "IC5") (pin "1") (pinfunction "HB1_1") (pintype "output"))
      (node (ref "Q12") (pin "1") (pinfunction "G1_1") (pintype "passive"))
    )
    (net (code "231") (name "YHB2") (class "Default")
      (node (ref "IC5") (pin "44") (pinfunction "HB2_44") (pintype "output"))
      (node (ref "Q12") (pin "8") (pinfunction "G2_8") (pintype "passive"))
    )
    (net (code "232") (name "YLA1") (class "Default")
      (node (ref "IC5") (pin "39") (pinfunction "LA1_39") (pintype "output"))
      (node (ref "Q13") (pin "1") (pinfunction "G1_1") (pintype "passive"))
    )
    (net (code "233") (name "YLA2") (class "Default")
      (node (ref "IC5") (pin "38") (pinfunction "LA2_38") (pintype "output"))
      (node (ref "Q13") (pin "8") (pinfunction "G2_8") (pintype "passive"))
    )
    (net (code "234") (name "YLB1") (class "Default")
      (node (ref "IC5") (pin "47") (pinfunction "LB1_47") (pintype "output"))
      (node (ref "Q11") (pin "1") (pinfunction "G1_1") (pintype "passive"))
    )
    (net (code "235") (name "YLB2") (class "Default")
      (node (ref "IC5") (pin "46") (pinfunction "LB2_46") (pintype "output"))
      (node (ref "Q11") (pin "8") (pinfunction "G2_8") (pintype "passive"))
    )
    (net (code "236") (name "YMIN") (class "Default")
      (node (ref "R28") (pin "2") (pinfunction "2_2") (pintype "passive"))
      (node (ref "U1") (pin "44") (pinfunction "P1[28]/MCOA2/PCAP1[0]/MAT0[0]_44") (pintype "bidirectional"))
    )
    (net (code "237") (name "YMOTORMISO") (class "Default")
      (node (ref "IC5") (pin "16") (pinfunction "SDO_CFG0_16") (pintype "output"))
      (node (ref "SV10") (pin "7") (pinfunction "7_7") (pintype "passive"))
    )
    (net (code "238") (name "YMOTORMOSI") (class "Default")
      (node (ref "IC5") (pin "15") (pinfunction "SDI_CFG1_15") (pintype "input"))
      (node (ref "SV10") (pin "13") (pinfunction "13_13") (pintype "passive"))
    )
    (net (code "239") (name "YMOTORSCK") (class "Default")
      (node (ref "IC5") (pin "14") (pinfunction "SCK_CFG2_14") (pintype "input"))
      (node (ref "SV10") (pin "11") (pinfunction "11_11") (pintype "passive"))
    )
    (net (code "240") (name "YRX") (class "Default")
      (node (ref "IC5") (pin "13") (pinfunction "CSN_CFG3_13") (pintype "input"))
      (node (ref "SV10") (pin "9") (pinfunction "9_9") (pintype "passive"))
    )
    (net (code "241") (name "YSLP") (class "Default")
      (node (ref "IC5") (pin "12") (pinfunction "CLK_12") (pintype "input"))
      (node (ref "SV10") (pin "5") (pinfunction "5_5") (pintype "passive"))
    )
    (net (code "242") (name "YSRAH") (class "Default")
      (node (ref "IC5") (pin "8") (pinfunction "SRAH_8") (pintype "input"))
      (node (ref "R47") (pin "1") (pinfunction "1_1") (pintype "passive"))
    )
    (net (code "243") (name "YSRAL") (class "Default")
      (node (ref "IC5") (pin "7") (pinfunction "SRAL_7") (pintype "input"))
      (node (ref "R51") (pin "2") (pinfunction "2_2") (pintype "passive"))
    )
    (net (code "244") (name "YSRBH") (class "Default")
      (node (ref "IC5") (pin "9") (pinfunction "SRBH_9") (pintype "input"))
      (node (ref "R48") (pin "1") (pinfunction "1_1") (pintype "passive"))
    )
    (net (code "245") (name "YSRBL") (class "Default")
      (node (ref "IC5") (pin "10") (pinfunction "SRBL_10") (pintype "input"))
      (node (ref "R46") (pin "2") (pinfunction "2_2") (pintype "passive"))
    )
    (net (code "246") (name "YSTP") (class "Default")
      (node (ref "IC5") (pin "17") (pinfunction "REFL_STEP_17") (pintype "input"))
      (node (ref "SV10") (pin "3") (pinfunction "3_3") (pintype "passive"))
    )
    (net (code "247") (name "Z-DIR") (class "Default")
      (node (ref "SV13") (pin "2") (pinfunction "2_2") (pintype "passive"))
      (node (ref "U1") (pin "52") (pinfunction "P2[11]/~{EINT1/I2STX_CLK}_52") (pintype "bidirectional"))
    )
    (net (code "248") (name "Z-MOT-EN") (class "Default")
      (node (ref "R2") (pin "1") (pinfunction "1_1") (pintype "passive"))
      (node (ref "R61") (pin "2") (pinfunction "2_2") (pintype "passive"))
      (node (ref "SV13") (pin "16") (pinfunction "16_16") (pintype "passive"))
    )
    (net (code "249") (name "Z-RX") (class "Default")
      (node (ref "SV13") (pin "10") (pinfunction "10_10") (pintype "passive"))
      (node (ref "U1") (pin "92") (pinfunction "P1[8]/ENET_CRS_92") (pintype "bidirectional"))
    )
    (net (code "250") (name "Z-SLP") (class "Default")
      (node (ref "SV13") (pin "6") (pinfunction "6_6") (pintype "passive"))
    )
    (net (code "251") (name "Z-STP") (class "Default")
      (node (ref "SV13") (pin "4") (pinfunction "4_4") (pintype "passive"))
      (node (ref "U1") (pin "56") (pinfunction "P0[22]/RTS1/TD1_56") (pintype "bidirectional"))
    )
    (net (code "252") (name "Z1A") (class "Default")
      (node (ref "SV14") (pin "10") (pinfunction "10_10") (pintype "passive"))
      (node (ref "SV15") (pin "2") (pinfunction "2_2") (pintype "passive"))
    )
    (net (code "253") (name "Z1B") (class "Default")
      (node (ref "SV14") (pin "12") (pinfunction "12_12") (pintype "passive"))
      (node (ref "SV15") (pin "1") (pinfunction "1_1") (pintype "passive"))
    )
    (net (code "254") (name "Z2A") (class "Default")
      (node (ref "SV14") (pin "8") (pinfunction "8_8") (pintype "passive"))
      (node (ref "SV15") (pin "3") (pinfunction "3_3") (pintype "passive"))
    )
    (net (code "255") (name "Z2B") (class "Default")
      (node (ref "SV14") (pin "6") (pinfunction "6_6") (pintype "passive"))
      (node (ref "SV15") (pin "4") (pinfunction "4_4") (pintype "passive"))
    )
    (net (code "256") (name "ZBMA1") (class "Default")
      (node (ref "C89") (pin "2") (pinfunction "2_2") (pintype "passive"))
      (node (ref "IC6") (pin "40") (pinfunction "BMA1_40") (pintype "input"))
      (node (ref "Q17") (pin "10") (pinfunction "D1_10") (pintype "passive"))
      (node (ref "Q18") (pin "4") (pinfunction "S1_4") (pintype "passive"))
      (node (ref "SV14") (pin "9") (pinfunction "9_9") (pintype "passive"))
    )
    (net (code "257") (name "ZBMA2") (class "Default")
      (node (ref "C88") (pin "1") (pinfunction "1_1") (pintype "passive"))
      (node (ref "IC6") (pin "37") (pinfunction "BMA2_37") (pintype "input"))
      (node (ref "Q17") (pin "9") (pinfunction "D2_9") (pintype "passive"))
      (node (ref "Q18") (pin "5") (pinfunction "S2_5") (pintype "passive"))
      (node (ref "SV14") (pin "7") (pinfunction "7_7") (pintype "passive"))
    )
    (net (code "258") (name "ZBMB1") (class "Default")
      (node (ref "C85") (pin "2") (pinfunction "2_2") (pintype "passive"))
      (node (ref "IC6") (pin "48") (pinfunction "BMB1_48") (pintype "input"))
      (node (ref "Q15") (pin "10") (pinfunction "D1_10") (pintype "passive"))
      (node (ref "Q16") (pin "4") (pinfunction "S1_4") (pintype "passive"))
      (node (ref "SV14") (pin "11") (pinfunction "11_11") (pintype "passive"))
    )
    (net (code "259") (name "ZBMB2") (class "Default")
      (node (ref "C84") (pin "1") (pinfunction "1_1") (pintype "passive"))
      (node (ref "IC6") (pin "45") (pinfunction "BMB2_45") (pintype "input"))
      (node (ref "Q15") (pin "9") (pinfunction "D2_9") (pintype "passive"))
      (node (ref "Q16") (pin "5") (pinfunction "S2_5") (pintype "passive"))
      (node (ref "SV14") (pin "5") (pinfunction "5_5") (pintype "passive"))
    )
    (net (code "260") (name "ZCA1") (class "Default")
      (node (ref "C89") (pin "1") (pinfunction "1_1") (pintype "passive"))
      (node (ref "IC6") (pin "42") (pinfunction "CA1_42") (pintype "input"))
    )
    (net (code "261") (name "ZCA2") (class "Default")
      (node (ref "C88") (pin "2") (pinfunction "2_2") (pintype "passive"))
      (node (ref "IC6") (pin "35") (pinfunction "CA2_35") (pintype "input"))
    )
    (net (code "262") (name "ZCB1") (class "Default")
      (node (ref "C85") (pin "1") (pinfunction "1_1") (pintype "passive"))
      (node (ref "IC6") (pin "2") (pinfunction "CB1_2") (pintype "input"))
    )
    (net (code "263") (name "ZCB2") (class "Default")
      (node (ref "C84") (pin "2") (pinfunction "2_2") (pintype "passive"))
      (node (ref "IC6") (pin "43") (pinfunction "CB2_43") (pintype "input"))
    )
    (net (code "264") (name "ZDIR") (class "Default")
      (node (ref "IC6") (pin "18") (pinfunction "REFR_DIR_18") (pintype "input"))
      (node (ref "SV13") (pin "1") (pinfunction "1_1") (pintype "passive"))
    )
    (net (code "265") (name "ZDRIVERGND") (class "Default")
      (node (ref "C76") (pin "2") (pinfunction "2_2") (pintype "passive"))
      (node (ref "C77") (pin "2") (pinfunction "2_2") (pintype "passive"))
      (node (ref "C79") (pin "2") (pinfunction "2_2") (pintype "passive"))
      (node (ref "C80") (pin "1") (pinfunction "1_1") (pintype "passive"))
      (node (ref "C82") (pin "2") (pinfunction "2_2") (pintype "passive"))
      (node (ref "C83") (pin "2") (pinfunction "2_2") (pintype "passive"))
      (node (ref "C86") (pin "1") (pinfunction "1_1") (pintype "passive"))
      (node (ref "C87") (pin "2") (pinfunction "2_2") (pintype "passive"))
      (node (ref "C90") (pin "1") (pinfunction "1_1") (pintype "passive"))
      (node (ref "C91") (pin "2") (pinfunction "2_2") (pintype "passive"))
      (node (ref "IC6") (pin "11") (pinfunction "TST_MODE_11") (pintype "input"))
      (node (ref "IC6") (pin "19") (pinfunction "GNDD_19") (pintype "power_in"))
      (node (ref "IC6") (pin "30") (pinfunction "GNDD_2_30") (pintype "power_in"))
      (node (ref "IC6") (pin "49") (pinfunction "GNDP_49") (pintype "power_in"))
      (node (ref "IC6") (pin "6") (pinfunction "GNDA_6") (pintype "power_in"))
      (node (ref "R54") (pin "1") (pinfunction "1_1") (pintype "passive"))
      (node (ref "R57") (pin "2") (pinfunction "2_2") (pintype "passive"))
      (node (ref "R59") (pin "1") (pinfunction "1_1") (pintype "passive"))
      (node (ref "R60") (pin "2") (pinfunction "2_2") (pintype "passive"))
      (node (ref "SV14") (pin "15") (pinfunction "15_15") (pintype "passive"))
      (node (ref "SV14") (pin "3") (pinfunction "3_3") (pintype "passive"))
    )
    (net (code "266") (name "ZDRIVERVBB") (class "Default")
      (node (ref "C76") (pin "1") (pinfunction "1_1") (pintype "passive"))
      (node (ref "C77") (pin "1") (pinfunction "1_1") (pintype "passive"))
      (node (ref "C79") (pin "1") (pinfunction "1_1") (pintype "passive"))
      (node (ref "C81") (pin "2") (pinfunction "2_2") (pintype "passive"))
      (node (ref "C83") (pin "1") (pinfunction "1_1") (pintype "passive"))
      (node (ref "C87") (pin "1") (pinfunction "1_1") (pintype "passive"))
      (node (ref "C91") (pin "1") (pinfunction "1_1") (pintype "passive"))
      (node (ref "IC6") (pin "33") (pinfunction "VS_33") (pintype "power_in"))
      (node (ref "IC6") (pin "4") (pinfunction "VSA_4") (pintype "power_in"))
      (node (ref "Q16") (pin "10") (pinfunction "D1_10") (pintype "passive"))
      (node (ref "Q16") (pin "9") (pinfunction "D2_9") (pintype "passive"))
      (node (ref "Q18") (pin "10") (pinfunction "D1_10") (pintype "passive"))
      (node (ref "Q18") (pin "9") (pinfunction "D2_9") (pintype "passive"))
      (node (ref "SV14") (pin "1") (pinfunction "1_1") (pintype "passive"))
    )
    (net (code "267") (name "ZDRIVERVSS") (class "Default")
      (node (ref "C82") (pin "1") (pinfunction "1_1") (pintype "passive"))
      (node (ref "IC6") (pin "20") (pinfunction "VCC_IO_20") (pintype "power_in"))
      (node (ref "IC6") (pin "21") (pinfunction "SD_MODE_21") (pintype "input"))
      (node (ref "IC6") (pin "22") (pinfunction "SPI_MODE_22") (pintype "input"))
      (node (ref "SV14") (pin "13") (pinfunction "13_13") (pintype "passive"))
    )
    (net (code "268") (name "ZENABLE") (class "Default")
      (node (ref "IC6") (pin "28") (pinfunction "DRV_ENN_28") (pintype "input"))
      (node (ref "SV13") (pin "15") (pinfunction "15_15") (pintype "passive"))
    )
    (net (code "269") (name "ZHA1") (class "Default")
      (node (ref "IC6") (pin "41") (pinfunction "HA1_41") (pintype "output"))
      (node (ref "Q18") (pin "1") (pinfunction "G1_1") (pintype "passive"))
    )
    (net (code "270") (name "ZHA2") (class "Default")
      (node (ref "IC6") (pin "36") (pinfunction "HA2_36") (pintype "output"))
      (node (ref "Q18") (pin "8") (pinfunction "G2_8") (pintype "passive"))
    )
    (net (code "271") (name "ZHB1") (class "Default")
      (node (ref "IC6") (pin "1") (pinfunction "HB1_1") (pintype "output"))
      (node (ref "Q16") (pin "1") (pinfunction "G1_1") (pintype "passive"))
    )
    (net (code "272") (name "ZHB2") (class "Default")
      (node (ref "IC6") (pin "44") (pinfunction "HB2_44") (pintype "output"))
      (node (ref "Q16") (pin "8") (pinfunction "G2_8") (pintype "passive"))
    )
    (net (code "273") (name "ZLA1") (class "Default")
      (node (ref "IC6") (pin "39") (pinfunction "LA1_39") (pintype "output"))
      (node (ref "Q17") (pin "1") (pinfunction "G1_1") (pintype "passive"))
    )
    (net (code "274") (name "ZLA2") (class "Default")
      (node (ref "IC6") (pin "38") (pinfunction "LA2_38") (pintype "output"))
      (node (ref "Q17") (pin "8") (pinfunction "G2_8") (pintype "passive"))
    )
    (net (code "275") (name "ZLB1") (class "Default")
      (node (ref "IC6") (pin "47") (pinfunction "LB1_47") (pintype "output"))
      (node (ref "Q15") (pin "1") (pinfunction "G1_1") (pintype "passive"))
    )
    (net (code "276") (name "ZLB2") (class "Default")
      (node (ref "IC6") (pin "46") (pinfunction "LB2_46") (pintype "output"))
      (node (ref "Q15") (pin "8") (pinfunction "G2_8") (pintype "passive"))
    )
    (net (code "277") (name "ZMIN") (class "Default")
      (node (ref "R30") (pin "2") (pinfunction "2_2") (pintype "passive"))
      (node (ref "U1") (pin "43") (pinfunction "P1[27]/CLKOUT/~{USB_OVRCR/CAP0[1]}_43") (pintype "bidirectional"))
    )
    (net (code "278") (name "ZMOTORMISO") (class "Default")
      (node (ref "IC6") (pin "16") (pinfunction "SDO_CFG0_16") (pintype "output"))
      (node (ref "SV13") (pin "7") (pinfunction "7_7") (pintype "passive"))
    )
    (net (code "279") (name "ZMOTORMOSI") (class "Default")
      (node (ref "IC6") (pin "15") (pinfunction "SDI_CFG1_15") (pintype "input"))
      (node (ref "SV13") (pin "13") (pinfunction "13_13") (pintype "passive"))
    )
    (net (code "280") (name "ZMOTORSCK") (class "Default")
      (node (ref "IC6") (pin "14") (pinfunction "SCK_CFG2_14") (pintype "input"))
      (node (ref "SV13") (pin "11") (pinfunction "11_11") (pintype "passive"))
    )
    (net (code "281") (name "ZRX") (class "Default")
      (node (ref "IC6") (pin "13") (pinfunction "CSN_CFG3_13") (pintype "input"))
      (node (ref "SV13") (pin "9") (pinfunction "9_9") (pintype "passive"))
    )
    (net (code "282") (name "ZSLP") (class "Default")
      (node (ref "IC6") (pin "12") (pinfunction "CLK_12") (pintype "input"))
      (node (ref "SV13") (pin "5") (pinfunction "5_5") (pintype "passive"))
    )
    (net (code "283") (name "ZSRAH") (class "Default")
      (node (ref "IC6") (pin "8") (pinfunction "SRAH_8") (pintype "input"))
      (node (ref "R55") (pin "1") (pinfunction "1_1") (pintype "passive"))
    )
    (net (code "284") (name "ZSRAL") (class "Default")
      (node (ref "IC6") (pin "7") (pinfunction "SRAL_7") (pintype "input"))
      (node (ref "R59") (pin "2") (pinfunction "2_2") (pintype "passive"))
    )
    (net (code "285") (name "ZSRBH") (class "Default")
      (node (ref "IC6") (pin "9") (pinfunction "SRBH_9") (pintype "input"))
      (node (ref "R56") (pin "1") (pinfunction "1_1") (pintype "passive"))
    )
    (net (code "286") (name "ZSRBL") (class "Default")
      (node (ref "IC6") (pin "10") (pinfunction "SRBL_10") (pintype "input"))
      (node (ref "R54") (pin "2") (pinfunction "2_2") (pintype "passive"))
    )
    (net (code "287") (name "ZSTP") (class "Default")
      (node (ref "IC6") (pin "17") (pinfunction "REFL_STEP_17") (pintype "input"))
      (node (ref "SV13") (pin "3") (pinfunction "3_3") (pintype "passive"))
    )
    (net (code "288") (name "unconnected-(EXP2B-KL-Pad10)") (class "Default")
      (node (ref "EXP2") (pin "10") (pinfunction "KL_10") (pintype "passive"))
    )
    (net (code "289") (name "unconnected-(F1-Pad1B)") (class "Default")
      (node (ref "F1") (pin "1B") (pinfunction "1B_1B") (pintype "passive"))
    )
    (net (code "290") (name "unconnected-(F1-Pad2B)") (class "Default")
      (node (ref "F1") (pin "2B") (pinfunction "2B_2B") (pintype "passive"))
    )
    (net (code "291") (name "unconnected-(F2-Pad1B)") (class "Default")
      (node (ref "F2") (pin "1B") (pinfunction "1B_1B") (pintype "passive"))
    )
    (net (code "292") (name "unconnected-(F2-Pad2B)") (class "Default")
      (node (ref "F2") (pin "2B") (pinfunction "2B_2B") (pintype "passive"))
    )
    (net (code "293") (name "unconnected-(F3-Pad1B)") (class "Default")
      (node (ref "F3") (pin "1B") (pinfunction "1B_1B") (pintype "passive"))
    )
    (net (code "294") (name "unconnected-(F3-Pad2B)") (class "Default")
      (node (ref "F3") (pin "2B") (pinfunction "2B_2B") (pintype "passive"))
    )
    (net (code "295") (name "unconnected-(IC4-DIAG0_SWN-Pad26)") (class "Default")
      (node (ref "IC4") (pin "26") (pinfunction "DIAG0_SWN_26") (pintype "bidirectional"))
    )
    (net (code "296") (name "unconnected-(IC4-DIAG1_SWP-Pad27)") (class "Default")
      (node (ref "IC4") (pin "27") (pinfunction "DIAG1_SWP_27") (pintype "bidirectional"))
    )
    (net (code "297") (name "unconnected-(IC4-ENCA_CFG5-Pad24)") (class "Default")
      (node (ref "IC4") (pin "24") (pinfunction "ENCA_CFG5_24") (pintype "input"))
    )
    (net (code "298") (name "unconnected-(IC4-ENCB_CFG4-Pad23)") (class "Default")
      (node (ref "IC4") (pin "23") (pinfunction "ENCB_CFG4_23") (pintype "input"))
    )
    (net (code "299") (name "unconnected-(IC4-ENCN_CFG6-Pad25)") (class "Default")
      (node (ref "IC4") (pin "25") (pinfunction "ENCN_CFG6_25") (pintype "input"))
    )
    (net (code "300") (name "unconnected-(IC5-DIAG0_SWN-Pad26)") (class "Default")
      (node (ref "IC5") (pin "26") (pinfunction "DIAG0_SWN_26") (pintype "bidirectional"))
    )
    (net (code "301") (name "unconnected-(IC5-DIAG1_SWP-Pad27)") (class "Default")
      (node (ref "IC5") (pin "27") (pinfunction "DIAG1_SWP_27") (pintype "bidirectional"))
    )
    (net (code "302") (name "unconnected-(IC5-ENCA_CFG5-Pad24)") (class "Default")
      (node (ref "IC5") (pin "24") (pinfunction "ENCA_CFG5_24") (pintype "input"))
    )
    (net (code "303") (name "unconnected-(IC5-ENCB_CFG4-Pad23)") (class "Default")
      (node (ref "IC5") (pin "23") (pinfunction "ENCB_CFG4_23") (pintype "input"))
    )
    (net (code "304") (name "unconnected-(IC5-ENCN_CFG6-Pad25)") (class "Default")
      (node (ref "IC5") (pin "25") (pinfunction "ENCN_CFG6_25") (pintype "input"))
    )
    (net (code "305") (name "unconnected-(IC6-DIAG0_SWN-Pad26)") (class "Default")
      (node (ref "IC6") (pin "26") (pinfunction "DIAG0_SWN_26") (pintype "bidirectional"))
    )
    (net (code "306") (name "unconnected-(IC6-DIAG1_SWP-Pad27)") (class "Default")
      (node (ref "IC6") (pin "27") (pinfunction "DIAG1_SWP_27") (pintype "bidirectional"))
    )
    (net (code "307") (name "unconnected-(IC6-ENCA_CFG5-Pad24)") (class "Default")
      (node (ref "IC6") (pin "24") (pinfunction "ENCA_CFG5_24") (pintype "input"))
    )
    (net (code "308") (name "unconnected-(IC6-ENCB_CFG4-Pad23)") (class "Default")
      (node (ref "IC6") (pin "23") (pinfunction "ENCB_CFG4_23") (pintype "input"))
    )
    (net (code "309") (name "unconnected-(IC6-ENCN_CFG6-Pad25)") (class "Default")
      (node (ref "IC6") (pin "25") (pinfunction "ENCN_CFG6_25") (pintype "input"))
    )
    (net (code "310") (name "unconnected-(IC7-DIAG0_SWN-Pad26)") (class "Default")
      (node (ref "IC7") (pin "26") (pinfunction "DIAG0_SWN_26") (pintype "bidirectional"))
    )
    (net (code "311") (name "unconnected-(IC7-DIAG1_SWP-Pad27)") (class "Default")
      (node (ref "IC7") (pin "27") (pinfunction "DIAG1_SWP_27") (pintype "bidirectional"))
    )
    (net (code "312") (name "unconnected-(IC7-ENCA_CFG5-Pad24)") (class "Default")
      (node (ref "IC7") (pin "24") (pinfunction "ENCA_CFG5_24") (pintype "input"))
    )
    (net (code "313") (name "unconnected-(IC7-ENCB_CFG4-Pad23)") (class "Default")
      (node (ref "IC7") (pin "23") (pinfunction "ENCB_CFG4_23") (pintype "input"))
    )
    (net (code "314") (name "unconnected-(IC7-ENCN_CFG6-Pad25)") (class "Default")
      (node (ref "IC7") (pin "25") (pinfunction "ENCN_CFG6_25") (pintype "input"))
    )
    (net (code "315") (name "unconnected-(R18-PadE)") (class "Default")
      (node (ref "R18") (pin "E") (pinfunction "E_E") (pintype "passive"))
    )
    (net (code "316") (name "unconnected-(S1-P1-Pad4)") (class "Default")
      (node (ref "S1") (pin "4") (pinfunction "P1_4") (pintype "passive"))
    )
    (net (code "317") (name "unconnected-(S1-S1-Pad2)") (class "Default")
      (node (ref "S1") (pin "2") (pinfunction "S1_2") (pintype "passive"))
    )
    (net (code "318") (name "unconnected-(U$1-CH_PD-PadB2)") (class "Default")
      (node (ref "U$1") (pin "B2") (pinfunction "CH_PD_B2") (pintype "bidirectional"))
    )
    (net (code "319") (name "unconnected-(U$1-GPIO0-PadC1)") (class "Default")
      (node (ref "U$1") (pin "C1") (pinfunction "GPIO0_C1") (pintype "bidirectional"))
    )
    (net (code "320") (name "unconnected-(U$1-GPIO2-PadB1)") (class "Default")
      (node (ref "U$1") (pin "B1") (pinfunction "GPIO2_B1") (pintype "bidirectional"))
    )
    (net (code "321") (name "unconnected-(U$1-RST-PadC2)") (class "Default")
      (node (ref "U$1") (pin "C2") (pinfunction "RST_C2") (pintype "bidirectional"))
    )
    (net (code "322") (name "unconnected-(U1-NC-Pad13)") (class "Default")
      (node (ref "U1") (pin "13") (pinfunction "NC_13") (pintype "no_connect"))
    )
    (net (code "323") (name "unconnected-(U1-P1[0]{slash}ENET_TXD0-Pad95)") (class "Default")
      (node (ref "U1") (pin "95") (pinfunction "P1[0]/ENET_TXD0_95") (pintype "bidirectional"))
    )
    (net (code "324") (name "unconnected-(U1-P1[1]{slash}ENET_TXD1-Pad94)") (class "Default")
      (node (ref "U1") (pin "94") (pinfunction "P1[1]/ENET_TXD1_94") (pintype "bidirectional"))
    )
    (net (code "325") (name "unconnected-(U1-P1[14]{slash}ENET_RX_ER-Pad89)") (class "Default")
      (node (ref "U1") (pin "89") (pinfunction "P1[14]/ENET_RX_ER_89") (pintype "bidirectional"))
    )
    (net (code "326") (name "unconnected-(U1-P1[15]{slash}ENET_REF_CLK-Pad88)") (class "Default")
      (node (ref "U1") (pin "88") (pinfunction "P1[15]/ENET_REF_CLK_88") (pintype "bidirectional"))
    )
    (net (code "327") (name "unconnected-(U1-P1[16]{slash}ENET_MDC-Pad87)") (class "Default")
      (node (ref "U1") (pin "87") (pinfunction "P1[16]/ENET_MDC_87") (pintype "bidirectional"))
    )
    (net (code "328") (name "unconnected-(U1-P2[10]{slash}~{EINT0{slash}NMI}-Pad53)") (class "Default")
      (node (ref "U1") (pin "53") (pinfunction "P2[10]/~{EINT0/NMI}_53") (pintype "bidirectional"))
    )
    (net (code "329") (name "unconnected-(U1-RTCK-Pad100)") (class "Default")
      (node (ref "U1") (pin "100") (pinfunction "RTCK_100") (pintype "output"))
    )
    (net (code "330") (name "unconnected-(U1-RTCX2-Pad18)") (class "Default")
      (node (ref "U1") (pin "18") (pinfunction "RTCX2_18") (pintype "output"))
    )
    (net (code "331") (name "unconnected-(U1-TDI-Pad2)") (class "Default")
      (node (ref "U1") (pin "2") (pinfunction "TDI_2") (pintype "input"))
    )
    (net (code "332") (name "unconnected-(U1-TDO{slash}SWO-Pad1)") (class "Default")
      (node (ref "U1") (pin "1") (pinfunction "TDO/SWO_1") (pintype "output"))
    )
  )
)
